# rt1060r2.net
KiCad netlist of a schematic drawn in EAGLE
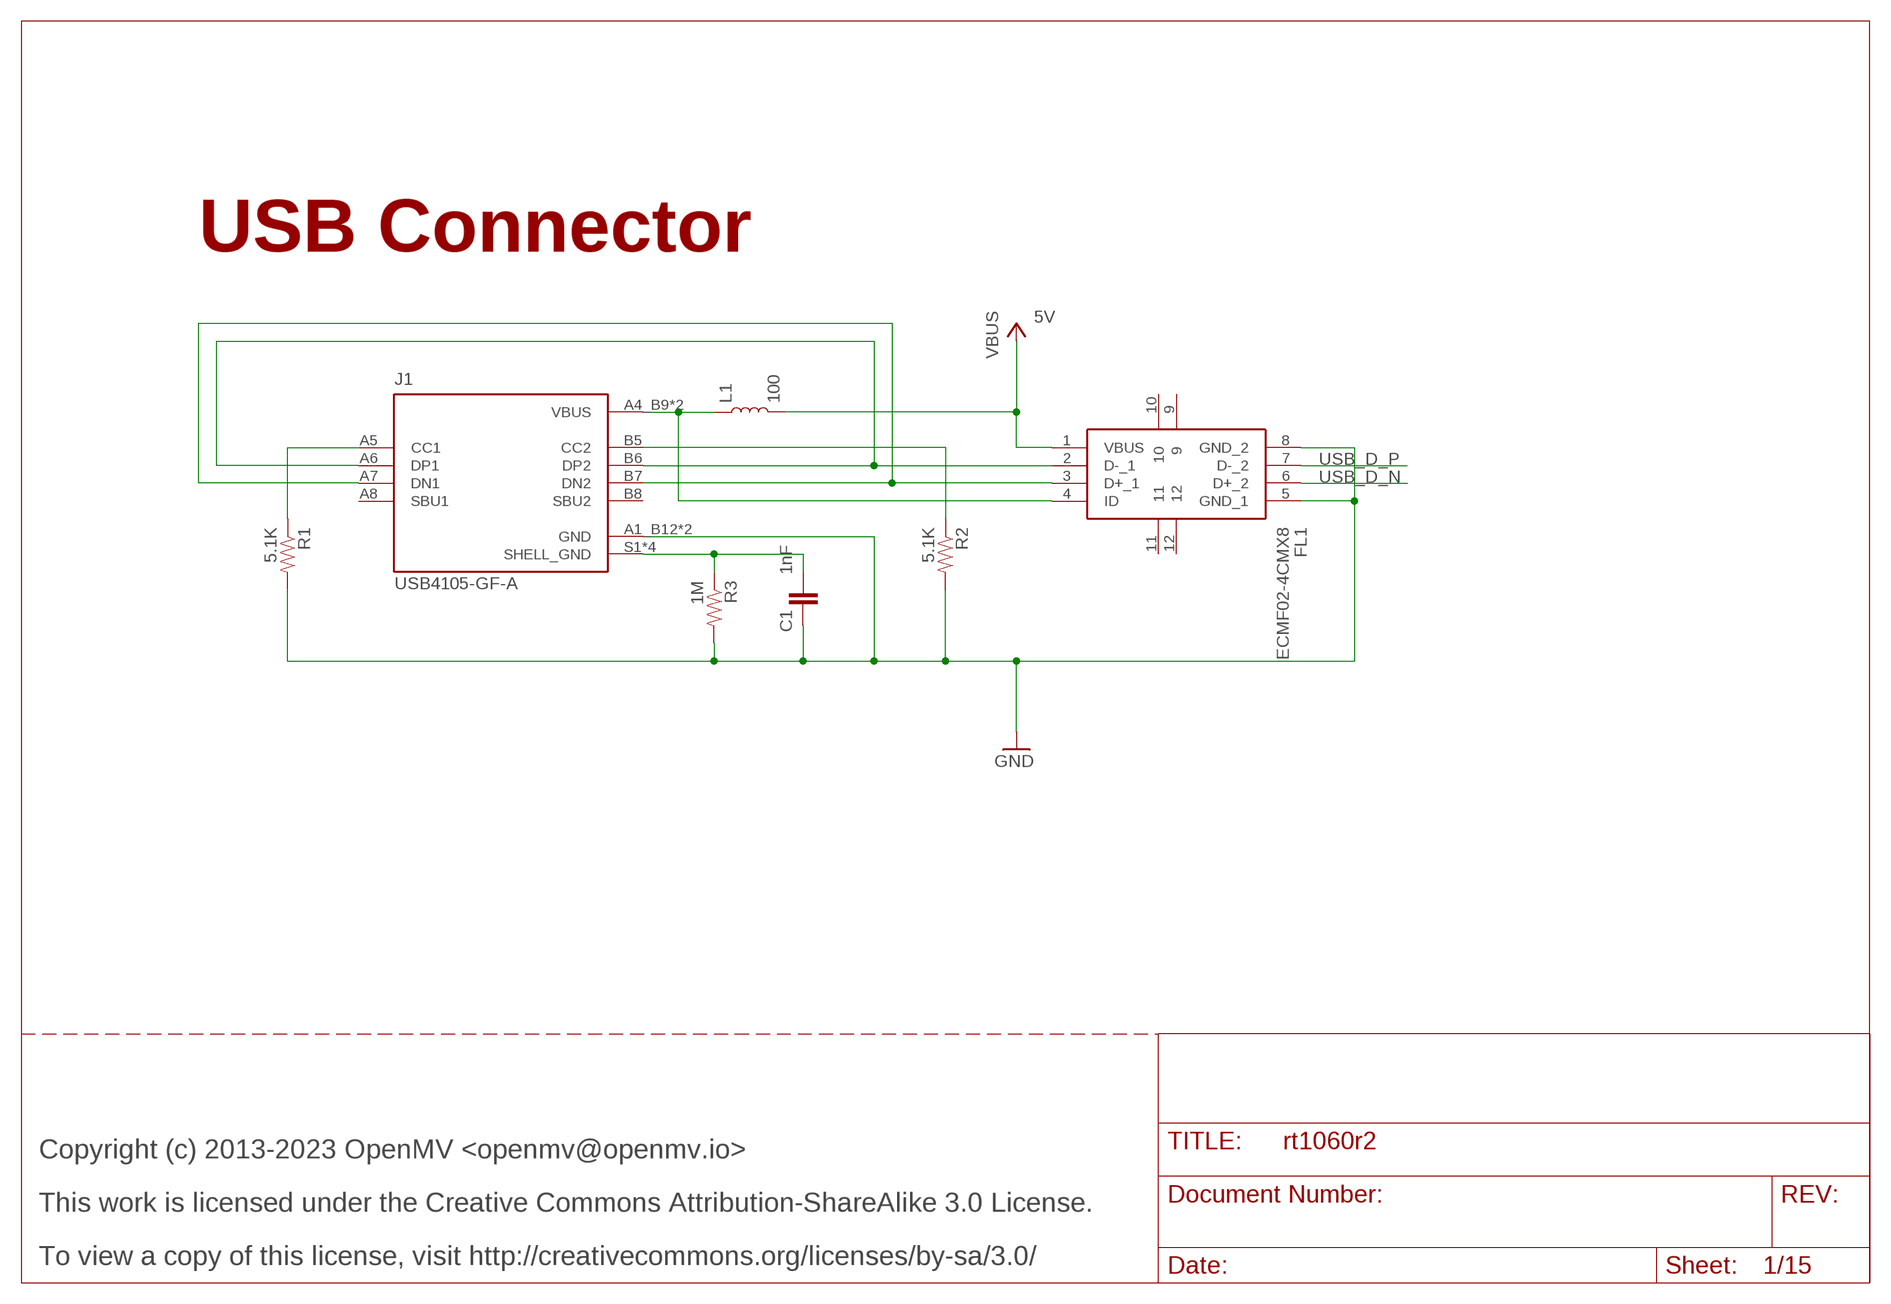
[diagram p0: schematic, sheet 1]
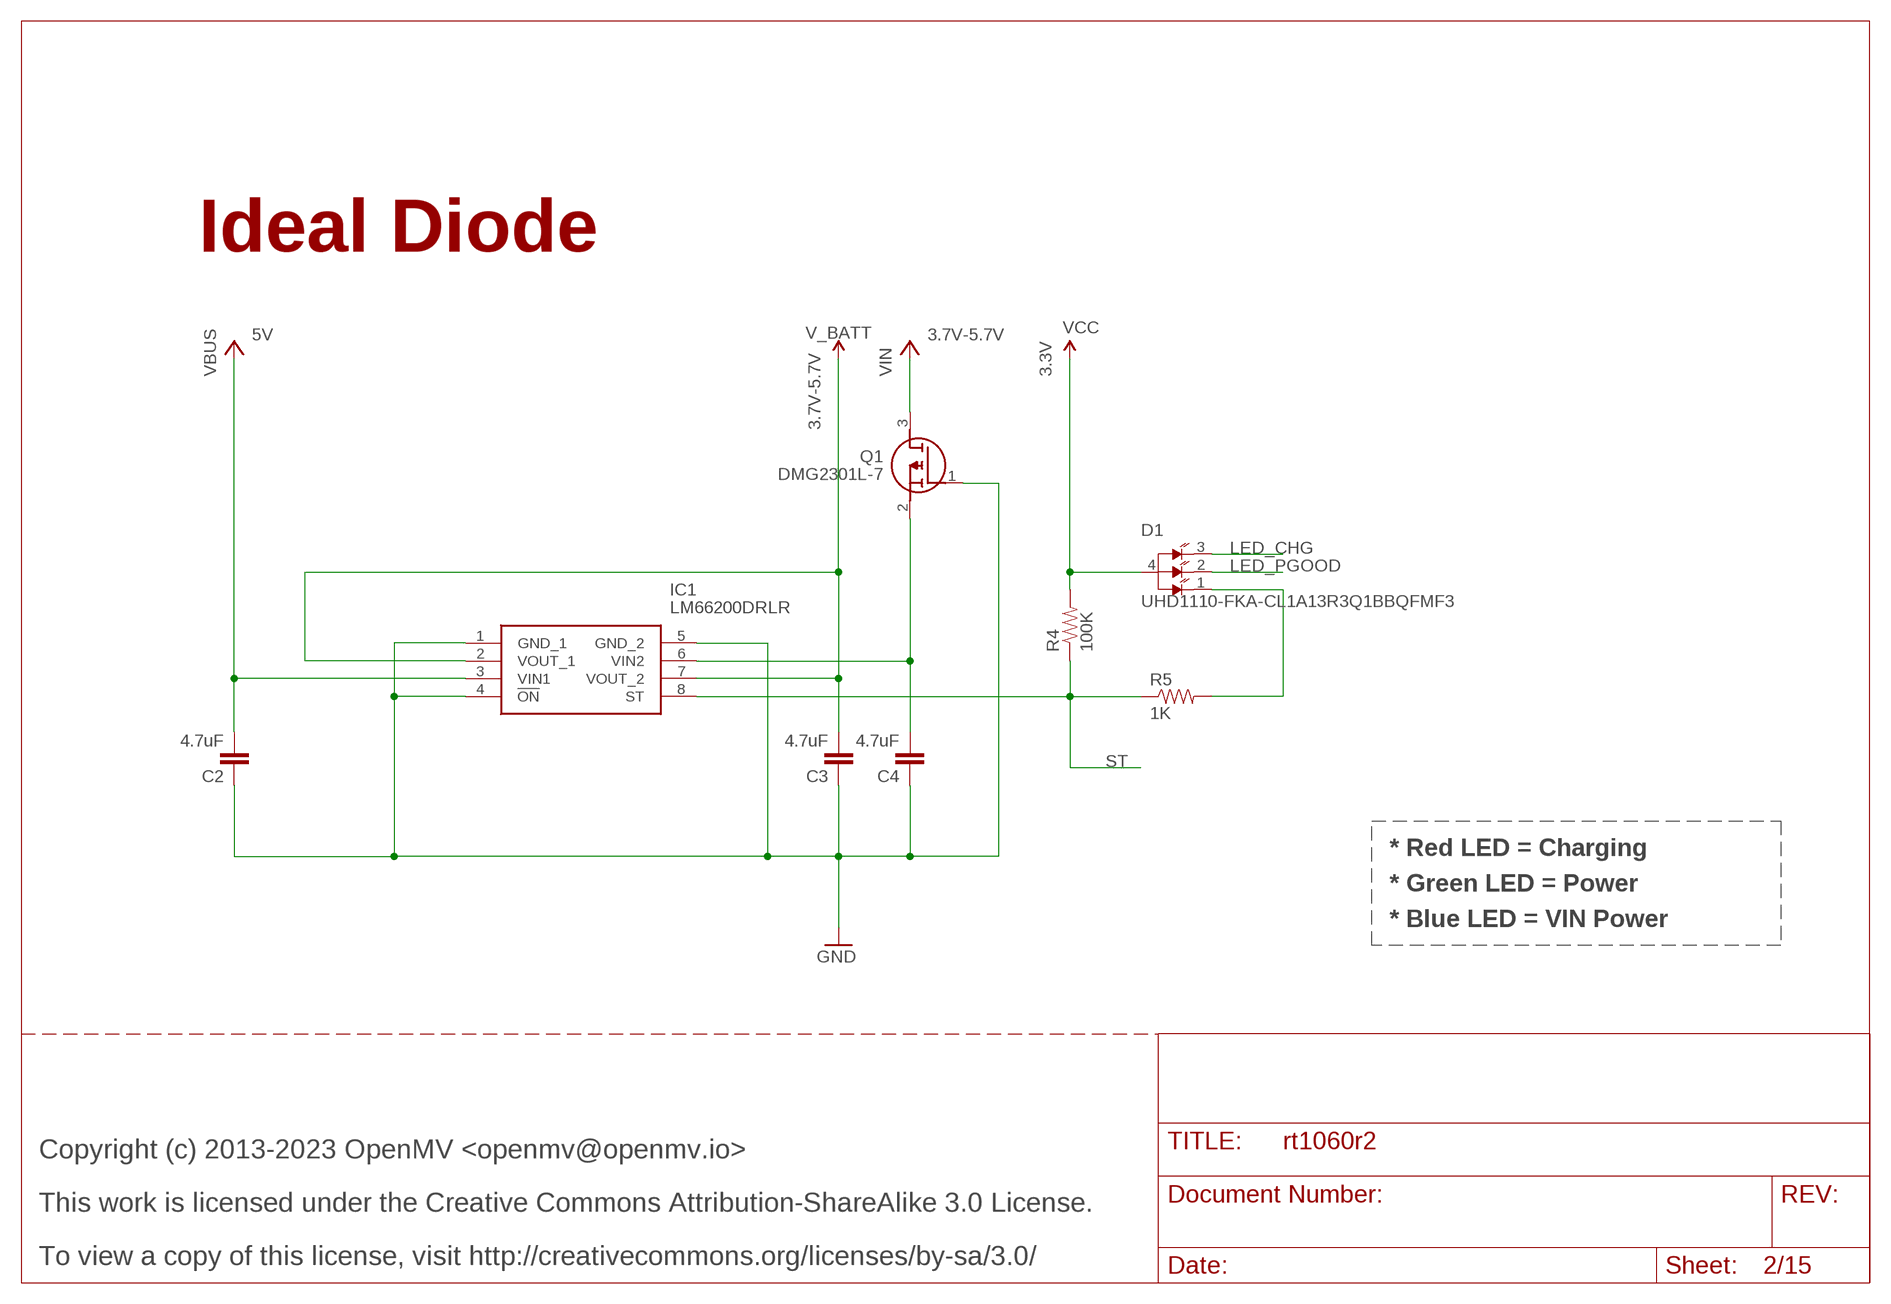
[diagram p1: schematic, sheet 2]
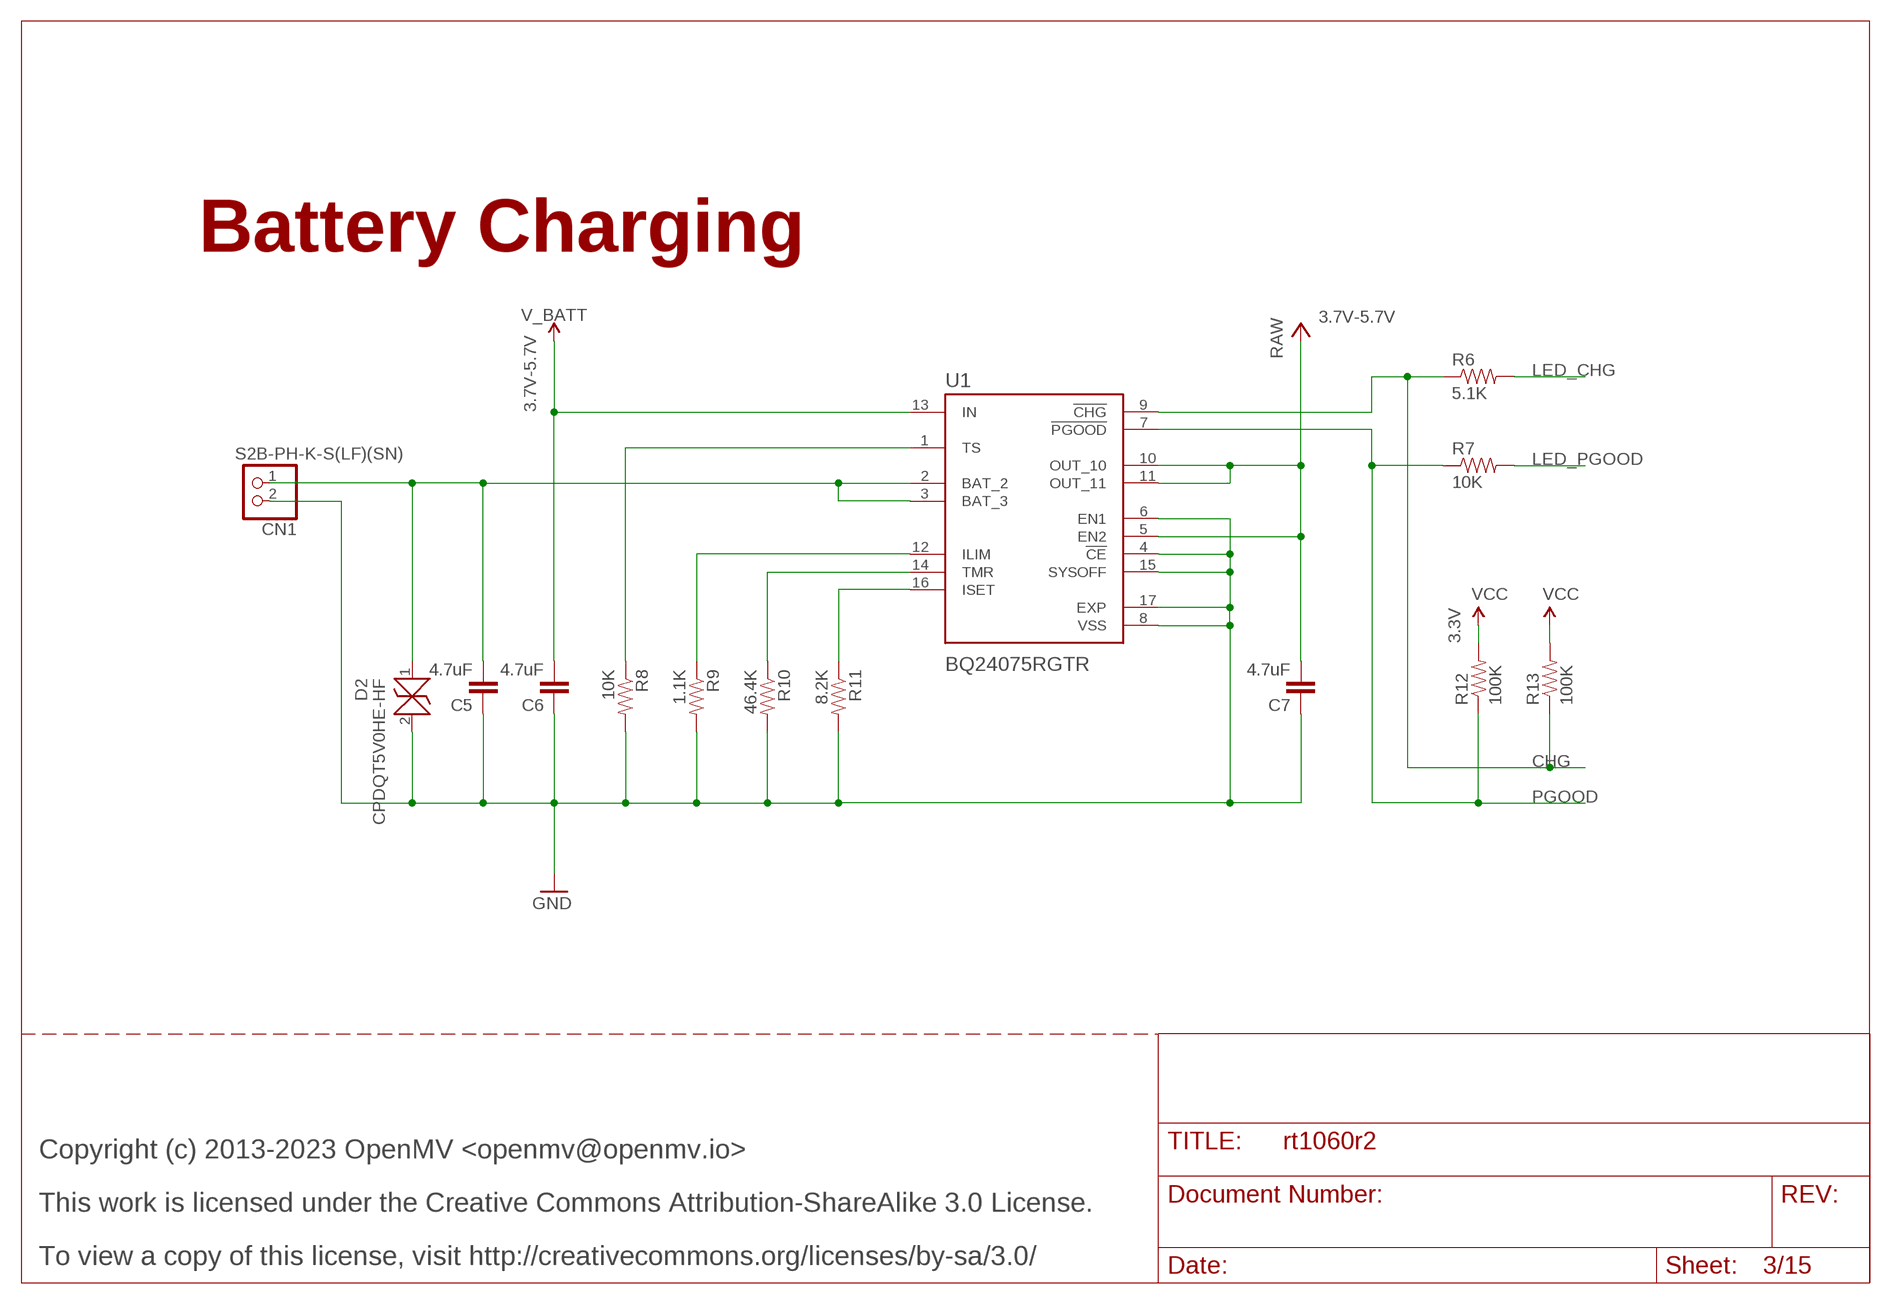
[diagram p2: schematic, sheet 3]
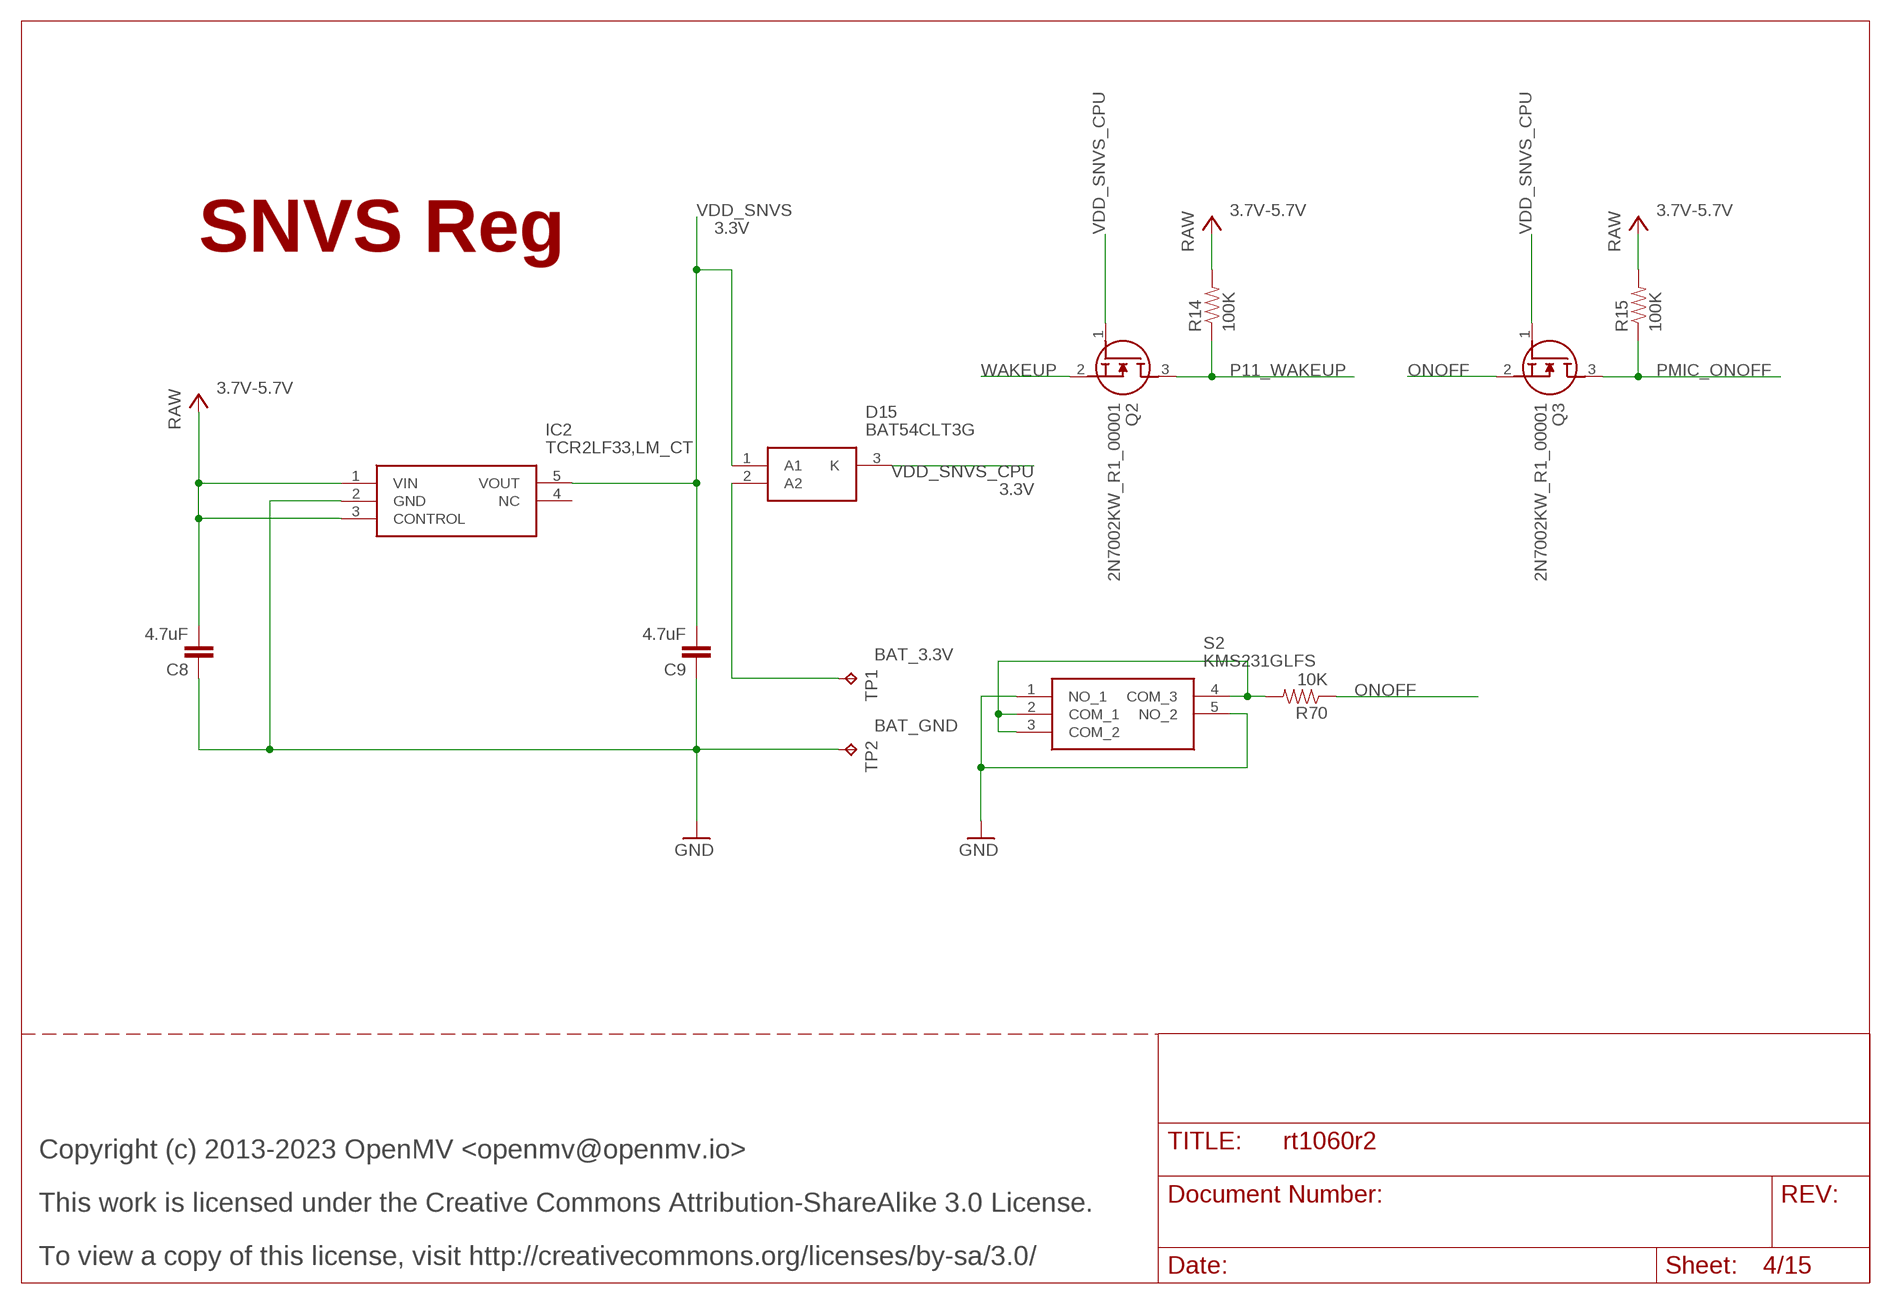
[diagram p3: schematic, sheet 4]
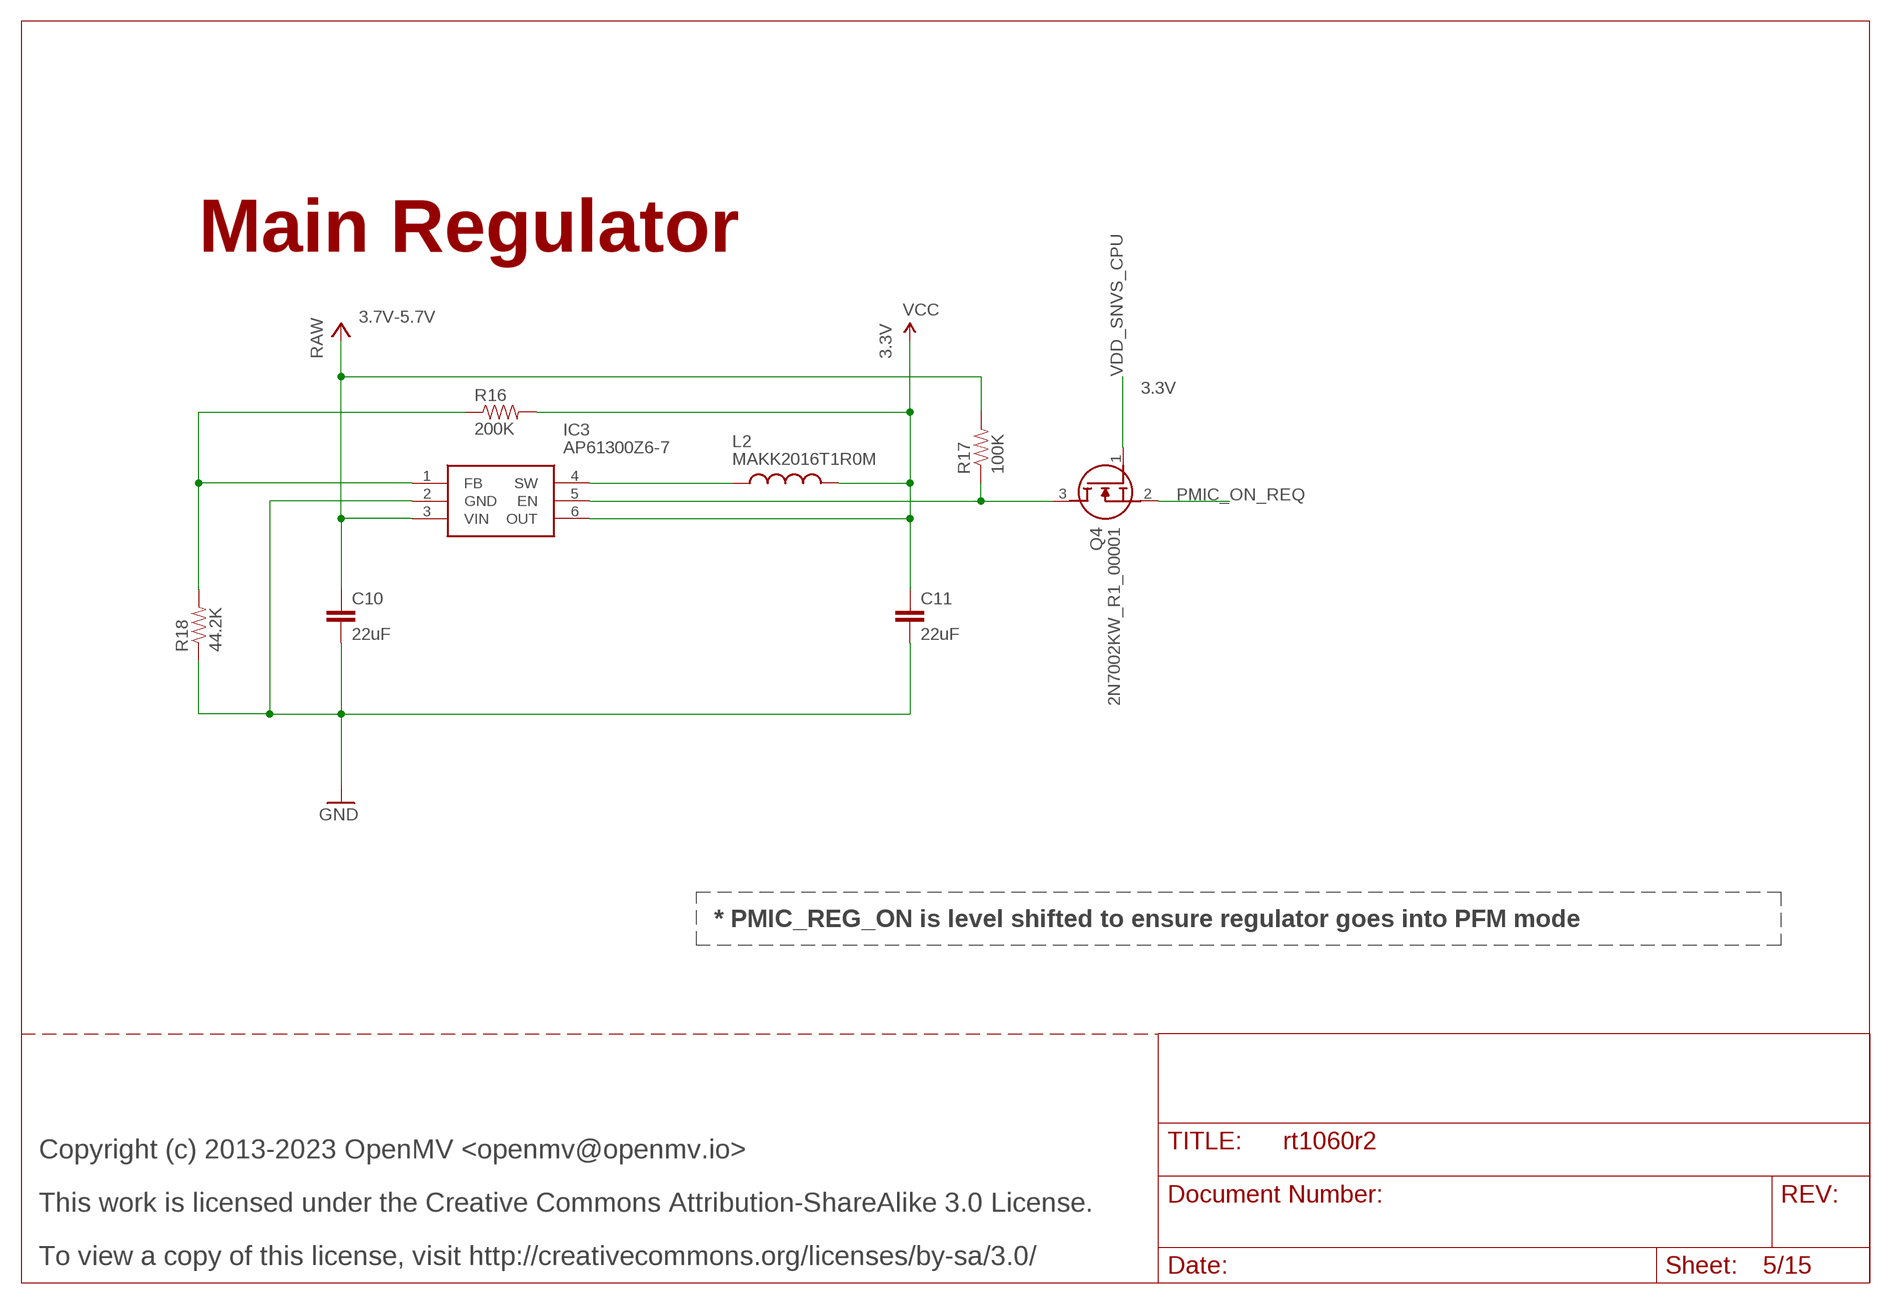
[diagram p4: schematic, sheet 5]
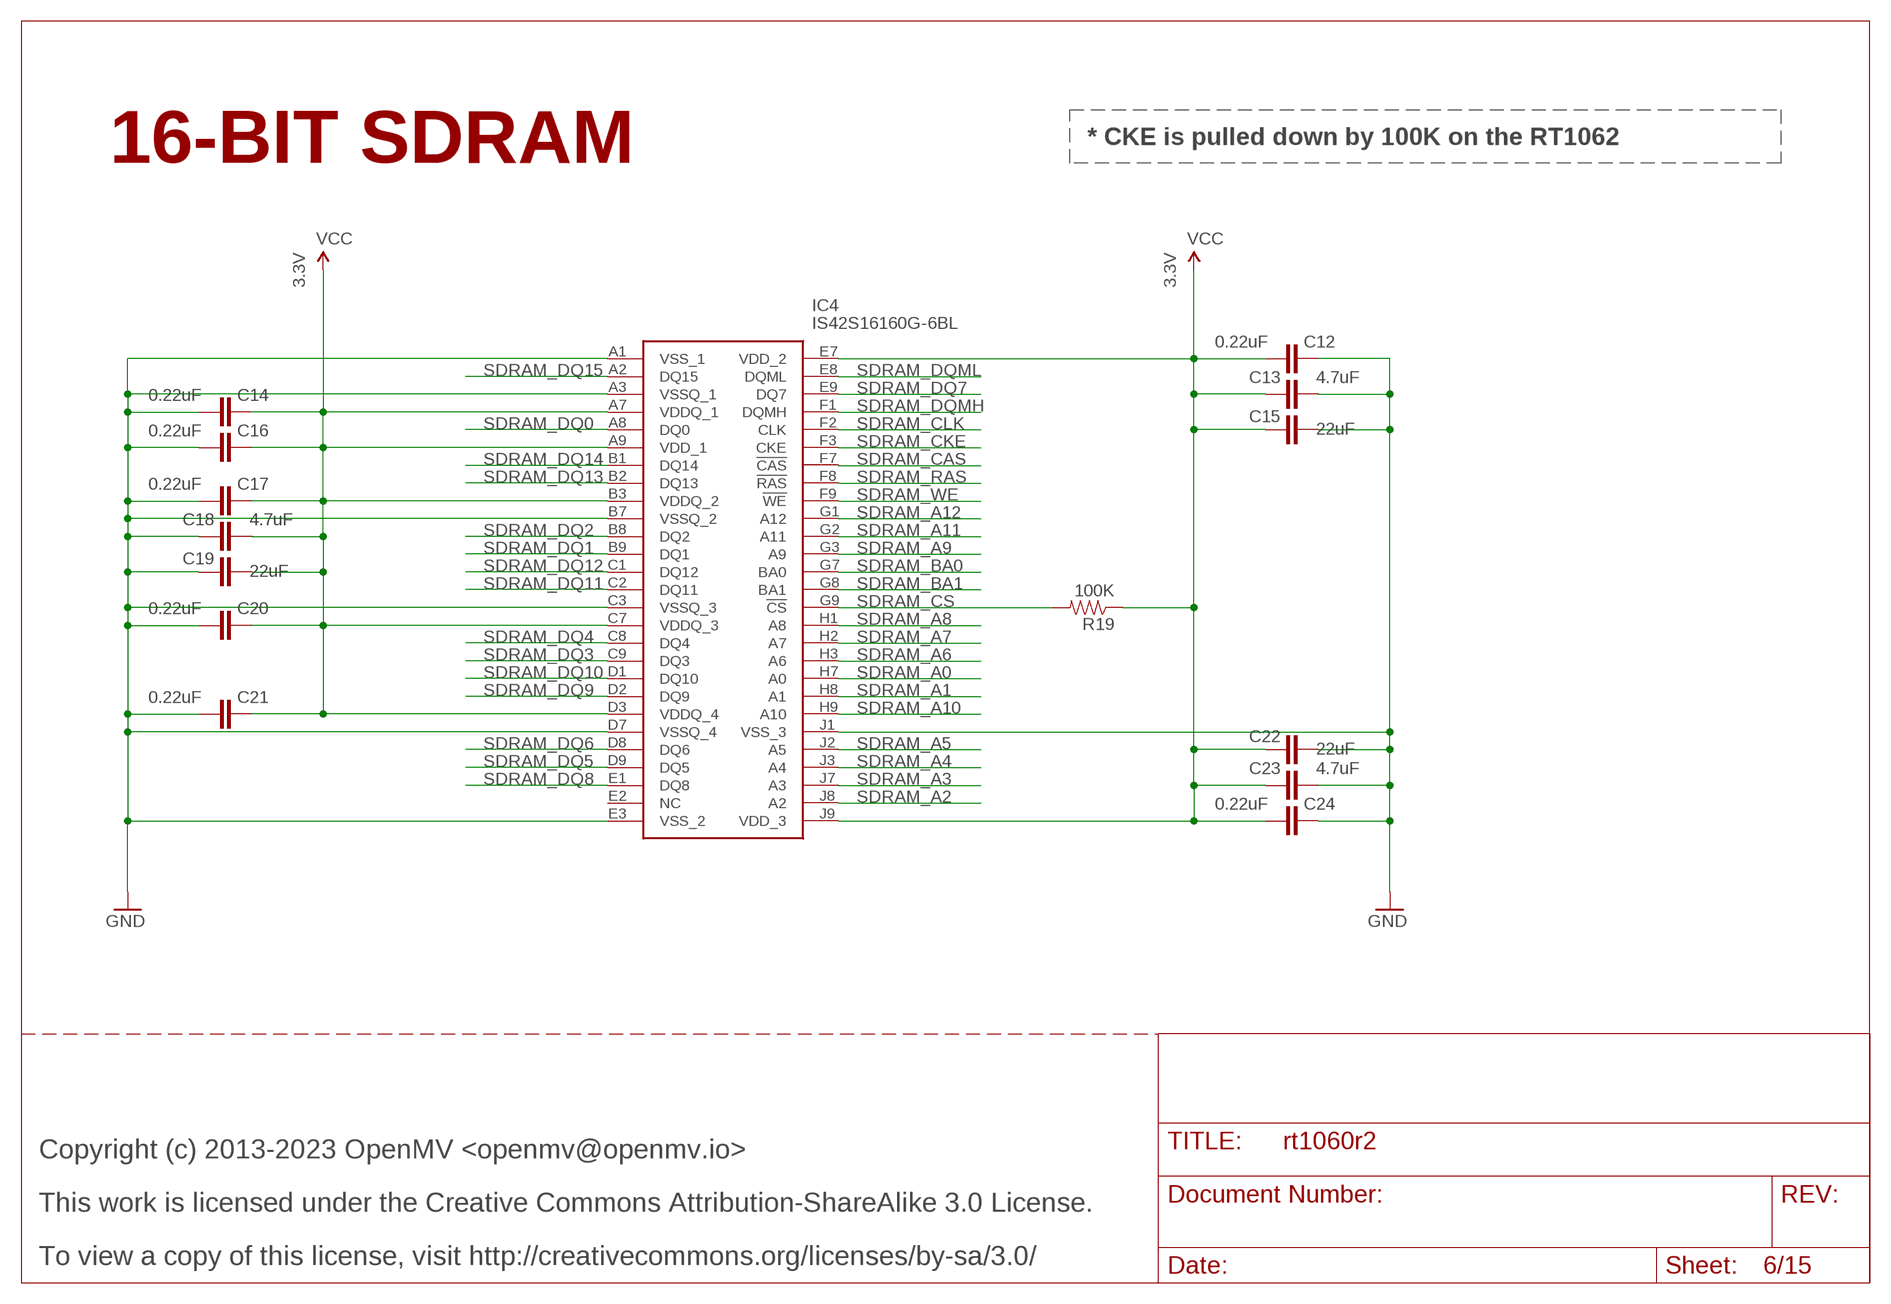
[diagram p5: schematic, sheet 6]
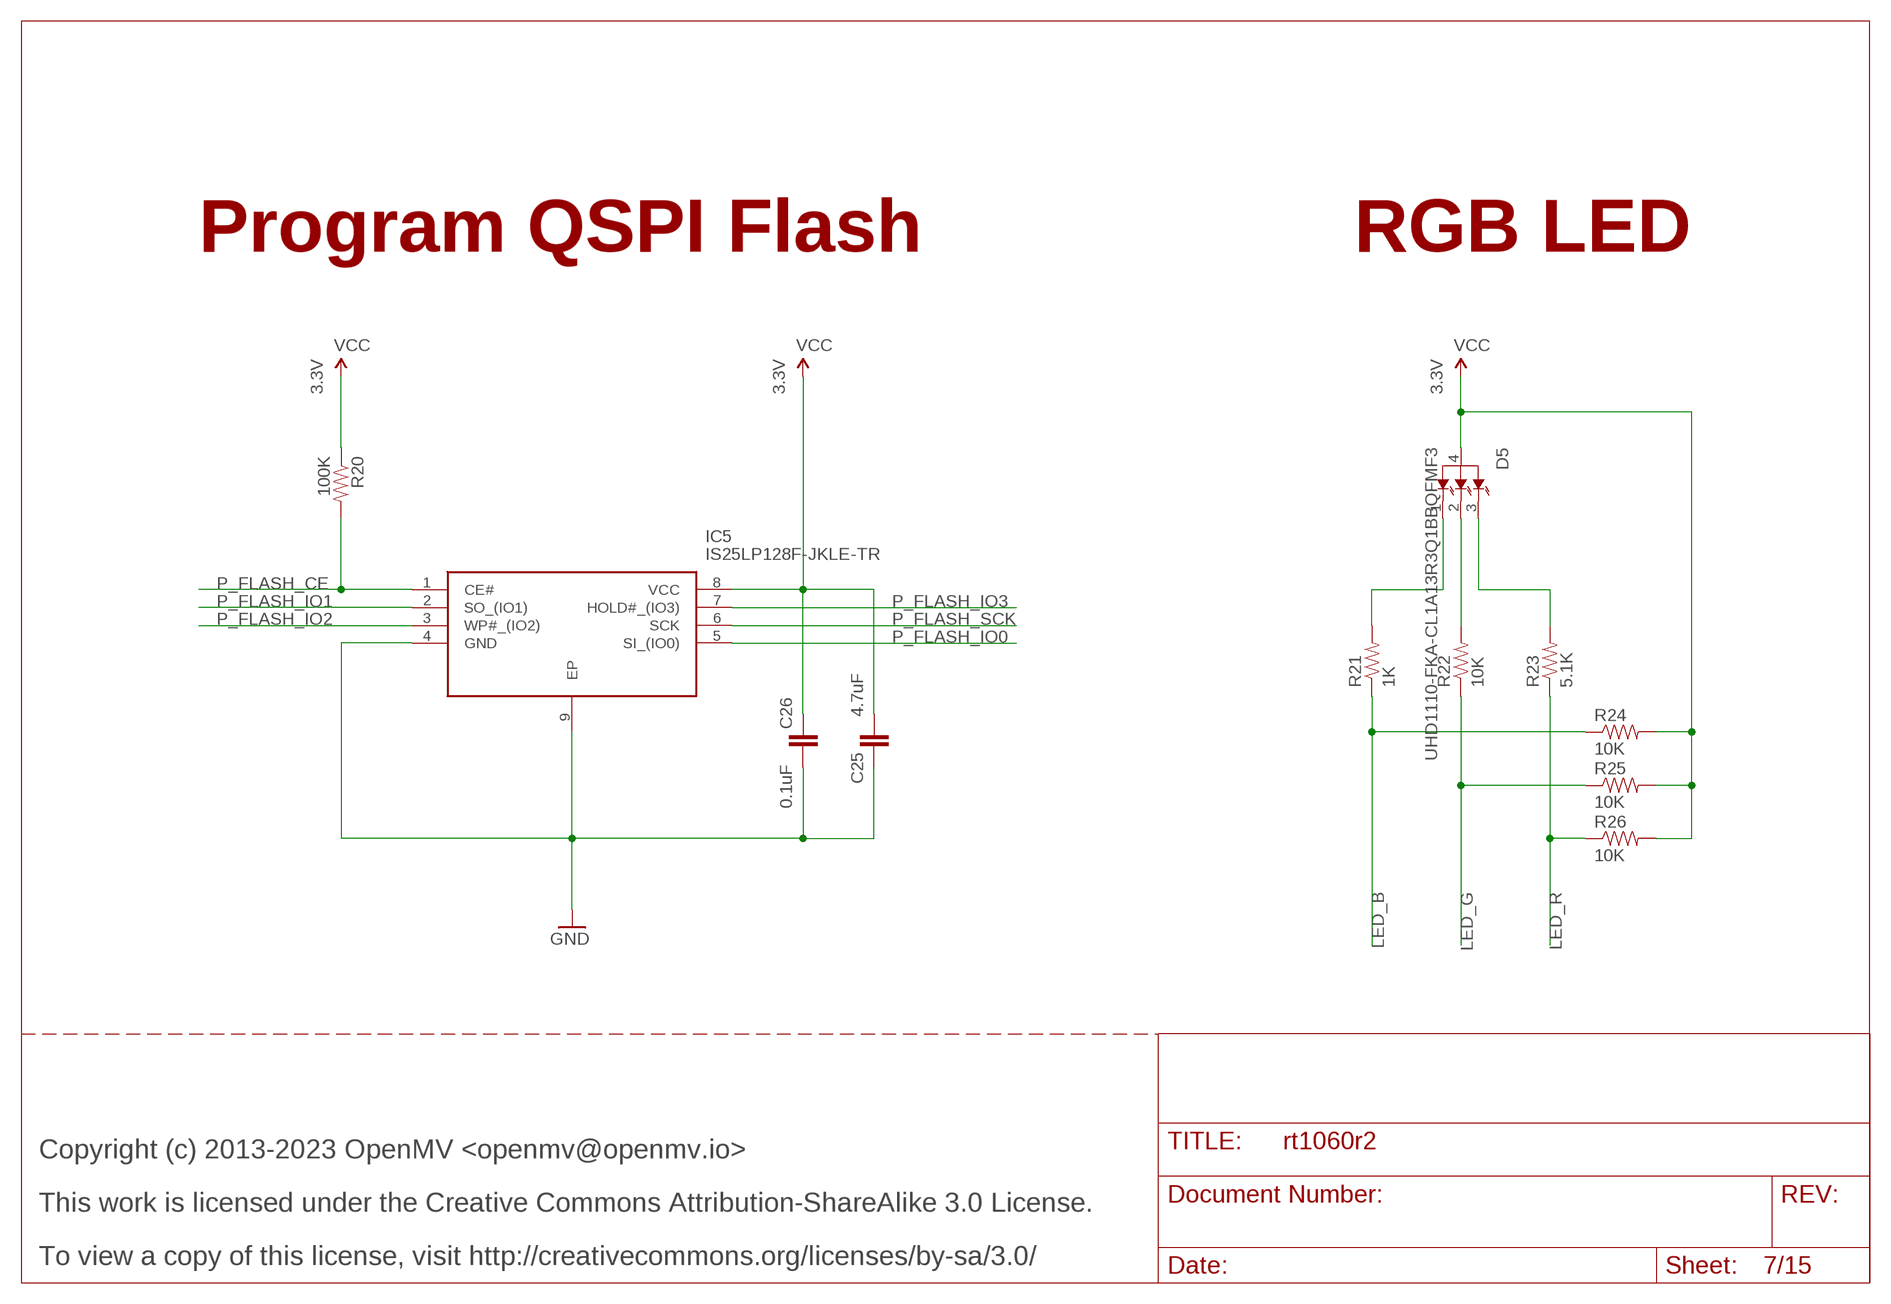
[diagram p6: schematic, sheet 7]
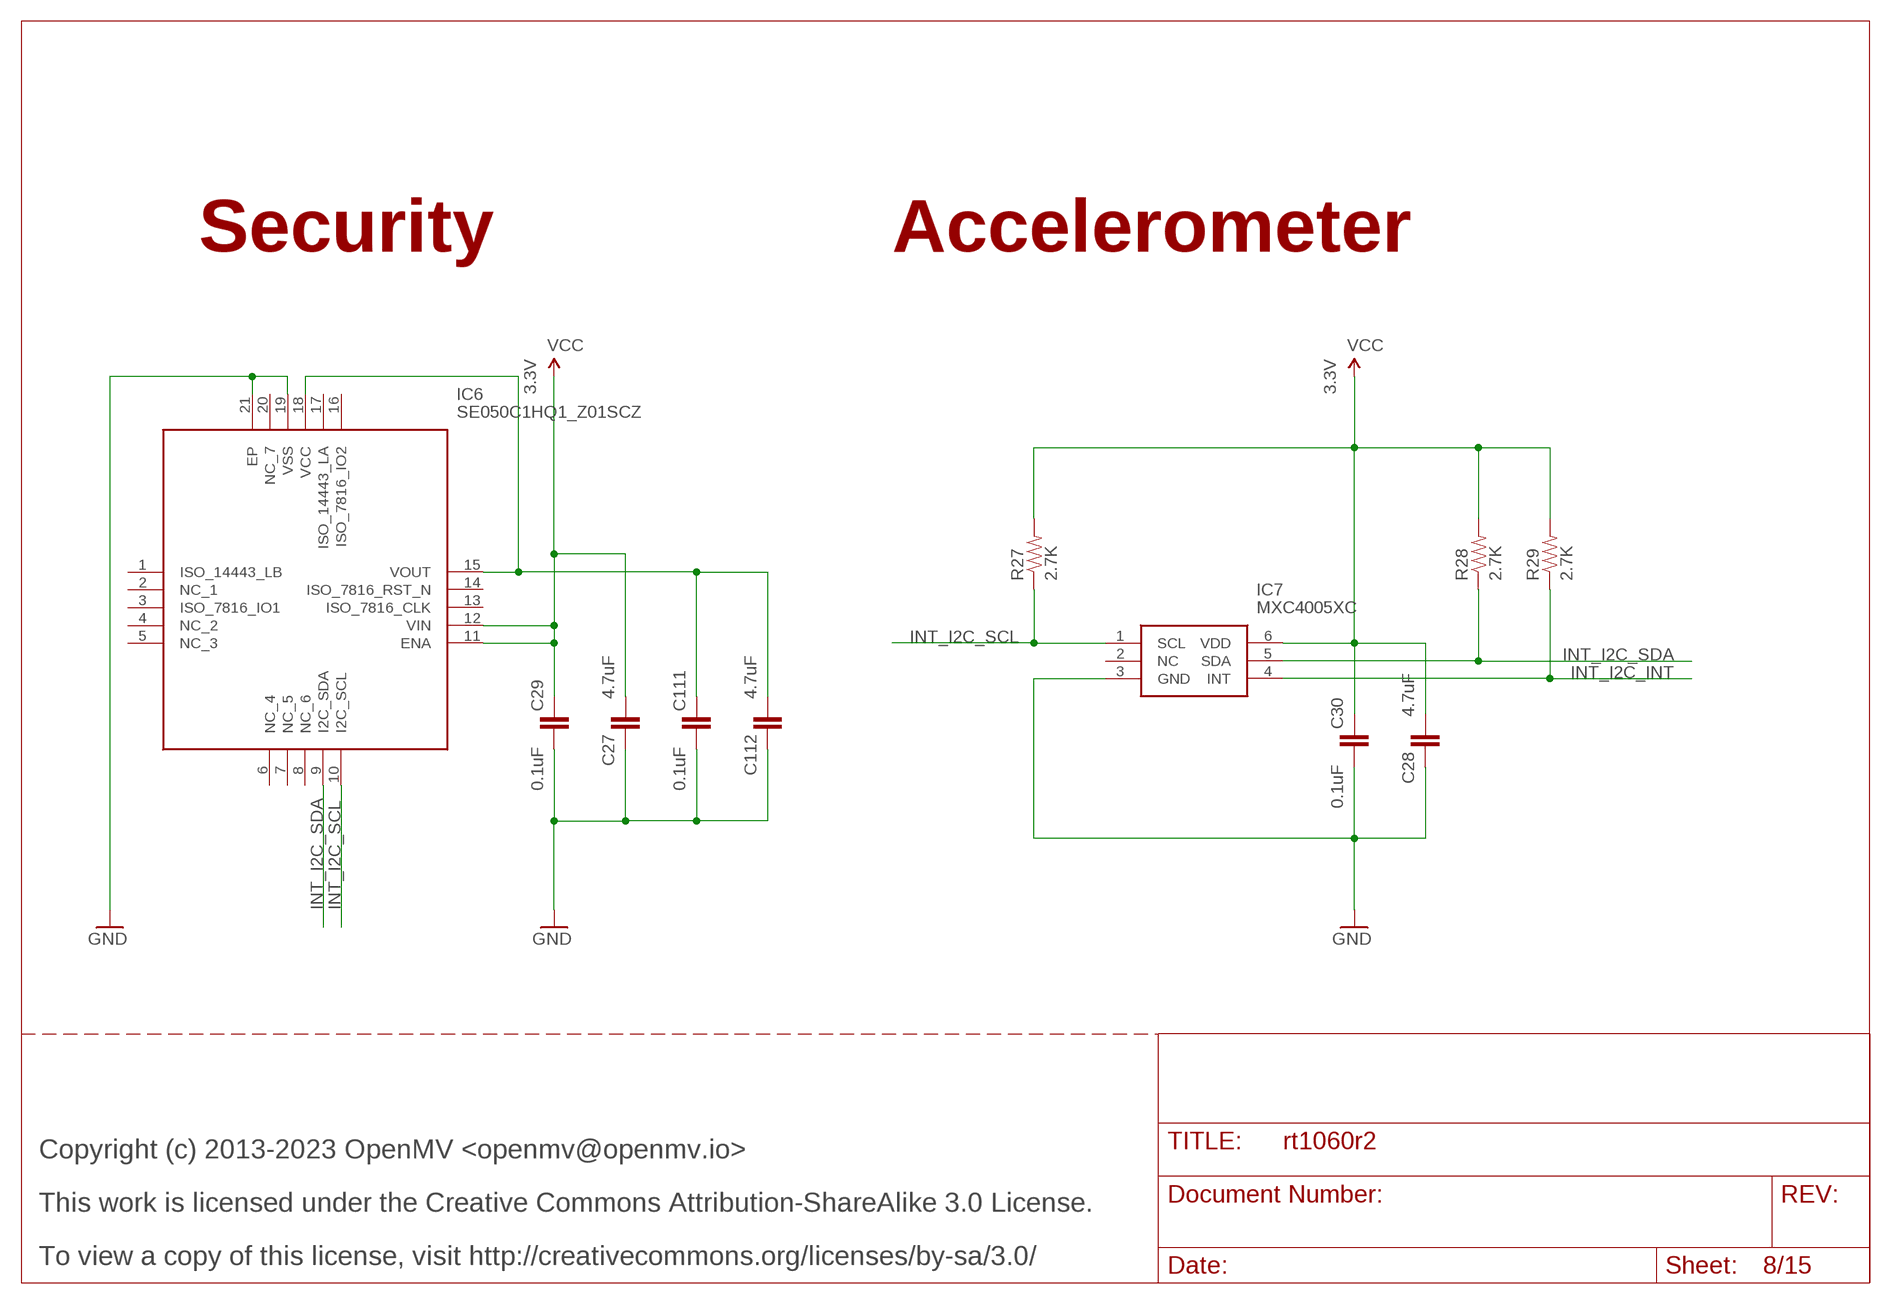
[diagram p7: schematic, sheet 8]
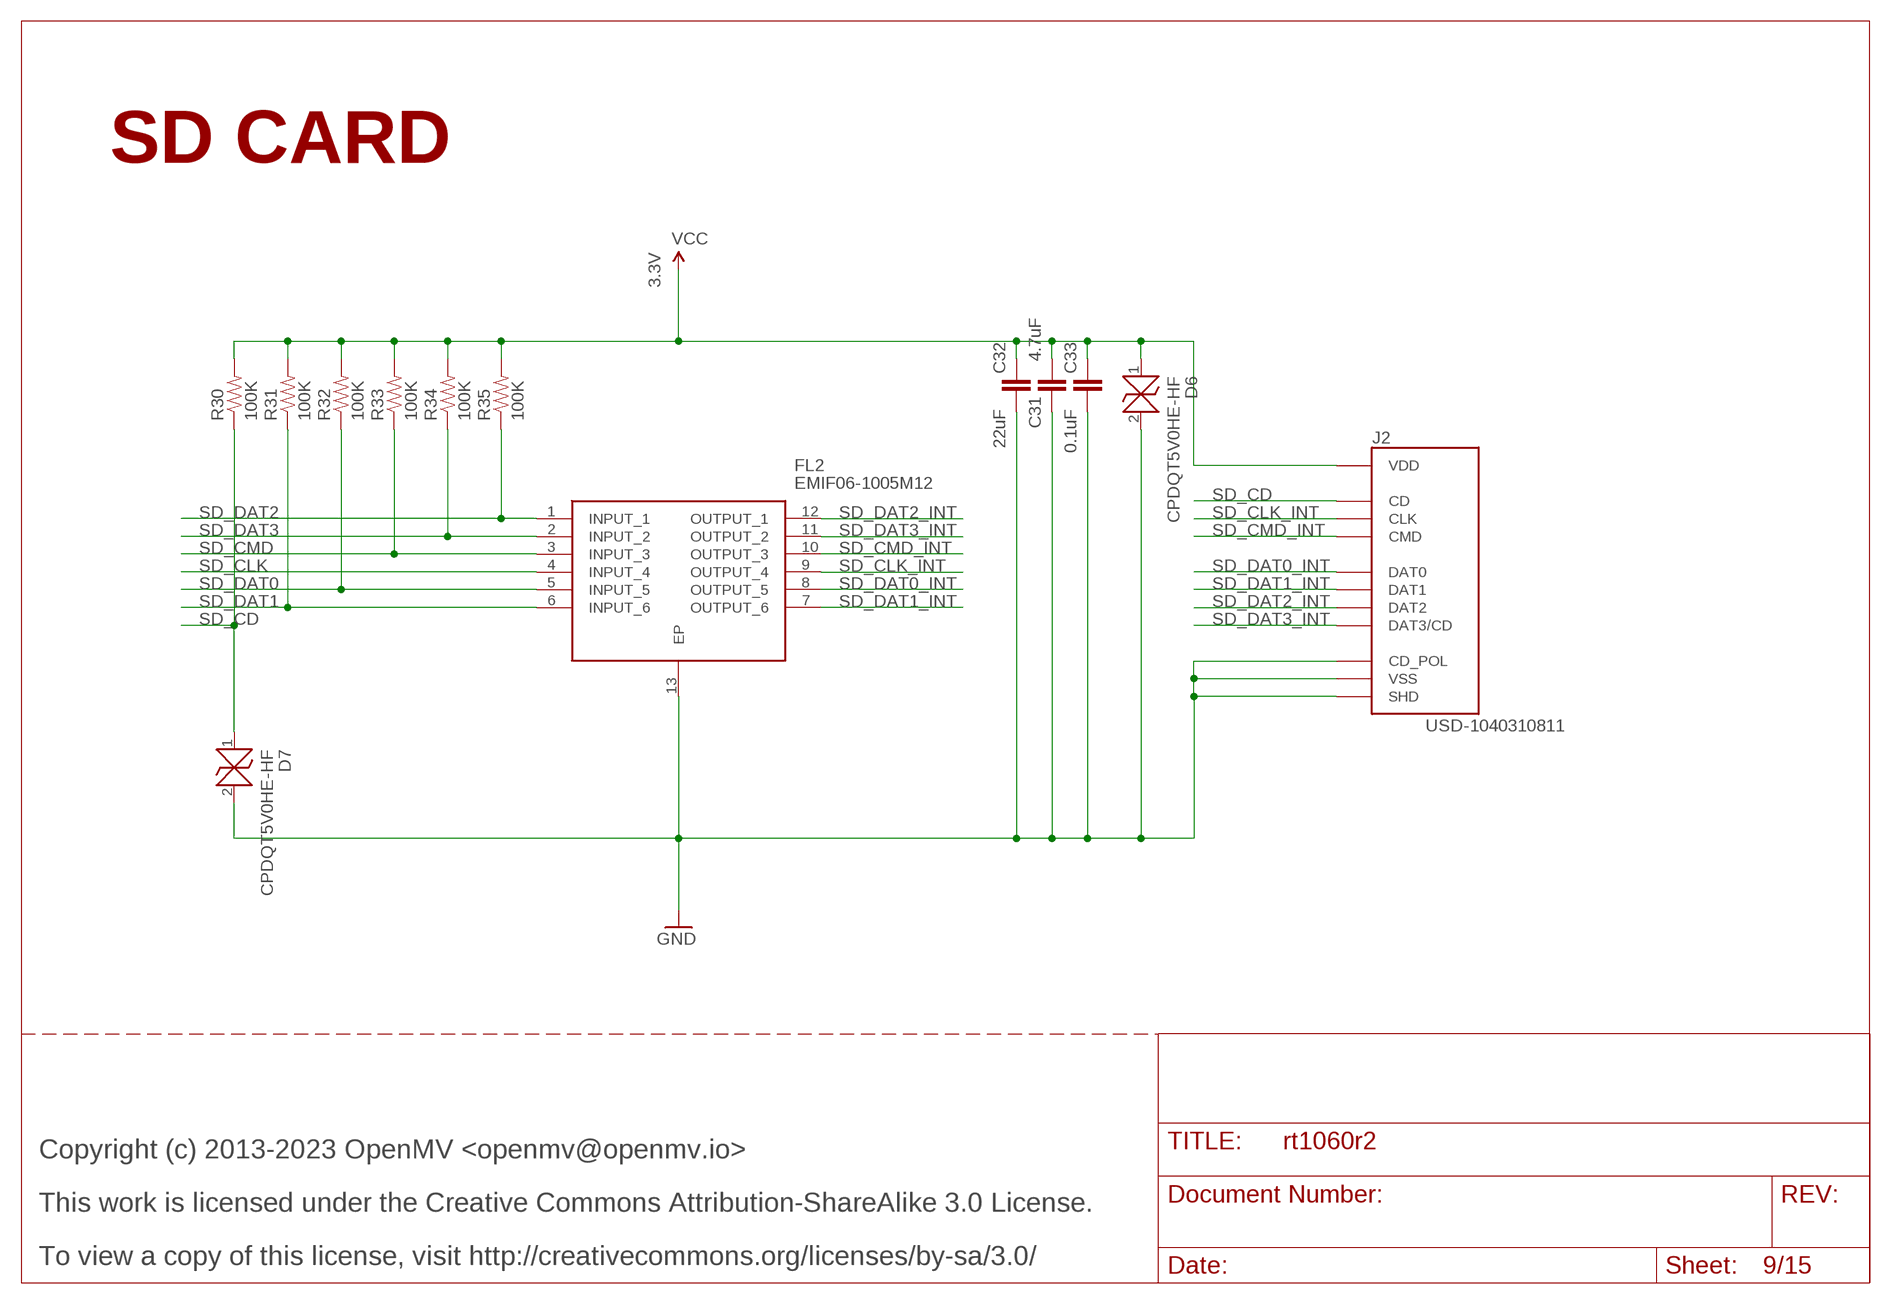
[diagram p8: schematic, sheet 9]
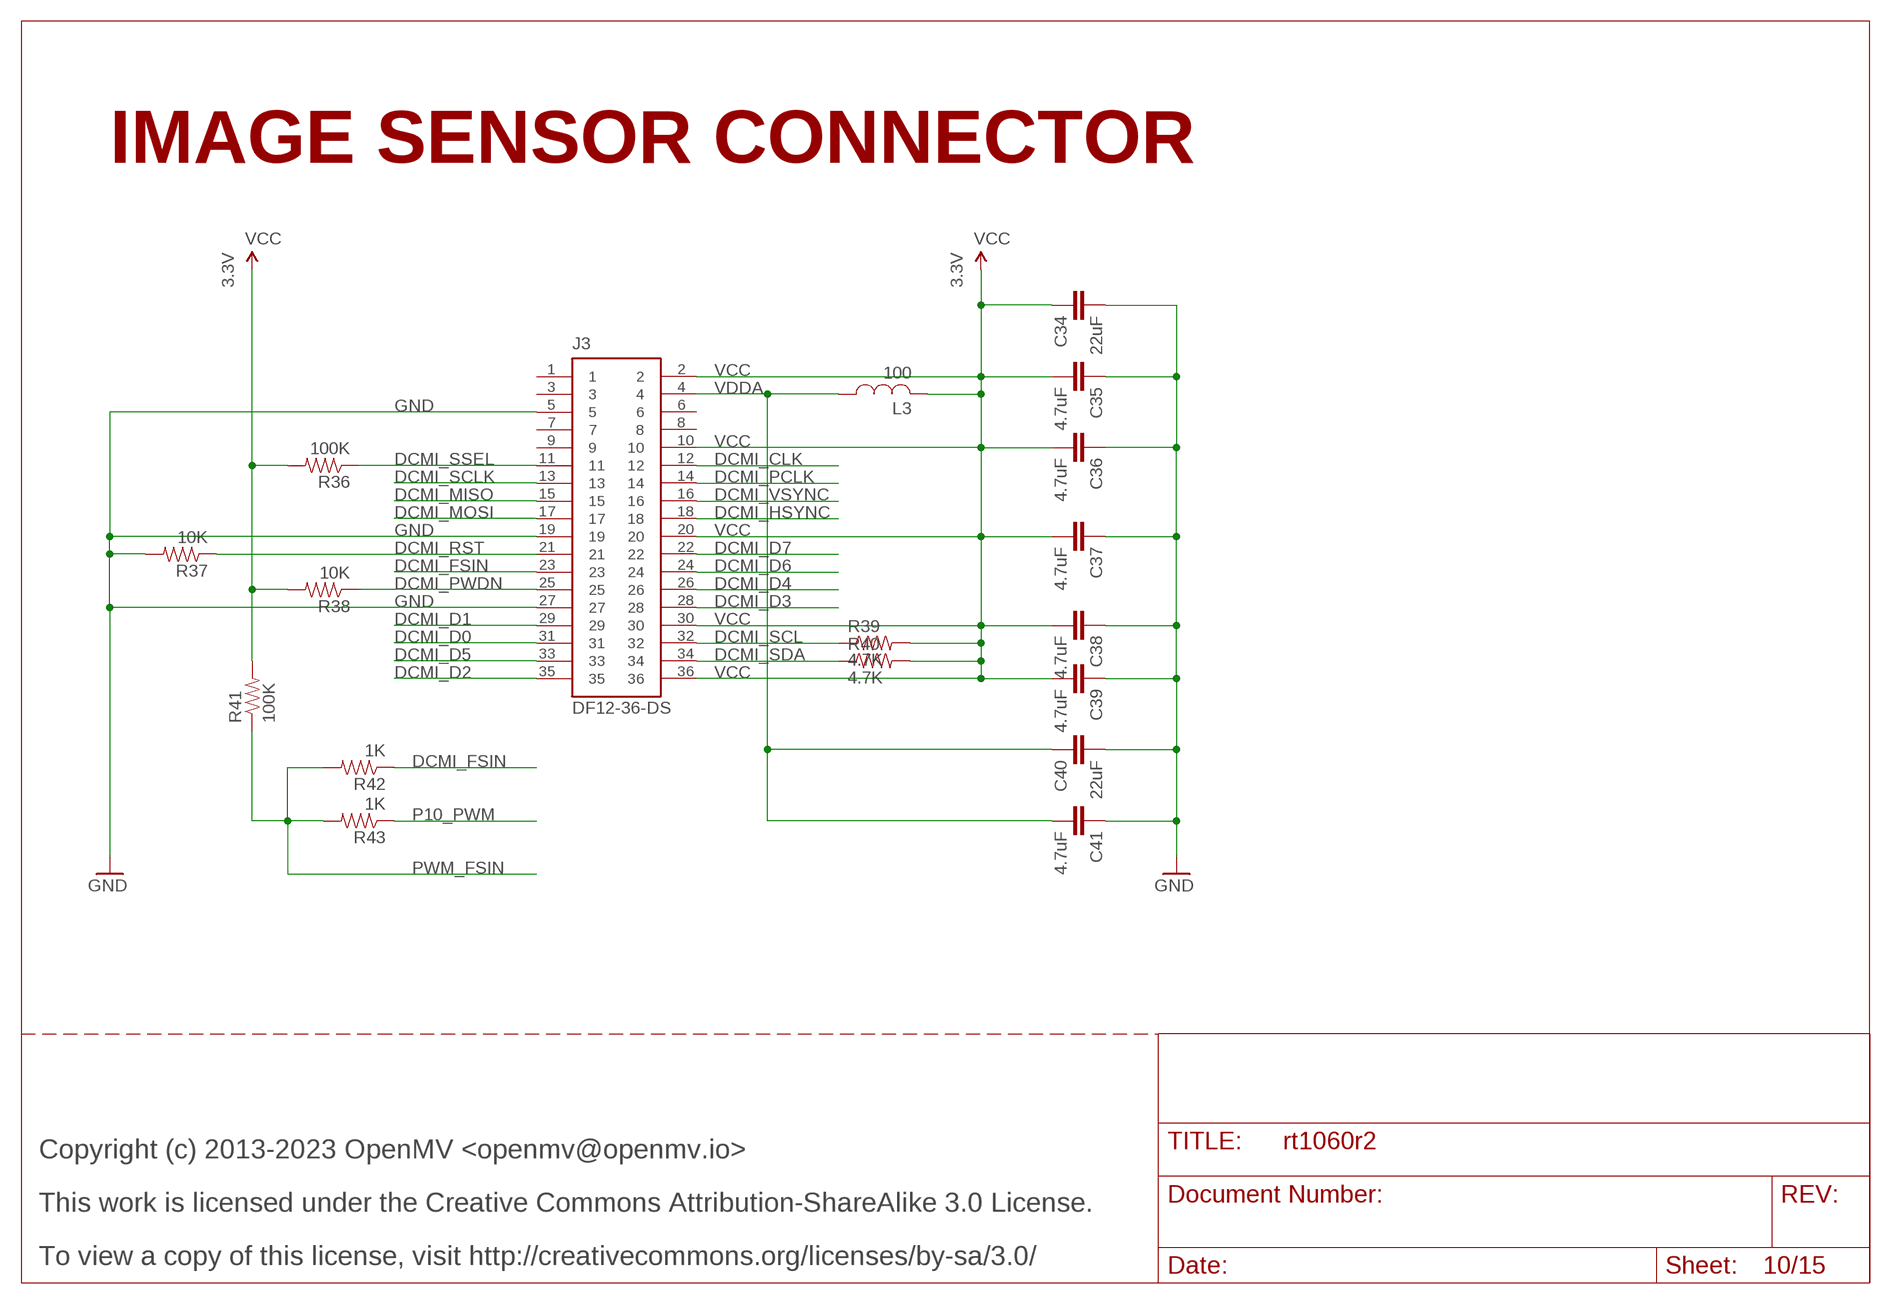
[diagram p9: schematic, sheet 10]
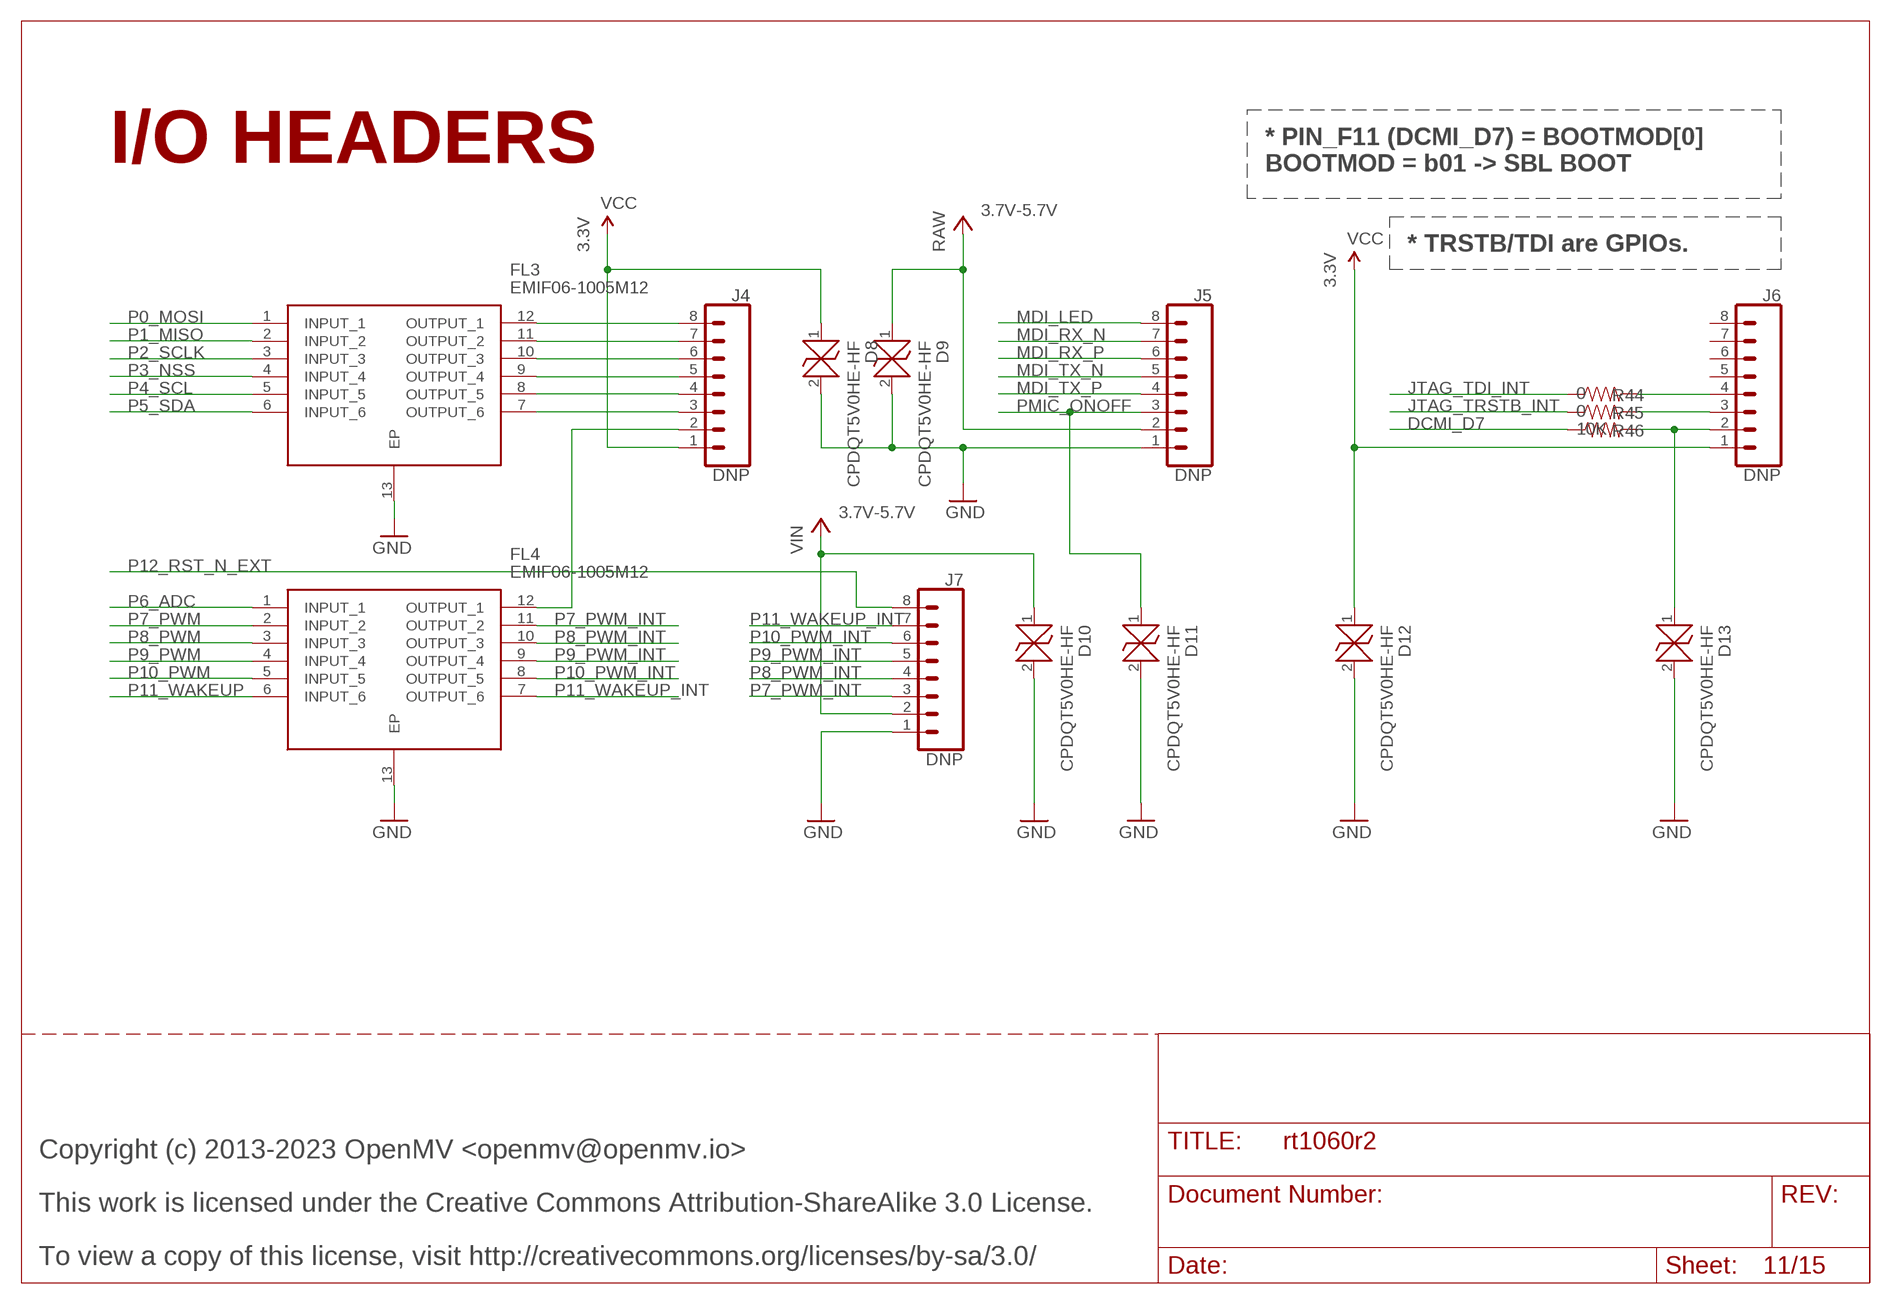
[diagram p10: schematic, sheet 11]
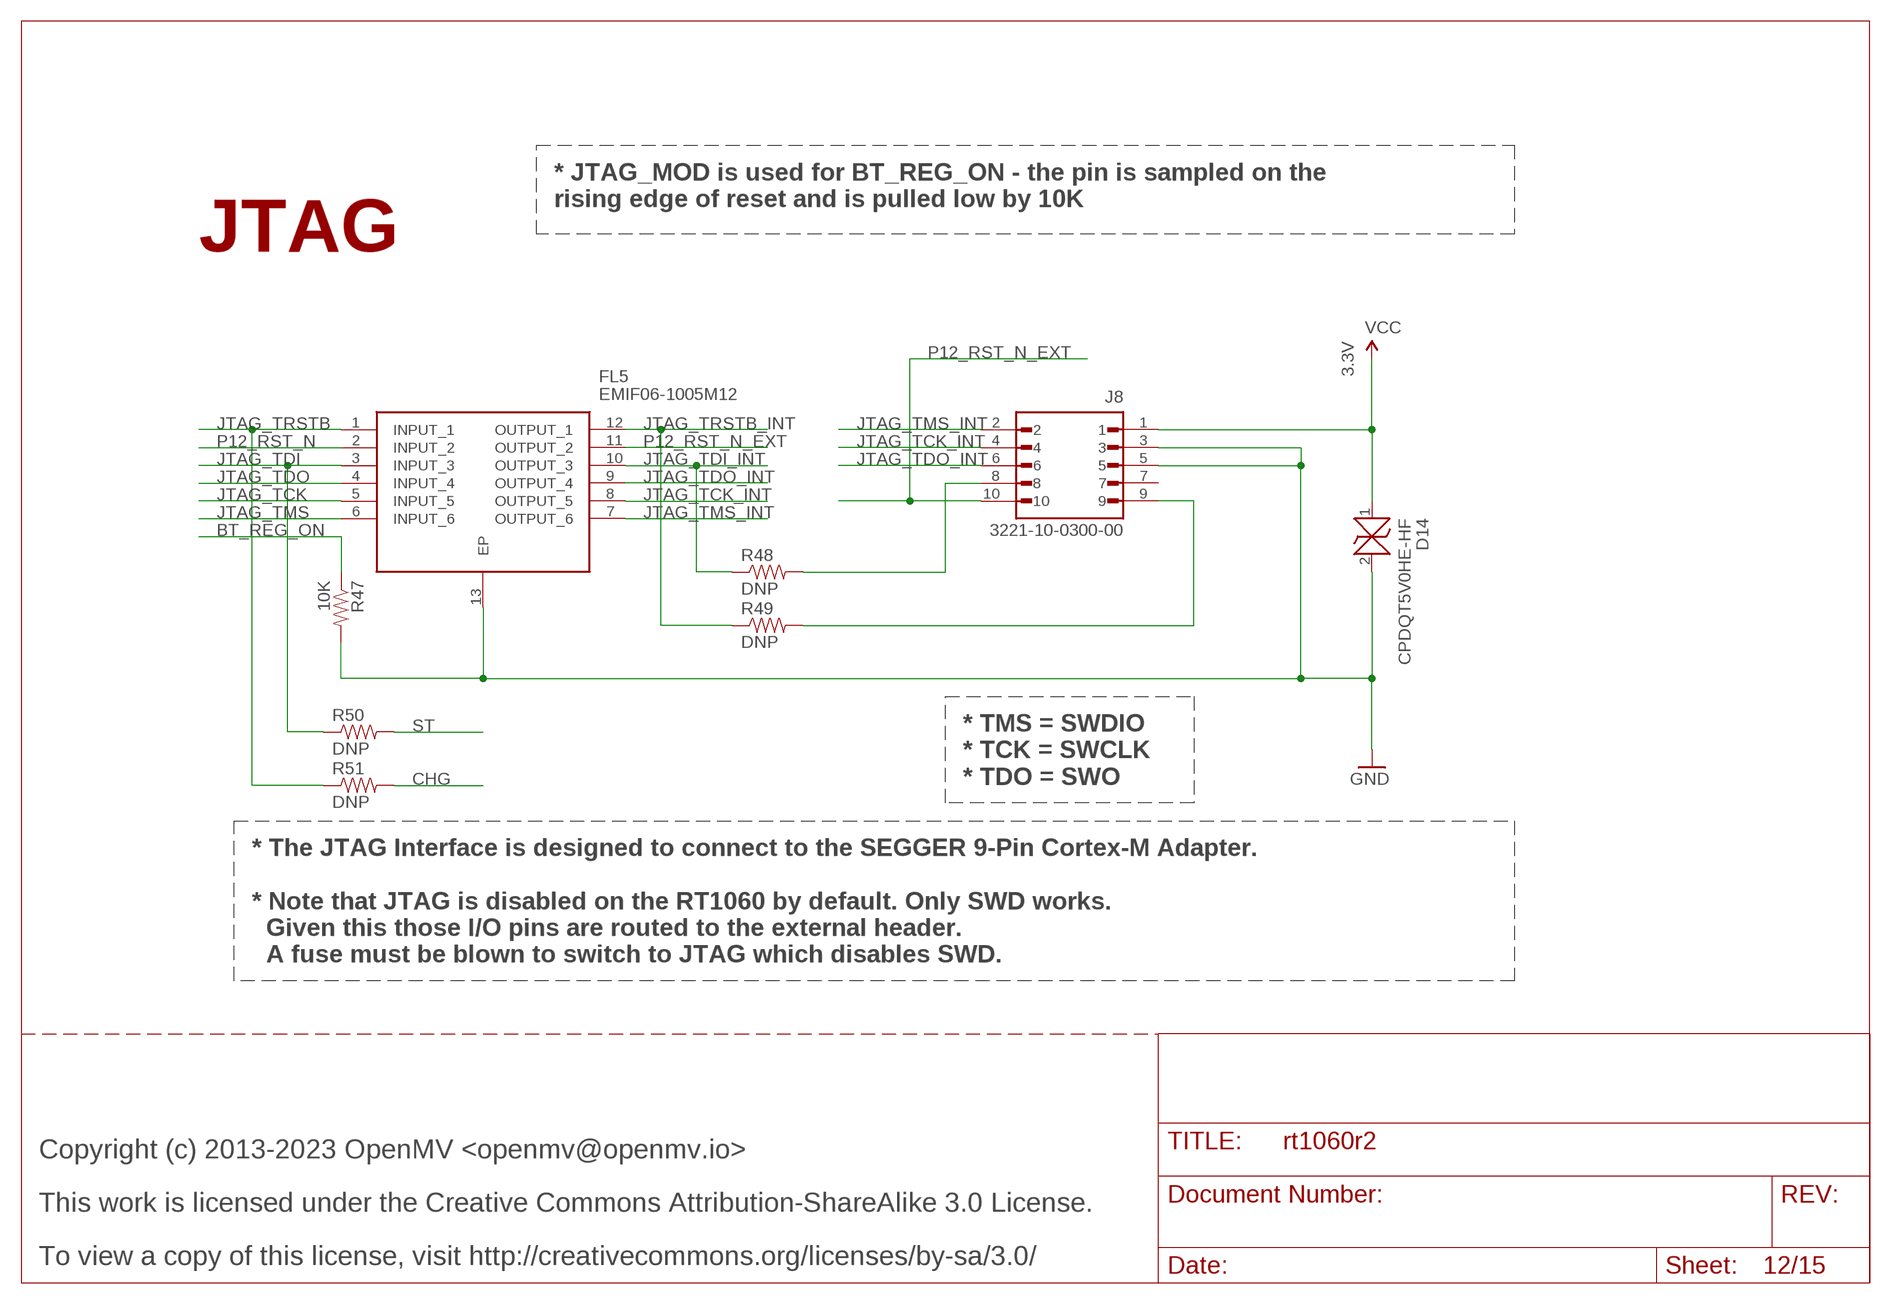
[diagram p11: schematic, sheet 12]
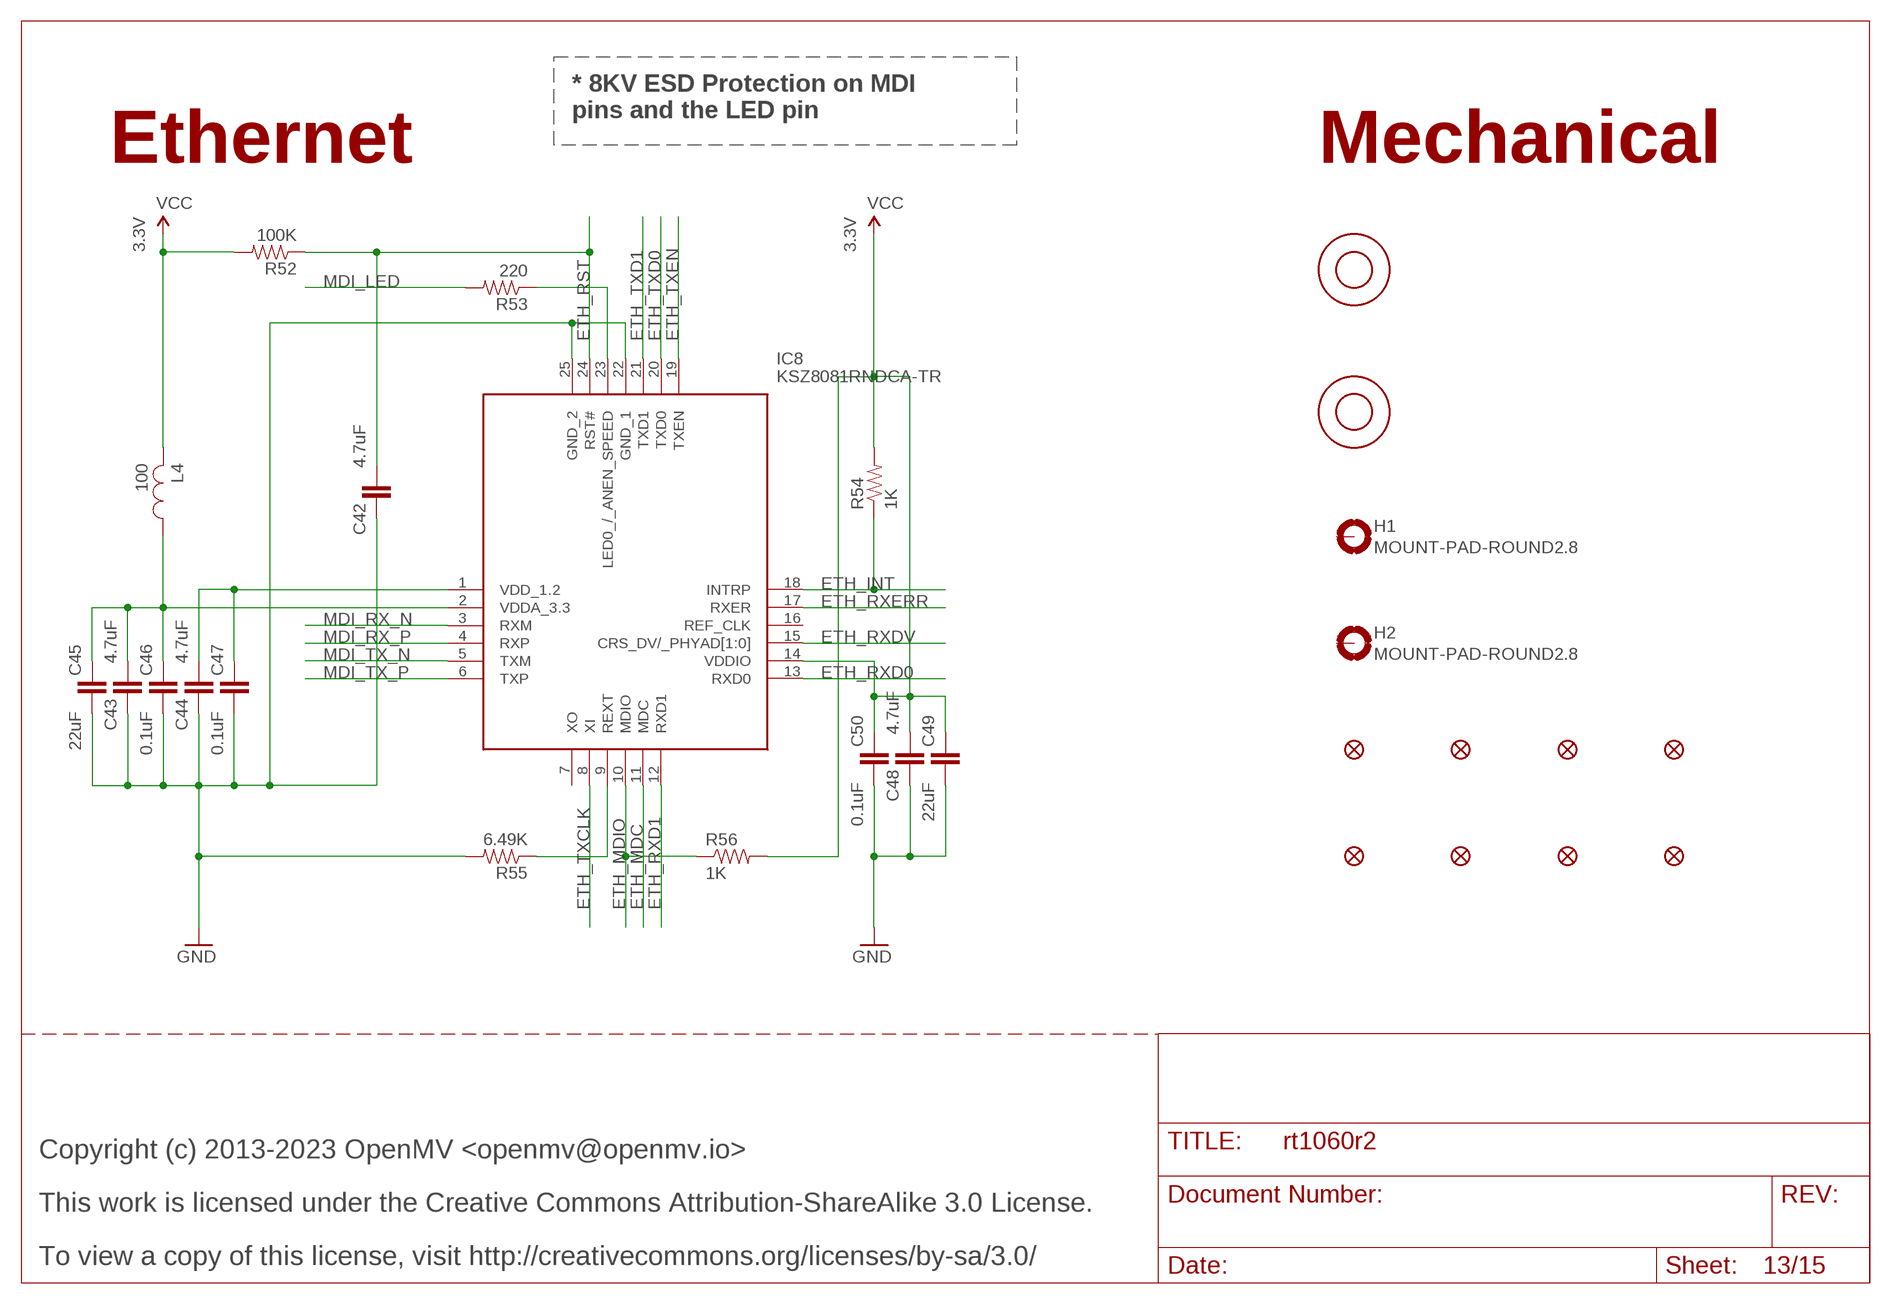
[diagram p12: schematic, sheet 13]
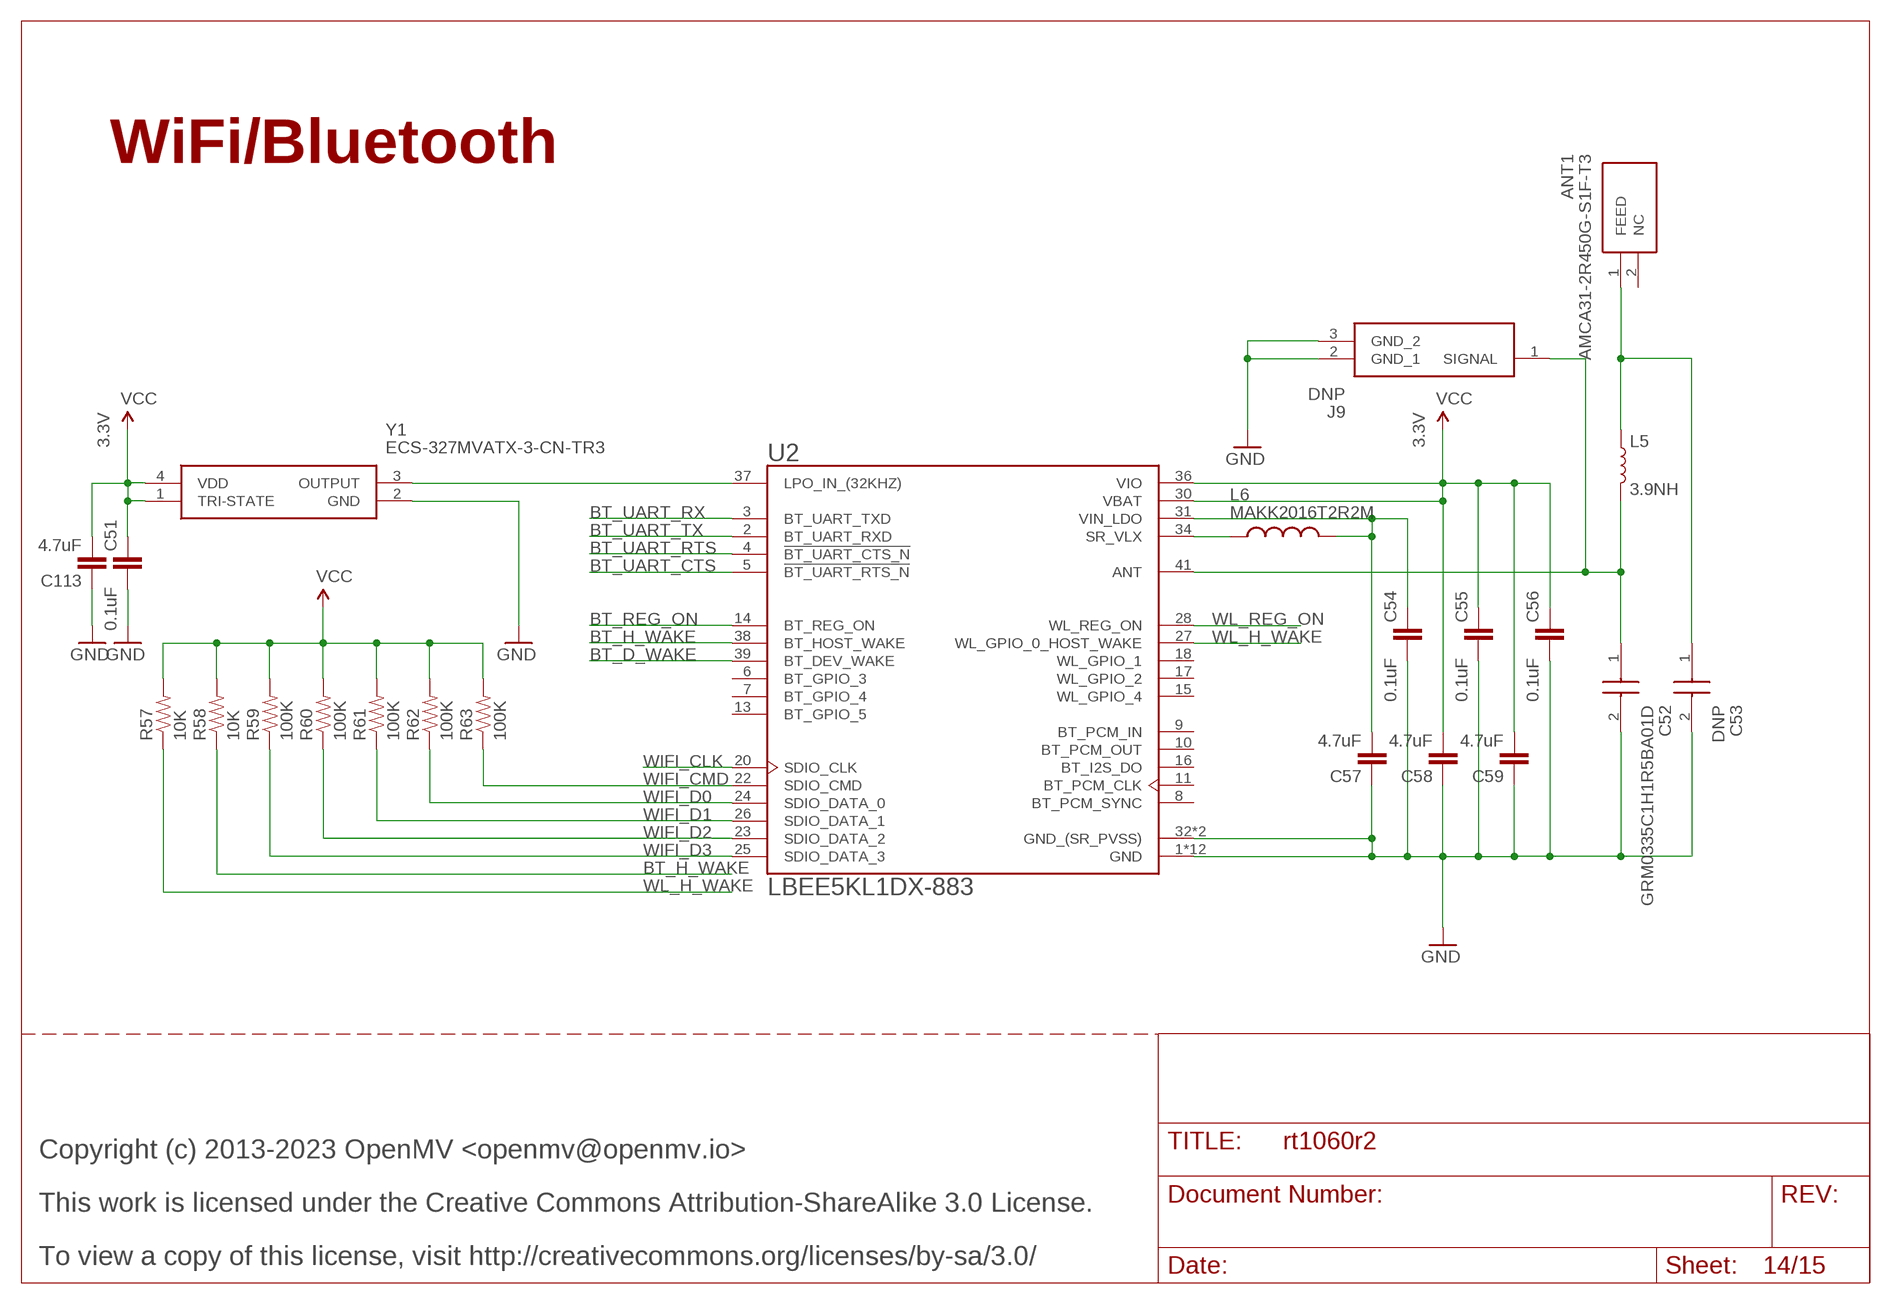
[diagram p13: schematic, sheet 14]
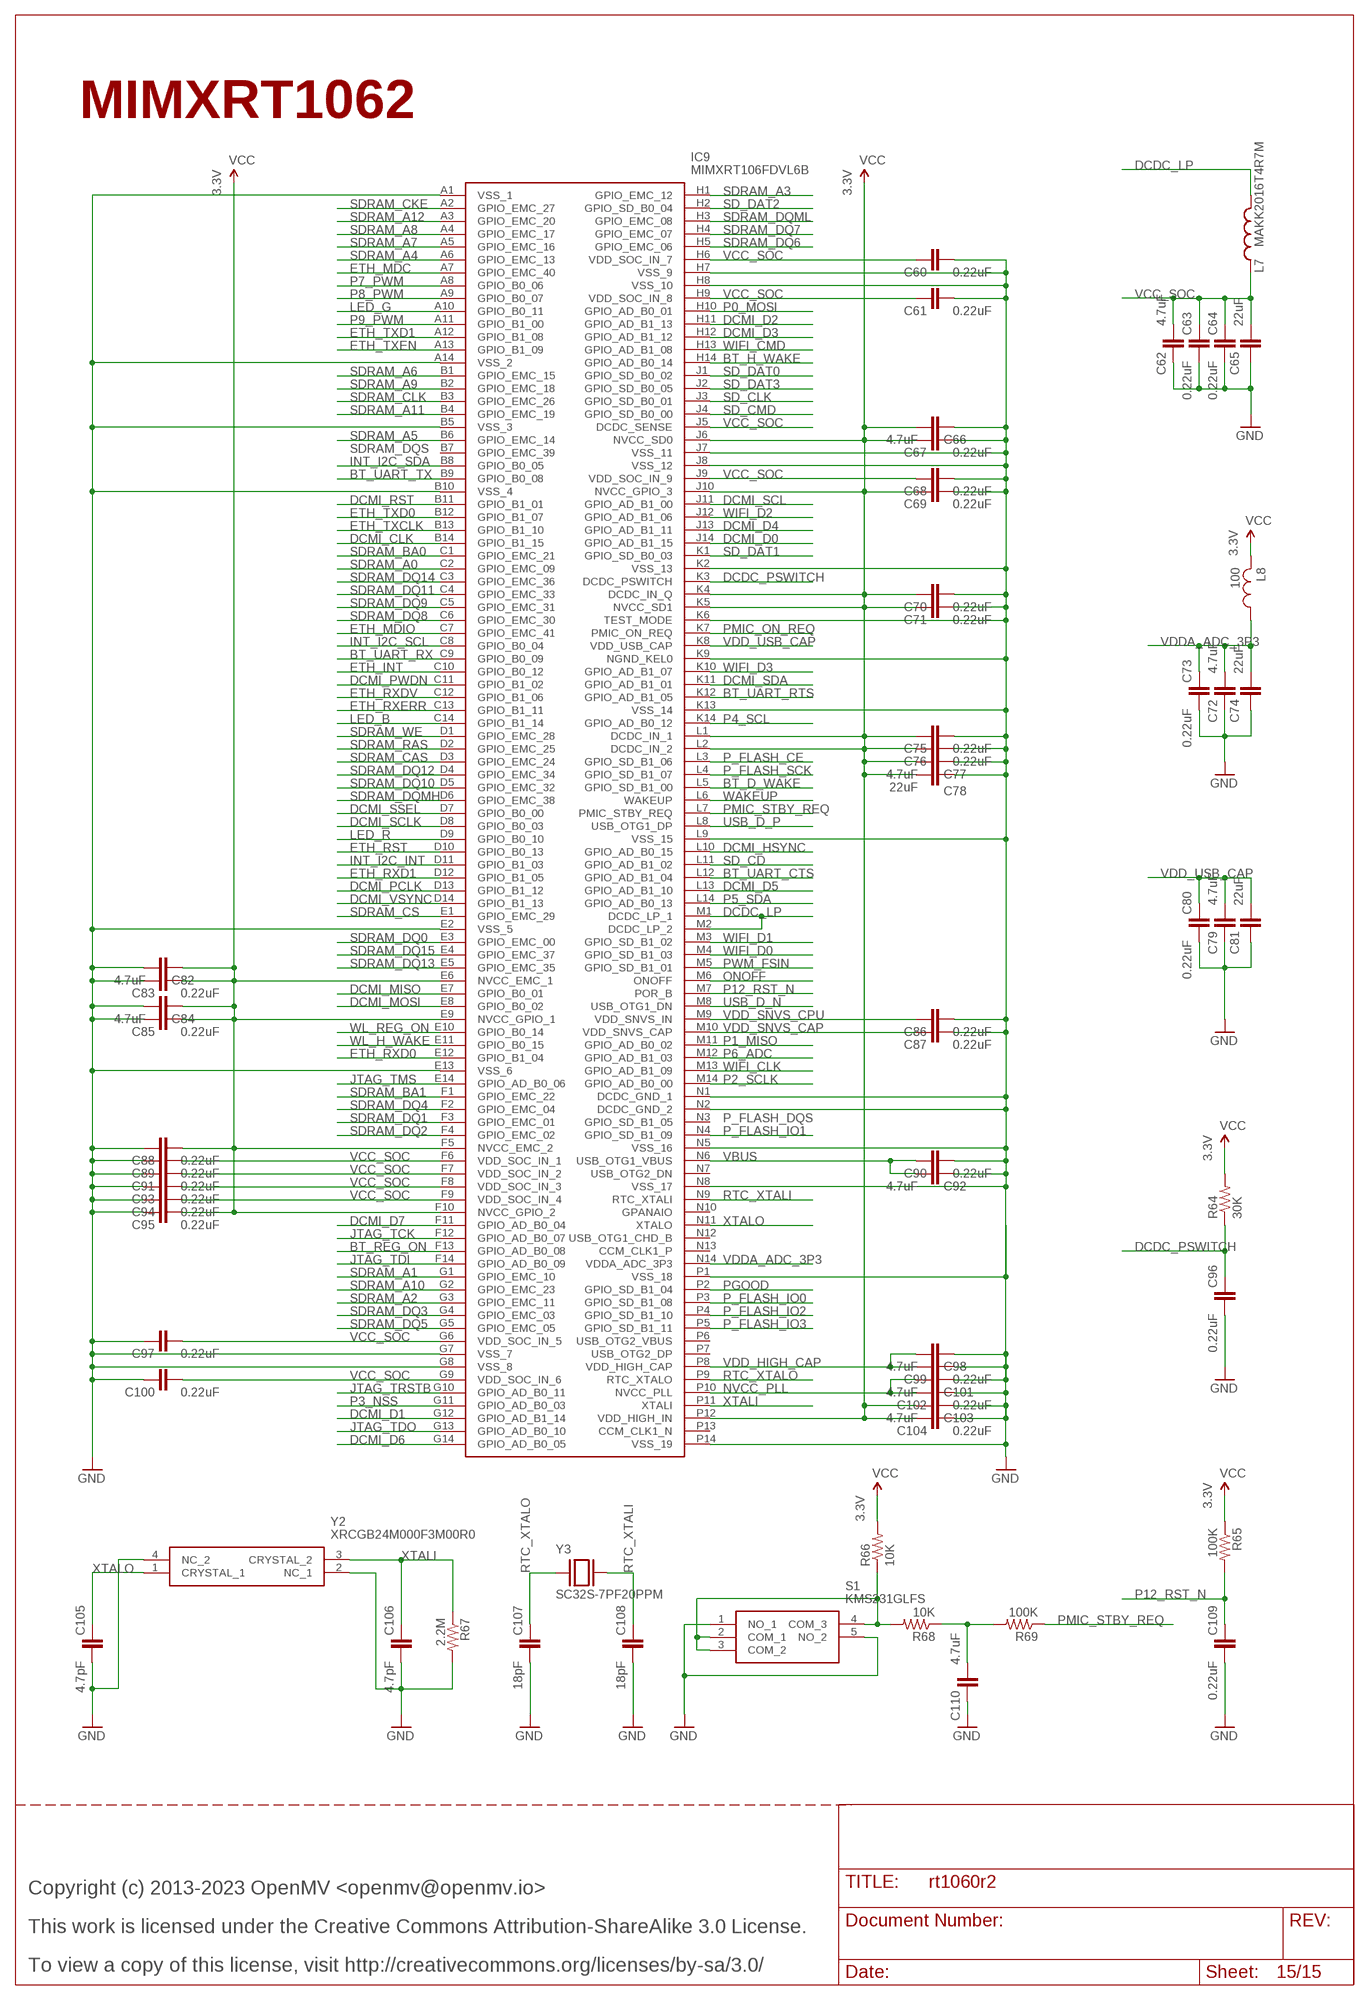
[diagram p14: schematic, sheet 15]

(export (version "E")
  (design (tool "Eeschema 10.0.6"))
  (components
    (comp (ref "C8")
      (value "4.7uF")
      (footprint "eagle-import:0402")
      (fields (field (name "MPN") "JMK105BBJ475MV-F"))
      (libsource (lib "eagle-import") (part "CAP_0402"))
    )
    (comp (ref "C9")
      (value "4.7uF")
      (footprint "eagle-import:0402")
      (fields (field (name "MPN") "JMK105BBJ475MV-F"))
      (libsource (lib "eagle-import") (part "CAP_0402"))
    )
    (comp (ref "D15")
      (value "BAT54CLT3G")
      (footprint "eagle-import:SOT96P237X111-3N")
      (fields (field (name "MOUSER_PART_NUMBER") "863-BAT54CLT3G"))
      (libsource (lib "eagle-import") (part "BAT54CLT3G"))
    )
    (comp (ref "IC2")
      (value "TCR2LF33,LM_CT")
      (footprint "eagle-import:TCR2LF33LMCT")
      (fields
        (field (name "MANUFACTURER_PART_NUMBER") "TCR2LF33,LM(CT")
        (field (name "MOUSER_PART_NUMBER") "757-TCR2LF33LMCT")
      )
      (libsource (lib "eagle-import") (part "TCR2LF33,LM_CT"))
    )
    (comp (ref "Q2")
      (value "2N7002KW_R1_00001")
      (footprint "eagle-import:SOT65P210X110-3N")
      (fields (field (name "MOUSER_PART_NUMBER") "241-2N7002KWR100001"))
      (libsource (lib "eagle-import") (part "2N7002KW_R1_00001"))
    )
    (comp (ref "Q3")
      (value "2N7002KW_R1_00001")
      (footprint "eagle-import:SOT65P210X110-3N")
      (fields (field (name "MOUSER_PART_NUMBER") "241-2N7002KWR100001"))
      (libsource (lib "eagle-import") (part "2N7002KW_R1_00001"))
    )
    (comp (ref "R14")
      (value "100K")
      (footprint "eagle-import:0402")
      (fields (field (name "MPN") "AC0402FR-07100KL"))
      (libsource (lib "eagle-import") (part "RES_0402"))
    )
    (comp (ref "R15")
      (value "100K")
      (footprint "eagle-import:0402")
      (fields (field (name "MPN") "AC0402FR-07100KL"))
      (libsource (lib "eagle-import") (part "RES_0402"))
    )
    (comp (ref "R70")
      (value "10K")
      (footprint "eagle-import:0402")
      (fields (field (name "MPN") "AC0402FR-1310KL"))
      (libsource (lib "eagle-import") (part "RES_0402"))
    )
    (comp (ref "S2")
      (value "KMS231GLFS")
      (footprint "eagle-import:KMS231GLFS")
      (fields (field (name "MOUSER_PART_NUMBER") "611-KMS231GLFS"))
      (libsource (lib "eagle-import") (part "KMS231GLFS"))
    )
    (comp (ref "TP1")
      (value "TPTP10R")
      (footprint "eagle-import:TP10R")
      (libsource (lib "eagle-import") (part "TPTP10R"))
    )
    (comp (ref "TP2")
      (value "TPTP10R")
      (footprint "eagle-import:TP10R")
      (libsource (lib "eagle-import") (part "TPTP10R"))
    )
    (comp (ref "D8")
      (value "CPDQT5V0HE-HF")
      (footprint "eagle-import:CPDQT5V0HEHF")
      (libsource (lib "eagle-import") (part "CPDQT5V0HE-HF"))
    )
    (comp (ref "D9")
      (value "CPDQT5V0HE-HF")
      (footprint "eagle-import:CPDQT5V0HEHF")
      (libsource (lib "eagle-import") (part "CPDQT5V0HE-HF"))
    )
    (comp (ref "D10")
      (value "CPDQT5V0HE-HF")
      (footprint "eagle-import:CPDQT5V0HEHF")
      (libsource (lib "eagle-import") (part "CPDQT5V0HE-HF"))
    )
    (comp (ref "D11")
      (value "CPDQT5V0HE-HF")
      (footprint "eagle-import:CPDQT5V0HEHF")
      (libsource (lib "eagle-import") (part "CPDQT5V0HE-HF"))
    )
    (comp (ref "D12")
      (value "CPDQT5V0HE-HF")
      (footprint "eagle-import:CPDQT5V0HEHF")
      (libsource (lib "eagle-import") (part "CPDQT5V0HE-HF"))
    )
    (comp (ref "D13")
      (value "CPDQT5V0HE-HF")
      (footprint "eagle-import:CPDQT5V0HEHF")
      (libsource (lib "eagle-import") (part "CPDQT5V0HE-HF"))
    )
    (comp (ref "FL3")
      (value "EMIF06-1005M12")
      (footprint "eagle-import:SON40P150X250X65-13N")
      (fields (field (name "MOUSER_PART_NUMBER") "511-EMIF06-1005M12"))
      (libsource (lib "eagle-import") (part "EMIF06-1005M12"))
    )
    (comp (ref "FL4")
      (value "EMIF06-1005M12")
      (footprint "eagle-import:SON40P150X250X65-13N")
      (fields (field (name "MOUSER_PART_NUMBER") "511-EMIF06-1005M12"))
      (libsource (lib "eagle-import") (part "EMIF06-1005M12"))
    )
    (comp (ref "J4")
      (value "DNP")
      (footprint "eagle-import:1X08")
      (libsource (lib "eagle-import") (part "CONN_08{dblquote}"))
    )
    (comp (ref "J5")
      (value "DNP")
      (footprint "eagle-import:1X08")
      (libsource (lib "eagle-import") (part "CONN_08{dblquote}"))
    )
    (comp (ref "J6")
      (value "DNP")
      (footprint "eagle-import:1X08")
      (libsource (lib "eagle-import") (part "CONN_08{dblquote}"))
    )
    (comp (ref "J7")
      (value "DNP")
      (footprint "eagle-import:1X08")
      (libsource (lib "eagle-import") (part "CONN_08{dblquote}"))
    )
    (comp (ref "R44")
      (value "0")
      (footprint "eagle-import:0402")
      (fields (field (name "MPN") "RC0402JR-070RL"))
      (libsource (lib "eagle-import") (part "RES_0402"))
    )
    (comp (ref "R45")
      (value "0")
      (footprint "eagle-import:0402")
      (fields (field (name "MPN") "RC0402JR-070RL"))
      (libsource (lib "eagle-import") (part "RES_0402"))
    )
    (comp (ref "R46")
      (value "10K")
      (footprint "eagle-import:0402")
      (fields (field (name "MPN") "AC0402FR-1310KL"))
      (libsource (lib "eagle-import") (part "RES_0402"))
    )
    (comp (ref "C42")
      (value "4.7uF")
      (footprint "eagle-import:0402")
      (fields (field (name "MPN") "JMK105BBJ475MV-F"))
      (libsource (lib "eagle-import") (part "CAP_0402"))
    )
    (comp (ref "C43")
      (value "4.7uF")
      (footprint "eagle-import:0402")
      (fields (field (name "MPN") "JMK105BBJ475MV-F"))
      (libsource (lib "eagle-import") (part "CAP_0402"))
    )
    (comp (ref "C44")
      (value "4.7uF")
      (footprint "eagle-import:0402")
      (fields (field (name "MPN") "JMK105BBJ475MV-F"))
      (libsource (lib "eagle-import") (part "CAP_0402"))
    )
    (comp (ref "C45")
      (value "22uF")
      (footprint "eagle-import:0805")
      (fields (field (name "MPN") "CL21A226MQQNNNE"))
      (libsource (lib "eagle-import") (part "22UF-0805-6.3V-20%"))
    )
    (comp (ref "C46")
      (value "0.1uF")
      (footprint "eagle-import:0402")
      (fields (field (name "MPN") "C0402C104Z4VAC"))
      (libsource (lib "eagle-import") (part "CAP_0402"))
    )
    (comp (ref "C47")
      (value "0.1uF")
      (footprint "eagle-import:0402")
      (fields (field (name "MPN") "C0402C104Z4VAC"))
      (libsource (lib "eagle-import") (part "CAP_0402"))
    )
    (comp (ref "C48")
      (value "4.7uF")
      (footprint "eagle-import:0402")
      (fields (field (name "MPN") "JMK105BBJ475MV-F"))
      (libsource (lib "eagle-import") (part "CAP_0402"))
    )
    (comp (ref "C49")
      (value "22uF")
      (footprint "eagle-import:0805")
      (fields (field (name "MPN") "CL21A226MQQNNNE"))
      (libsource (lib "eagle-import") (part "22UF-0805-6.3V-20%"))
    )
    (comp (ref "C50")
      (value "0.1uF")
      (footprint "eagle-import:0402")
      (fields (field (name "MPN") "C0402C104Z4VAC"))
      (libsource (lib "eagle-import") (part "CAP_0402"))
    )
    (comp (ref "FD1")
      (value "FIDUCIAL1X2")
      (footprint "eagle-import:FIDUCIAL-1X2")
      (libsource (lib "eagle-import") (part "FIDUCIAL1X2"))
    )
    (comp (ref "FD2")
      (value "FIDUCIAL1X2")
      (footprint "eagle-import:FIDUCIAL-1X2")
      (libsource (lib "eagle-import") (part "FIDUCIAL1X2"))
    )
    (comp (ref "FD3")
      (value "FIDUCIAL1X2")
      (footprint "eagle-import:FIDUCIAL-1X2")
      (libsource (lib "eagle-import") (part "FIDUCIAL1X2"))
    )
    (comp (ref "FD4")
      (value "FIDUCIAL1X2")
      (footprint "eagle-import:FIDUCIAL-1X2")
      (libsource (lib "eagle-import") (part "FIDUCIAL1X2"))
    )
    (comp (ref "FD5")
      (value "FIDUCIAL1X2")
      (footprint "eagle-import:FIDUCIAL-1X2")
      (libsource (lib "eagle-import") (part "FIDUCIAL1X2"))
    )
    (comp (ref "FD6")
      (value "FIDUCIAL1X2")
      (footprint "eagle-import:FIDUCIAL-1X2")
      (libsource (lib "eagle-import") (part "FIDUCIAL1X2"))
    )
    (comp (ref "FD7")
      (value "FIDUCIAL1X2")
      (footprint "eagle-import:FIDUCIAL-1X2")
      (libsource (lib "eagle-import") (part "FIDUCIAL1X2"))
    )
    (comp (ref "FD8")
      (value "FIDUCIAL1X2")
      (footprint "eagle-import:FIDUCIAL-1X2")
      (libsource (lib "eagle-import") (part "FIDUCIAL1X2"))
    )
    (comp (ref "H1")
      (value "MOUNT-PAD-ROUND2.8")
      (footprint "eagle-import:2,8-PAD")
      (libsource (lib "eagle-import") (part "MOUNT-PAD-ROUND2.8"))
    )
    (comp (ref "H2")
      (value "MOUNT-PAD-ROUND2.8")
      (footprint "eagle-import:2,8-PAD")
      (libsource (lib "eagle-import") (part "MOUNT-PAD-ROUND2.8"))
    )
    (comp (ref "IC8")
      (value "KSZ8081RNDCA-TR")
      (footprint "eagle-import:QFN50P400X400X90-25N")
      (fields (field (name "MOUSER_PART_NUMBER") "998-KSZ8081RNDCATR"))
      (libsource (lib "eagle-import") (part "KSZ8081RNDCA-TR"))
    )
    (comp (ref "L4")
      (value "100")
      (footprint "eagle-import:0402")
      (fields (field (name "MPN") "MFBM1V1005-101-R"))
      (libsource (lib "eagle-import") (part "INDUCTOR_0402"))
    )
    (comp (ref "M1")
      (value "9774030151R")
      (footprint "eagle-import:9774030151R")
      (libsource (lib "eagle-import") (part "9774030151R"))
    )
    (comp (ref "M2")
      (value "9774030151R")
      (footprint "eagle-import:9774030151R")
      (libsource (lib "eagle-import") (part "9774030151R"))
    )
    (comp (ref "R52")
      (value "100K")
      (footprint "eagle-import:0402")
      (fields (field (name "MPN") "AC0402FR-07100KL"))
      (libsource (lib "eagle-import") (part "RES_0402"))
    )
    (comp (ref "R53")
      (value "220")
      (footprint "eagle-import:0402")
      (fields (field (name "MPN") "CRGCQ0402F220R"))
      (libsource (lib "eagle-import") (part "RES_0402"))
    )
    (comp (ref "R54")
      (value "1K")
      (footprint "eagle-import:0402")
      (fields (field (name "MPN") "CRCW04021K00FKEDC"))
      (libsource (lib "eagle-import") (part "RES_0402"))
    )
    (comp (ref "R55")
      (value "6.49K")
      (footprint "eagle-import:0402")
      (fields (field (name "MPN") "CR0402-FX-6491GLF"))
      (libsource (lib "eagle-import") (part "RES_0402"))
    )
    (comp (ref "R56")
      (value "1K")
      (footprint "eagle-import:0402")
      (fields (field (name "MPN") "CRCW04021K00FKEDC"))
      (libsource (lib "eagle-import") (part "RES_0402"))
    )
    (comp (ref "C27")
      (value "4.7uF")
      (footprint "eagle-import:0402")
      (fields (field (name "MPN") "JMK105BBJ475MV-F"))
      (libsource (lib "eagle-import") (part "CAP_0402"))
    )
    (comp (ref "C28")
      (value "4.7uF")
      (footprint "eagle-import:0402")
      (fields (field (name "MPN") "JMK105BBJ475MV-F"))
      (libsource (lib "eagle-import") (part "CAP_0402"))
    )
    (comp (ref "C29")
      (value "0.1uF")
      (footprint "eagle-import:0402")
      (fields (field (name "MPN") "C0402C104Z4VAC"))
      (libsource (lib "eagle-import") (part "CAP_0402"))
    )
    (comp (ref "C30")
      (value "0.1uF")
      (footprint "eagle-import:0402")
      (fields (field (name "MPN") "C0402C104Z4VAC"))
      (libsource (lib "eagle-import") (part "CAP_0402"))
    )
    (comp (ref "C111")
      (value "0.1uF")
      (footprint "eagle-import:0402")
      (fields (field (name "MPN") "C0402C104Z4VAC"))
      (libsource (lib "eagle-import") (part "CAP_0402"))
    )
    (comp (ref "C112")
      (value "4.7uF")
      (footprint "eagle-import:0402")
      (fields (field (name "MPN") "JMK105BBJ475MV-F"))
      (libsource (lib "eagle-import") (part "CAP_0402"))
    )
    (comp (ref "IC6")
      (value "SE050C1HQ1_Z01SCZ")
      (footprint "eagle-import:QFN40P300X300X33-21N")
      (fields
        (field (name "MANUFACTURER_PART_NUMBER") "SE050C1HQ1/Z01SCZ")
        (field (name "MOUSER_PART_NUMBER") "771-SE050C1HQ1Z01SCZ")
      )
      (libsource (lib "eagle-import") (part "SE050C1HQ1_Z01SCZ"))
    )
    (comp (ref "IC7")
      (value "MXC4005XC")
      (footprint "eagle-import:MXC4005XC")
      (fields (field (name "MOUSER_PART_NUMBER") "438-MXC4005XC"))
      (libsource (lib "eagle-import") (part "MXC4005XC"))
    )
    (comp (ref "R27")
      (value "2.7K")
      (footprint "eagle-import:0402")
      (fields (field (name "MPN") "AC0402JR-072K7L"))
      (libsource (lib "eagle-import") (part "RES_0402"))
    )
    (comp (ref "R28")
      (value "2.7K")
      (footprint "eagle-import:0402")
      (fields (field (name "MPN") "AC0402JR-072K7L"))
      (libsource (lib "eagle-import") (part "RES_0402"))
    )
    (comp (ref "R29")
      (value "2.7K")
      (footprint "eagle-import:0402")
      (fields (field (name "MPN") "AC0402JR-072K7L"))
      (libsource (lib "eagle-import") (part "RES_0402"))
    )
    (comp (ref "C31")
      (value "4.7uF")
      (footprint "eagle-import:0402")
      (fields (field (name "MPN") "JMK105BBJ475MV-F"))
      (libsource (lib "eagle-import") (part "CAP_0402"))
    )
    (comp (ref "C32")
      (value "22uF")
      (footprint "eagle-import:0805")
      (fields (field (name "MPN") "CL21A226MQQNNNE"))
      (libsource (lib "eagle-import") (part "22UF-0805-6.3V-20%"))
    )
    (comp (ref "C33")
      (value "0.1uF")
      (footprint "eagle-import:0402")
      (fields (field (name "MPN") "C0402C104Z4VAC"))
      (libsource (lib "eagle-import") (part "CAP_0402"))
    )
    (comp (ref "D6")
      (value "CPDQT5V0HE-HF")
      (footprint "eagle-import:CPDQT5V0HEHF")
      (libsource (lib "eagle-import") (part "CPDQT5V0HE-HF"))
    )
    (comp (ref "D7")
      (value "CPDQT5V0HE-HF")
      (footprint "eagle-import:CPDQT5V0HEHF")
      (libsource (lib "eagle-import") (part "CPDQT5V0HE-HF"))
    )
    (comp (ref "FL2")
      (value "EMIF06-1005M12")
      (footprint "eagle-import:SON40P150X250X65-13N")
      (fields (field (name "MOUSER_PART_NUMBER") "511-EMIF06-1005M12"))
      (libsource (lib "eagle-import") (part "EMIF06-1005M12"))
    )
    (comp (ref "J2")
      (value "USD-1040310811")
      (footprint "eagle-import:1040310811")
      (fields (field (name "MPN") "104031-0811"))
      (libsource (lib "eagle-import") (part "USD-1040310811"))
    )
    (comp (ref "R30")
      (value "100K")
      (footprint "eagle-import:0402")
      (fields (field (name "MPN") "AC0402FR-07100KL"))
      (libsource (lib "eagle-import") (part "RES_0402"))
    )
    (comp (ref "R31")
      (value "100K")
      (footprint "eagle-import:0402")
      (fields (field (name "MPN") "AC0402FR-07100KL"))
      (libsource (lib "eagle-import") (part "RES_0402"))
    )
    (comp (ref "R32")
      (value "100K")
      (footprint "eagle-import:0402")
      (fields (field (name "MPN") "AC0402FR-07100KL"))
      (libsource (lib "eagle-import") (part "RES_0402"))
    )
    (comp (ref "R33")
      (value "100K")
      (footprint "eagle-import:0402")
      (fields (field (name "MPN") "AC0402FR-07100KL"))
      (libsource (lib "eagle-import") (part "RES_0402"))
    )
    (comp (ref "R34")
      (value "100K")
      (footprint "eagle-import:0402")
      (fields (field (name "MPN") "AC0402FR-07100KL"))
      (libsource (lib "eagle-import") (part "RES_0402"))
    )
    (comp (ref "R35")
      (value "100K")
      (footprint "eagle-import:0402")
      (fields (field (name "MPN") "AC0402FR-07100KL"))
      (libsource (lib "eagle-import") (part "RES_0402"))
    )
    (comp (ref "C25")
      (value "4.7uF")
      (footprint "eagle-import:0402")
      (fields (field (name "MPN") "JMK105BBJ475MV-F"))
      (libsource (lib "eagle-import") (part "CAP_0402"))
    )
    (comp (ref "C26")
      (value "0.1uF")
      (footprint "eagle-import:0402")
      (fields (field (name "MPN") "C0402C104Z4VAC"))
      (libsource (lib "eagle-import") (part "CAP_0402"))
    )
    (comp (ref "D5")
      (value "UHD1110-FKA-CL1A13R3Q1BBQFMF3")
      (footprint "eagle-import:LED_UHD1110-FKA-CL1A13R3Q1BBQFMF3")
      (fields (field (name "MF") "Cree Inc.") (field (name "MPN") "UHD1110-FKA-CL1A13r3q1BBQFMF3"))
      (libsource (lib "eagle-import") (part "UHD1110-FKA-CL1A13R3Q1BBQFMF3"))
    )
    (comp (ref "IC5")
      (value "IS25LP128F-JKLE-TR")
      (footprint "eagle-import:SON127P500X595X80-9N")
      (description "NOR Flash 128M 2.3-3.6V 166Mhz Serial NOR Flash")
      (fields
        (field (name "MANUFACTURER_PART_NUMBER") "IS25LP064D-JKLE-TR")
        (field (name "MOUSER_PART_NUMBER") "870-5LP064D-JKLE-TR")
        (field (name "MANUFACTURER_PART_NUMBER_1") "IS25LP128F-JKLE-TR")
        (field (name "MOUSER_PART_NUMBER_1") "870-5LP128F-JKLE-TR")
        (field (name "MOUSER_PRICE-STOCK") "https://www.mouser.com/ProductDetail/ISSI/IS25LP128F-JKLE-TR?qs=F5EMLAvA7IC8MN2X519UUw%3D%3D")
      )
      (libsource (lib "eagle-import") (part "IS25LP064D-JKLE-TR"))
    )
    (comp (ref "R20")
      (value "100K")
      (footprint "eagle-import:0402")
      (fields (field (name "MPN") "AC0402FR-07100KL"))
      (libsource (lib "eagle-import") (part "RES_0402"))
    )
    (comp (ref "R21")
      (value "1K")
      (footprint "eagle-import:0402")
      (fields (field (name "MPN") "CRCW04021K00FKEDC"))
      (libsource (lib "eagle-import") (part "RES_0402"))
    )
    (comp (ref "R22")
      (value "10K")
      (footprint "eagle-import:0402")
      (fields (field (name "MPN") "AC0402FR-1310KL"))
      (libsource (lib "eagle-import") (part "RES_0402"))
    )
    (comp (ref "R23")
      (value "5.1K")
      (footprint "eagle-import:0402")
      (fields (field (name "MPN") "RC0402JR-075K1L"))
      (libsource (lib "eagle-import") (part "RES_0402"))
    )
    (comp (ref "R24")
      (value "10K")
      (footprint "eagle-import:0402")
      (fields (field (name "MPN") "AC0402FR-1310KL"))
      (libsource (lib "eagle-import") (part "RES_0402"))
    )
    (comp (ref "R25")
      (value "10K")
      (footprint "eagle-import:0402")
      (fields (field (name "MPN") "AC0402FR-1310KL"))
      (libsource (lib "eagle-import") (part "RES_0402"))
    )
    (comp (ref "R26")
      (value "10K")
      (footprint "eagle-import:0402")
      (fields (field (name "MPN") "AC0402FR-1310KL"))
      (libsource (lib "eagle-import") (part "RES_0402"))
    )
    (comp (ref "ANT1")
      (value "AMCA31-2R450G-S1F-T3")
      (footprint "eagle-import:ANTC3216X140N")
      (fields (field (name "MOUSER_PART_NUMBER") "815-CA312R450GS1FT3"))
      (libsource (lib "eagle-import") (part "AMCA31-2R450G-S1F-T3"))
    )
    (comp (ref "C51")
      (value "0.1uF")
      (footprint "eagle-import:0402")
      (fields (field (name "MPN") "C0402C104Z4VAC"))
      (libsource (lib "eagle-import") (part "CAP_0402"))
    )
    (comp (ref "C52")
      (value "GRM0335C1H1R5BA01D")
      (footprint "eagle-import:CAPC0603X33N")
      (fields (field (name "MOUSER_PART_NUMBER") "81-GRM0335C1H1R5BA1D"))
      (libsource (lib "eagle-import") (part "GRM0335C1H1R5BA01D"))
    )
    (comp (ref "C53")
      (value "DNP")
      (footprint "eagle-import:CAPC0603X33N")
      (fields
        (field (name "MANUFACTURER_PART_NUMBER") "GRM0335C1H1R5BA01D")
        (field (name "MOUSER_PART_NUMBER") "81-GRM0335C1H1R5BA1D")
      )
      (libsource (lib "eagle-import") (part "GRM0335C1H1R5BA01D"))
    )
    (comp (ref "C54")
      (value "0.1uF")
      (footprint "eagle-import:0402")
      (fields (field (name "MPN") "C0402C104Z4VAC"))
      (libsource (lib "eagle-import") (part "CAP_0402"))
    )
    (comp (ref "C55")
      (value "0.1uF")
      (footprint "eagle-import:0402")
      (fields (field (name "MPN") "C0402C104Z4VAC"))
      (libsource (lib "eagle-import") (part "CAP_0402"))
    )
    (comp (ref "C56")
      (value "0.1uF")
      (footprint "eagle-import:0402")
      (fields (field (name "MPN") "C0402C104Z4VAC"))
      (libsource (lib "eagle-import") (part "CAP_0402"))
    )
    (comp (ref "C57")
      (value "4.7uF")
      (footprint "eagle-import:0402")
      (fields (field (name "MPN") "JMK105BBJ475MV-F"))
      (libsource (lib "eagle-import") (part "CAP_0402"))
    )
    (comp (ref "C58")
      (value "4.7uF")
      (footprint "eagle-import:0402")
      (fields (field (name "MPN") "JMK105BBJ475MV-F"))
      (libsource (lib "eagle-import") (part "CAP_0402"))
    )
    (comp (ref "C59")
      (value "4.7uF")
      (footprint "eagle-import:0402")
      (fields (field (name "MPN") "JMK105BBJ475MV-F"))
      (libsource (lib "eagle-import") (part "CAP_0402"))
    )
    (comp (ref "C113")
      (value "4.7uF")
      (footprint "eagle-import:0402")
      (fields (field (name "MPN") "JMK105BBJ475MV-F"))
      (libsource (lib "eagle-import") (part "CAP_0402"))
    )
    (comp (ref "J9")
      (value "DNP")
      (footprint "eagle-import:23370191")
      (fields
        (field (name "MANUFACTURER_PART_NUMBER") "2337019-1")
        (field (name "MOUSER_PART_NUMBER") "571-2337019-1")
      )
      (libsource (lib "eagle-import") (part "2337019-1"))
    )
    (comp (ref "L5")
      (value "3.9NH")
      (footprint "eagle-import:0402")
      (fields (field (name "MPN") "L-07C3N9SV6T"))
      (libsource (lib "eagle-import") (part "INDUCTOR-0402-3.9NH"))
    )
    (comp (ref "L6")
      (value "MAKK2016T2R2M")
      (footprint "eagle-import:INDC2016X100N")
      (fields (field (name "MF") "Taiyo Yuden"))
      (libsource (lib "eagle-import") (part "MAKK2016T2R2M"))
    )
    (comp (ref "R57")
      (value "10K")
      (footprint "eagle-import:0402")
      (fields (field (name "MPN") "AC0402FR-1310KL"))
      (libsource (lib "eagle-import") (part "RES_0402"))
    )
    (comp (ref "R58")
      (value "10K")
      (footprint "eagle-import:0402")
      (fields (field (name "MPN") "AC0402FR-1310KL"))
      (libsource (lib "eagle-import") (part "RES_0402"))
    )
    (comp (ref "R59")
      (value "100K")
      (footprint "eagle-import:0402")
      (fields (field (name "MPN") "AC0402FR-07100KL"))
      (libsource (lib "eagle-import") (part "RES_0402"))
    )
    (comp (ref "R60")
      (value "100K")
      (footprint "eagle-import:0402")
      (fields (field (name "MPN") "AC0402FR-07100KL"))
      (libsource (lib "eagle-import") (part "RES_0402"))
    )
    (comp (ref "R61")
      (value "100K")
      (footprint "eagle-import:0402")
      (fields (field (name "MPN") "AC0402FR-07100KL"))
      (libsource (lib "eagle-import") (part "RES_0402"))
    )
    (comp (ref "R62")
      (value "100K")
      (footprint "eagle-import:0402")
      (fields (field (name "MPN") "AC0402FR-07100KL"))
      (libsource (lib "eagle-import") (part "RES_0402"))
    )
    (comp (ref "R63")
      (value "100K")
      (footprint "eagle-import:0402")
      (fields (field (name "MPN") "AC0402FR-07100KL"))
      (libsource (lib "eagle-import") (part "RES_0402"))
    )
    (comp (ref "U2")
      (value "LBEE5KL1DX-883")
      (footprint "eagle-import:XCVR_LBEE5KL1DX-TEMP")
      (fields (field (name "MF") "Murata Electronics") (field (name "MP") "LBEE5KL1DX-TEMP"))
      (libsource (lib "eagle-import") (part "LBEE5KL1DX-TEMP"))
    )
    (comp (ref "Y1")
      (value "ECS-327MVATX-3-CN-TR3")
      (footprint "eagle-import:ECS327MVATX3CNTR3")
      (fields (field (name "MOUSER_PART_NUMBER") "520-327MVATX-3-CNTR3"))
      (libsource (lib "eagle-import") (part "ECS-327MVATX-3-CN-TR3"))
    )
    (comp (ref "C60")
      (value "0.22uF")
      (footprint "eagle-import:C0201")
      (fields (field (name "MPN") "GRM033R60J224ME15D"))
      (libsource (lib "eagle-import") (part "C-EUC0201"))
    )
    (comp (ref "C61")
      (value "0.22uF")
      (footprint "eagle-import:C0201")
      (fields (field (name "MPN") "GRM033R60J224ME15D"))
      (libsource (lib "eagle-import") (part "C-EUC0201"))
    )
    (comp (ref "C62")
      (value "4.7uF")
      (footprint "eagle-import:0402")
      (fields (field (name "MPN") "JMK105BBJ475MV-F"))
      (libsource (lib "eagle-import") (part "CAP_0402"))
    )
    (comp (ref "C63")
      (value "0.22uF")
      (footprint "eagle-import:C0201")
      (fields (field (name "MPN") "GRM033R60J224ME15D"))
      (libsource (lib "eagle-import") (part "C-EUC0201"))
    )
    (comp (ref "C64")
      (value "0.22uF")
      (footprint "eagle-import:C0201")
      (fields (field (name "MPN") "GRM033R60J224ME15D"))
      (libsource (lib "eagle-import") (part "C-EUC0201"))
    )
    (comp (ref "C65")
      (value "22uF")
      (footprint "eagle-import:0805")
      (fields (field (name "MPN") "CL21A226MQQNNNE"))
      (libsource (lib "eagle-import") (part "22UF-0805-6.3V-20%"))
    )
    (comp (ref "C66")
      (value "4.7uF")
      (footprint "eagle-import:0402")
      (fields (field (name "MPN") "JMK105BBJ475MV-F"))
      (libsource (lib "eagle-import") (part "CAP_0402"))
    )
    (comp (ref "C67")
      (value "0.22uF")
      (footprint "eagle-import:C0201")
      (fields (field (name "MPN") "GRM033R60J224ME15D"))
      (libsource (lib "eagle-import") (part "C-EUC0201"))
    )
    (comp (ref "C68")
      (value "0.22uF")
      (footprint "eagle-import:C0201")
      (fields (field (name "MPN") "GRM033R60J224ME15D"))
      (libsource (lib "eagle-import") (part "C-EUC0201"))
    )
    (comp (ref "C69")
      (value "0.22uF")
      (footprint "eagle-import:C0201")
      (fields (field (name "MPN") "GRM033R60J224ME15D"))
      (libsource (lib "eagle-import") (part "C-EUC0201"))
    )
    (comp (ref "C70")
      (value "0.22uF")
      (footprint "eagle-import:C0201")
      (fields (field (name "MPN") "GRM033R60J224ME15D"))
      (libsource (lib "eagle-import") (part "C-EUC0201"))
    )
    (comp (ref "C71")
      (value "0.22uF")
      (footprint "eagle-import:C0201")
      (fields (field (name "MPN") "GRM033R60J224ME15D"))
      (libsource (lib "eagle-import") (part "C-EUC0201"))
    )
    (comp (ref "C72")
      (value "4.7uF")
      (footprint "eagle-import:0402")
      (fields (field (name "MPN") "JMK105BBJ475MV-F"))
      (libsource (lib "eagle-import") (part "CAP_0402"))
    )
    (comp (ref "C73")
      (value "0.22uF")
      (footprint "eagle-import:C0201")
      (fields (field (name "MPN") "GRM033R60J224ME15D"))
      (libsource (lib "eagle-import") (part "C-EUC0201"))
    )
    (comp (ref "C74")
      (value "22uF")
      (footprint "eagle-import:0805")
      (fields (field (name "MPN") "CL21A226MQQNNNE"))
      (libsource (lib "eagle-import") (part "22UF-0805-6.3V-20%"))
    )
    (comp (ref "C75")
      (value "0.22uF")
      (footprint "eagle-import:C0201")
      (fields (field (name "MPN") "GRM033R60J224ME15D"))
      (libsource (lib "eagle-import") (part "C-EUC0201"))
    )
    (comp (ref "C76")
      (value "0.22uF")
      (footprint "eagle-import:C0201")
      (fields (field (name "MPN") "GRM033R60J224ME15D"))
      (libsource (lib "eagle-import") (part "C-EUC0201"))
    )
    (comp (ref "C77")
      (value "4.7uF")
      (footprint "eagle-import:0402")
      (fields (field (name "MPN") "JMK105BBJ475MV-F"))
      (libsource (lib "eagle-import") (part "CAP_0402"))
    )
    (comp (ref "C78")
      (value "22uF")
      (footprint "eagle-import:0805")
      (fields (field (name "MPN") "CL21A226MQQNNNE"))
      (libsource (lib "eagle-import") (part "22UF-0805-6.3V-20%"))
    )
    (comp (ref "C79")
      (value "4.7uF")
      (footprint "eagle-import:0402")
      (fields (field (name "MPN") "JMK105BBJ475MV-F"))
      (libsource (lib "eagle-import") (part "CAP_0402"))
    )
    (comp (ref "C80")
      (value "0.22uF")
      (footprint "eagle-import:C0201")
      (fields (field (name "MPN") "GRM033R60J224ME15D"))
      (libsource (lib "eagle-import") (part "C-EUC0201"))
    )
    (comp (ref "C81")
      (value "22uF")
      (footprint "eagle-import:0805")
      (fields (field (name "MPN") "CL21A226MQQNNNE"))
      (libsource (lib "eagle-import") (part "22UF-0805-6.3V-20%"))
    )
    (comp (ref "C82")
      (value "4.7uF")
      (footprint "eagle-import:0402")
      (fields (field (name "MPN") "JMK105BBJ475MV-F"))
      (libsource (lib "eagle-import") (part "CAP_0402"))
    )
    (comp (ref "C83")
      (value "0.22uF")
      (footprint "eagle-import:C0201")
      (fields (field (name "MPN") "GRM033R60J224ME15D"))
      (libsource (lib "eagle-import") (part "C-EUC0201"))
    )
    (comp (ref "C84")
      (value "4.7uF")
      (footprint "eagle-import:0402")
      (fields (field (name "MPN") "JMK105BBJ475MV-F"))
      (libsource (lib "eagle-import") (part "CAP_0402"))
    )
    (comp (ref "C85")
      (value "0.22uF")
      (footprint "eagle-import:C0201")
      (fields (field (name "MPN") "GRM033R60J224ME15D"))
      (libsource (lib "eagle-import") (part "C-EUC0201"))
    )
    (comp (ref "C86")
      (value "0.22uF")
      (footprint "eagle-import:C0201")
      (fields (field (name "MPN") "GRM033R60J224ME15D"))
      (libsource (lib "eagle-import") (part "C-EUC0201"))
    )
    (comp (ref "C87")
      (value "0.22uF")
      (footprint "eagle-import:C0201")
      (fields (field (name "MPN") "GRM033R60J224ME15D"))
      (libsource (lib "eagle-import") (part "C-EUC0201"))
    )
    (comp (ref "C88")
      (value "0.22uF")
      (footprint "eagle-import:C0201")
      (fields (field (name "MPN") "GRM033R60J224ME15D"))
      (libsource (lib "eagle-import") (part "C-EUC0201"))
    )
    (comp (ref "C89")
      (value "0.22uF")
      (footprint "eagle-import:C0201")
      (fields (field (name "MPN") "GRM033R60J224ME15D"))
      (libsource (lib "eagle-import") (part "C-EUC0201"))
    )
    (comp (ref "C90")
      (value "0.22uF")
      (footprint "eagle-import:C0201")
      (fields (field (name "MPN") "GRM033R60J224ME15D"))
      (libsource (lib "eagle-import") (part "C-EUC0201"))
    )
    (comp (ref "C91")
      (value "0.22uF")
      (footprint "eagle-import:C0201")
      (fields (field (name "MPN") "GRM033R60J224ME15D"))
      (libsource (lib "eagle-import") (part "C-EUC0201"))
    )
    (comp (ref "C92")
      (value "4.7uF")
      (footprint "eagle-import:0402")
      (fields (field (name "MPN") "JMK105BBJ475MV-F"))
      (libsource (lib "eagle-import") (part "CAP_0402"))
    )
    (comp (ref "C93")
      (value "0.22uF")
      (footprint "eagle-import:C0201")
      (fields (field (name "MPN") "GRM033R60J224ME15D"))
      (libsource (lib "eagle-import") (part "C-EUC0201"))
    )
    (comp (ref "C94")
      (value "0.22uF")
      (footprint "eagle-import:C0201")
      (fields (field (name "MPN") "GRM033R60J224ME15D"))
      (libsource (lib "eagle-import") (part "C-EUC0201"))
    )
    (comp (ref "C95")
      (value "0.22uF")
      (footprint "eagle-import:C0201")
      (fields (field (name "MPN") "GRM033R60J224ME15D"))
      (libsource (lib "eagle-import") (part "C-EUC0201"))
    )
    (comp (ref "C96")
      (value "0.22uF")
      (footprint "eagle-import:C0201")
      (fields (field (name "MPN") "GRM033R60J224ME15D"))
      (libsource (lib "eagle-import") (part "C-EUC0201"))
    )
    (comp (ref "C97")
      (value "0.22uF")
      (footprint "eagle-import:C0201")
      (fields (field (name "MPN") "GRM033R60J224ME15D"))
      (libsource (lib "eagle-import") (part "C-EUC0201"))
    )
    (comp (ref "C98")
      (value "4.7uF")
      (footprint "eagle-import:0402")
      (fields (field (name "MPN") "JMK105BBJ475MV-F"))
      (libsource (lib "eagle-import") (part "CAP_0402"))
    )
    (comp (ref "C99")
      (value "0.22uF")
      (footprint "eagle-import:C0201")
      (fields (field (name "MPN") "GRM033R60J224ME15D"))
      (libsource (lib "eagle-import") (part "C-EUC0201"))
    )
    (comp (ref "C100")
      (value "0.22uF")
      (footprint "eagle-import:C0201")
      (fields (field (name "MPN") "GRM033R60J224ME15D"))
      (libsource (lib "eagle-import") (part "C-EUC0201"))
    )
    (comp (ref "C101")
      (value "4.7uF")
      (footprint "eagle-import:0402")
      (fields (field (name "MPN") "JMK105BBJ475MV-F"))
      (libsource (lib "eagle-import") (part "CAP_0402"))
    )
    (comp (ref "C102")
      (value "0.22uF")
      (footprint "eagle-import:C0201")
      (fields (field (name "MPN") "GRM033R60J224ME15D"))
      (libsource (lib "eagle-import") (part "C-EUC0201"))
    )
    (comp (ref "C103")
      (value "4.7uF")
      (footprint "eagle-import:0402")
      (fields (field (name "MPN") "JMK105BBJ475MV-F"))
      (libsource (lib "eagle-import") (part "CAP_0402"))
    )
    (comp (ref "C104")
      (value "0.22uF")
      (footprint "eagle-import:C0201")
      (fields (field (name "MPN") "GRM033R60J224ME15D"))
      (libsource (lib "eagle-import") (part "C-EUC0201"))
    )
    (comp (ref "C105")
      (value "4.7pF")
      (footprint "eagle-import:C0201")
      (fields (field (name "MPN") "GRM0335C1E4R7CA01D"))
      (libsource (lib "eagle-import") (part "C-EUC0201"))
    )
    (comp (ref "C106")
      (value "4.7pF")
      (footprint "eagle-import:C0201")
      (fields (field (name "MPN") "GRM0335C1E4R7CA01D"))
      (libsource (lib "eagle-import") (part "C-EUC0201"))
    )
    (comp (ref "C107")
      (value "18pF")
      (footprint "eagle-import:C0201")
      (fields (field (name "MPN") "GRM0335C1E180JA01D"))
      (libsource (lib "eagle-import") (part "C-EUC0201"))
    )
    (comp (ref "C108")
      (value "18pF")
      (footprint "eagle-import:C0201")
      (fields (field (name "MPN") "GRM0335C1E180JA01D"))
      (libsource (lib "eagle-import") (part "C-EUC0201"))
    )
    (comp (ref "C109")
      (value "0.22uF")
      (footprint "eagle-import:C0201")
      (fields (field (name "MPN") "GRM033R60J224ME15D"))
      (libsource (lib "eagle-import") (part "C-EUC0201"))
    )
    (comp (ref "C110")
      (value "4.7uF")
      (footprint "eagle-import:0402")
      (fields (field (name "MPN") "JMK105BBJ475MV-F"))
      (libsource (lib "eagle-import") (part "CAP_0402"))
    )
    (comp (ref "IC9")
      (value "MIMXRT106FDVL6B")
      (footprint "eagle-import:BGA196C65P14X14_1000X1000X143")
      (description "Processors - Application Specialized MIMXRT106FDVL6B/LFBGA196///STANDARD MARKING * TRAY")
      (fields
        (field (name "MANUFACTURER_PART_NUMBER") "MIMXRT1052DVL6B")
        (field (name "MOUSER_PART_NUMBER") "771-MIMXRT1052DVL6B")
        (field (name "MANUFACTURER_PART_NUMBER_1") "MIMXRT106FDVL6B")
        (field (name "MOUSER_PART_NUMBER_1") "771-MIMXRT106FDVL6B")
        (field (name "MOUSER_PRICE-STOCK") "https://www.mouser.co.uk/ProductDetail/NXP-Semiconductors/MIMXRT106FDVL6B")
      )
      (libsource (lib "eagle-import") (part "MIMXRT1052DVL6B"))
    )
    (comp (ref "L7")
      (value "MAKK2016T4R7M")
      (footprint "eagle-import:INDC2016X100N")
      (fields (field (name "MF") "Taiyo Yuden"))
      (libsource (lib "eagle-import") (part "MAKK2016T4R7M"))
    )
    (comp (ref "L8")
      (value "100")
      (footprint "eagle-import:0402")
      (fields (field (name "MPN") "MFBM1V1005-101-R"))
      (libsource (lib "eagle-import") (part "INDUCTOR_0402"))
    )
    (comp (ref "R64")
      (value "30K")
      (footprint "eagle-import:0402")
      (fields (field (name "MPN") "0402WGF3002TCE"))
      (libsource (lib "eagle-import") (part "RES_0402"))
    )
    (comp (ref "R65")
      (value "100K")
      (footprint "eagle-import:0402")
      (fields (field (name "MPN") "AC0402FR-07100KL"))
      (libsource (lib "eagle-import") (part "RES_0402"))
    )
    (comp (ref "R66")
      (value "10K")
      (footprint "eagle-import:0402")
      (fields (field (name "MPN") "AC0402FR-1310KL"))
      (libsource (lib "eagle-import") (part "RES_0402"))
    )
    (comp (ref "R67")
      (value "2.2M")
      (footprint "eagle-import:0402")
      (fields (field (name "MPN") "RC0402FR-072M2L"))
      (libsource (lib "eagle-import") (part "RES_0402"))
    )
    (comp (ref "R68")
      (value "10K")
      (footprint "eagle-import:0402")
      (fields (field (name "MPN") "AC0402FR-1310KL"))
      (libsource (lib "eagle-import") (part "RES_0402"))
    )
    (comp (ref "R69")
      (value "100K")
      (footprint "eagle-import:0402")
      (fields (field (name "MPN") "AC0402FR-07100KL"))
      (libsource (lib "eagle-import") (part "RES_0402"))
    )
    (comp (ref "S1")
      (value "KMS231GLFS")
      (footprint "eagle-import:KMS231GLFS")
      (fields (field (name "MOUSER_PART_NUMBER") "611-KMS231GLFS"))
      (libsource (lib "eagle-import") (part "KMS231GLFS"))
    )
    (comp (ref "Y2")
      (value "XRCGB24M000F3M00R0")
      (footprint "eagle-import:XRCGB24M000F3M00R0")
      (fields (field (name "MOUSER_PART_NUMBER") "81-XRCGB24M000F3M0R0"))
      (libsource (lib "eagle-import") (part "XRCGB24M000F3M00R0"))
    )
    (comp (ref "Y3")
      (value "SC32S-7PF20PPM")
      (footprint "eagle-import:XTAL_ABS07-32.768KHZ-7-T")
      (fields (field (name "MF") "Abracon") (field (name "MP") "ABS07-32.768KHZ-7-T"))
      (libsource (lib "eagle-import") (part "ABS07-32.768KHZ-7-T"))
    )
    (comp (ref "C12")
      (value "0.22uF")
      (footprint "eagle-import:C0201")
      (fields (field (name "MPN") "GRM033R60J224ME15D"))
      (libsource (lib "eagle-import") (part "C-EUC0201"))
    )
    (comp (ref "C13")
      (value "4.7uF")
      (footprint "eagle-import:0402")
      (fields (field (name "MPN") "JMK105BBJ475MV-F"))
      (libsource (lib "eagle-import") (part "CAP_0402"))
    )
    (comp (ref "C14")
      (value "0.22uF")
      (footprint "eagle-import:C0201")
      (fields (field (name "MPN") "GRM033R60J224ME15D"))
      (libsource (lib "eagle-import") (part "C-EUC0201"))
    )
    (comp (ref "C15")
      (value "22uF")
      (footprint "eagle-import:0805")
      (fields (field (name "MPN") "CL21A226MQQNNNE"))
      (libsource (lib "eagle-import") (part "22UF-0805-6.3V-20%"))
    )
    (comp (ref "C16")
      (value "0.22uF")
      (footprint "eagle-import:C0201")
      (fields (field (name "MPN") "GRM033R60J224ME15D"))
      (libsource (lib "eagle-import") (part "C-EUC0201"))
    )
    (comp (ref "C17")
      (value "0.22uF")
      (footprint "eagle-import:C0201")
      (fields (field (name "MPN") "GRM033R60J224ME15D"))
      (libsource (lib "eagle-import") (part "C-EUC0201"))
    )
    (comp (ref "C18")
      (value "4.7uF")
      (footprint "eagle-import:0402")
      (fields (field (name "MPN") "JMK105BBJ475MV-F"))
      (libsource (lib "eagle-import") (part "CAP_0402"))
    )
    (comp (ref "C19")
      (value "22uF")
      (footprint "eagle-import:0805")
      (fields (field (name "MPN") "CL21A226MQQNNNE"))
      (libsource (lib "eagle-import") (part "22UF-0805-6.3V-20%"))
    )
    (comp (ref "C20")
      (value "0.22uF")
      (footprint "eagle-import:C0201")
      (fields (field (name "MPN") "GRM033R60J224ME15D"))
      (libsource (lib "eagle-import") (part "C-EUC0201"))
    )
    (comp (ref "C21")
      (value "0.22uF")
      (footprint "eagle-import:C0201")
      (fields (field (name "MPN") "GRM033R60J224ME15D"))
      (libsource (lib "eagle-import") (part "C-EUC0201"))
    )
    (comp (ref "C22")
      (value "22uF")
      (footprint "eagle-import:0805")
      (fields (field (name "MPN") "CL21A226MQQNNNE"))
      (libsource (lib "eagle-import") (part "22UF-0805-6.3V-20%"))
    )
    (comp (ref "C23")
      (value "4.7uF")
      (footprint "eagle-import:0402")
      (fields (field (name "MPN") "JMK105BBJ475MV-F"))
      (libsource (lib "eagle-import") (part "CAP_0402"))
    )
    (comp (ref "C24")
      (value "0.22uF")
      (footprint "eagle-import:C0201")
      (fields (field (name "MPN") "GRM033R60J224ME15D"))
      (libsource (lib "eagle-import") (part "C-EUC0201"))
    )
    (comp (ref "IC4")
      (value "IS42S16160G-6BL")
      (footprint "eagle-import:BGA54C80P9X9_800X800X120")
      (fields (field (name "MOUSER_PART_NUMBER") "870-IS42S16160G-6BL"))
      (libsource (lib "eagle-import") (part "IS42S16160G-6BL"))
    )
    (comp (ref "R19")
      (value "100K")
      (footprint "eagle-import:0402")
      (fields (field (name "MPN") "AC0402FR-07100KL"))
      (libsource (lib "eagle-import") (part "RES_0402"))
    )
    (comp (ref "C1")
      (value "1nF")
      (footprint "eagle-import:0402")
      (fields (field (name "MPN") "VJ0402Y102JXACW1BC"))
      (libsource (lib "eagle-import") (part "CAP_0402"))
    )
    (comp (ref "FL1")
      (value "ECMF02-4CMX8")
      (footprint "eagle-import:ECMF024CMX8")
      (fields (field (name "MOUSER_PART_NUMBER") "511-ECMF02-4CMX8"))
      (libsource (lib "eagle-import") (part "ECMF02-4CMX8"))
    )
    (comp (ref "J1")
      (value "USB4105-GF-A")
      (footprint "eagle-import:GCT_USB4105-GF-A")
      (fields (field (name "MF") "GCT"))
      (libsource (lib "eagle-import") (part "USB4105-GF-A"))
    )
    (comp (ref "L1")
      (value "100")
      (footprint "eagle-import:0603")
      (fields (field (name "MPN") "MFBM1V1608-101-R"))
      (libsource (lib "eagle-import") (part "INDUCTOR-0603-33NH"))
    )
    (comp (ref "R1")
      (value "5.1K")
      (footprint "eagle-import:0402")
      (fields (field (name "MPN") "RC0402JR-075K1L"))
      (libsource (lib "eagle-import") (part "RES_0402"))
    )
    (comp (ref "R2")
      (value "5.1K")
      (footprint "eagle-import:0402")
      (fields (field (name "MPN") "RC0402JR-075K1L"))
      (libsource (lib "eagle-import") (part "RES_0402"))
    )
    (comp (ref "R3")
      (value "1M")
      (footprint "eagle-import:0402")
      (fields (field (name "MPN") "CRCW04021M00FKEDC"))
      (libsource (lib "eagle-import") (part "RES_0402"))
    )
    (comp (ref "C2")
      (value "4.7uF")
      (footprint "eagle-import:0402")
      (fields (field (name "MPN") "JMK105BBJ475MV-F"))
      (libsource (lib "eagle-import") (part "CAP_0402"))
    )
    (comp (ref "C3")
      (value "4.7uF")
      (footprint "eagle-import:0402")
      (fields (field (name "MPN") "JMK105BBJ475MV-F"))
      (libsource (lib "eagle-import") (part "CAP_0402"))
    )
    (comp (ref "C4")
      (value "4.7uF")
      (footprint "eagle-import:0402")
      (fields (field (name "MPN") "JMK105BBJ475MV-F"))
      (libsource (lib "eagle-import") (part "CAP_0402"))
    )
    (comp (ref "D1")
      (value "UHD1110-FKA-CL1A13R3Q1BBQFMF3")
      (footprint "eagle-import:LED_UHD1110-FKA-CL1A13R3Q1BBQFMF3")
      (fields (field (name "MF") "Cree Inc.") (field (name "MPN") "UHD1110-FKA-CL1A13r3q1BBQFMF3"))
      (libsource (lib "eagle-import") (part "UHD1110-FKA-CL1A13R3Q1BBQFMF3"))
    )
    (comp (ref "IC1")
      (value "LM66200DRLR")
      (footprint "eagle-import:SOTFL50P160X60-8N")
      (fields (field (name "MOUSER_PART_NUMBER") "595-LM66200DRLR"))
      (libsource (lib "eagle-import") (part "LM66200DRLR"))
    )
    (comp (ref "Q1")
      (value "DMG2301L-7")
      (footprint "eagle-import:SOT96P240X110-3N")
      (fields (field (name "MOUSER_PART_NUMBER") "621-DMG2301L-7"))
      (libsource (lib "eagle-import") (part "DMG2301L-7"))
    )
    (comp (ref "R4")
      (value "100K")
      (footprint "eagle-import:0402")
      (fields (field (name "MPN") "AC0402FR-07100KL"))
      (libsource (lib "eagle-import") (part "RES_0402"))
    )
    (comp (ref "R5")
      (value "1K")
      (footprint "eagle-import:0402")
      (fields (field (name "MPN") "CRCW04021K00FKEDC"))
      (libsource (lib "eagle-import") (part "RES_0402"))
    )
    (comp (ref "D14")
      (value "CPDQT5V0HE-HF")
      (footprint "eagle-import:CPDQT5V0HEHF")
      (libsource (lib "eagle-import") (part "CPDQT5V0HE-HF"))
    )
    (comp (ref "FL5")
      (value "EMIF06-1005M12")
      (footprint "eagle-import:SON40P150X250X65-13N")
      (fields (field (name "MOUSER_PART_NUMBER") "511-EMIF06-1005M12"))
      (libsource (lib "eagle-import") (part "EMIF06-1005M12"))
    )
    (comp (ref "J8")
      (value "3221-10-0300-00")
      (footprint "eagle-import:CNC_3221-10-0300-00")
      (fields (field (name "MF") "CNC Tech"))
      (libsource (lib "eagle-import") (part "3221-10-0300-00"))
    )
    (comp (ref "R47")
      (value "10K")
      (footprint "eagle-import:0402")
      (fields (field (name "MPN") "AC0402FR-1310KL"))
      (libsource (lib "eagle-import") (part "RES_0402"))
    )
    (comp (ref "R48")
      (value "DNP")
      (footprint "eagle-import:0402")
      (libsource (lib "eagle-import") (part "RES_0402"))
    )
    (comp (ref "R49")
      (value "DNP")
      (footprint "eagle-import:0402")
      (libsource (lib "eagle-import") (part "RES_0402"))
    )
    (comp (ref "R50")
      (value "DNP")
      (footprint "eagle-import:0402")
      (libsource (lib "eagle-import") (part "RES_0402"))
    )
    (comp (ref "R51")
      (value "DNP")
      (footprint "eagle-import:0402")
      (libsource (lib "eagle-import") (part "RES_0402"))
    )
    (comp (ref "C10")
      (value "22uF")
      (footprint "eagle-import:0805")
      (fields (field (name "MPN") "CL21A226MQQNNNE"))
      (libsource (lib "eagle-import") (part "22UF-0805-6.3V-20%"))
    )
    (comp (ref "C11")
      (value "22uF")
      (footprint "eagle-import:0805")
      (fields (field (name "MPN") "CL21A226MQQNNNE"))
      (libsource (lib "eagle-import") (part "22UF-0805-6.3V-20%"))
    )
    (comp (ref "IC3")
      (value "AP61300Z6-7")
      (footprint "eagle-import:SOTFL50P162X60-6N")
      (fields (field (name "MOUSER_PART_NUMBER") "621-AP61300Z6-7"))
      (libsource (lib "eagle-import") (part "AP61300Z6-7"))
    )
    (comp (ref "L2")
      (value "MAKK2016T1R0M")
      (footprint "eagle-import:INDC2016X100N")
      (fields (field (name "MF") "Taiyo Yuden"))
      (libsource (lib "eagle-import") (part "MAKK2016T1R0M"))
    )
    (comp (ref "Q4")
      (value "2N7002KW_R1_00001")
      (footprint "eagle-import:SOT65P210X110-3N")
      (fields (field (name "MOUSER_PART_NUMBER") "241-2N7002KWR100001"))
      (libsource (lib "eagle-import") (part "2N7002KW_R1_00001"))
    )
    (comp (ref "R16")
      (value "200K")
      (footprint "eagle-import:0402")
      (fields (field (name "MPN") "CRCW0402200KFKEDC"))
      (libsource (lib "eagle-import") (part "RES_0402"))
    )
    (comp (ref "R17")
      (value "100K")
      (footprint "eagle-import:0402")
      (fields (field (name "MPN") "AC0402FR-07100KL"))
      (libsource (lib "eagle-import") (part "RES_0402"))
    )
    (comp (ref "R18")
      (value "44.2K")
      (footprint "eagle-import:0402")
      (fields (field (name "MPN") "AC0402FR-0744K2L"))
      (libsource (lib "eagle-import") (part "RES_0402"))
    )
    (comp (ref "C34")
      (value "22uF")
      (footprint "eagle-import:0805")
      (fields (field (name "MPN") "CL21A226MQQNNNE"))
      (libsource (lib "eagle-import") (part "22UF-0805-6.3V-20%"))
    )
    (comp (ref "C35")
      (value "4.7uF")
      (footprint "eagle-import:0402")
      (fields (field (name "MPN") "JMK105BBJ475MV-F"))
      (libsource (lib "eagle-import") (part "CAP_0402"))
    )
    (comp (ref "C36")
      (value "4.7uF")
      (footprint "eagle-import:0402")
      (fields (field (name "MPN") "JMK105BBJ475MV-F"))
      (libsource (lib "eagle-import") (part "CAP_0402"))
    )
    (comp (ref "C37")
      (value "4.7uF")
      (footprint "eagle-import:0402")
      (fields (field (name "MPN") "JMK105BBJ475MV-F"))
      (libsource (lib "eagle-import") (part "CAP_0402"))
    )
    (comp (ref "C38")
      (value "4.7uF")
      (footprint "eagle-import:0402")
      (fields (field (name "MPN") "JMK105BBJ475MV-F"))
      (libsource (lib "eagle-import") (part "CAP_0402"))
    )
    (comp (ref "C39")
      (value "4.7uF")
      (footprint "eagle-import:0402")
      (fields (field (name "MPN") "JMK105BBJ475MV-F"))
      (libsource (lib "eagle-import") (part "CAP_0402"))
    )
    (comp (ref "C40")
      (value "22uF")
      (footprint "eagle-import:0805")
      (fields (field (name "MPN") "CL21A226MQQNNNE"))
      (libsource (lib "eagle-import") (part "22UF-0805-6.3V-20%"))
    )
    (comp (ref "C41")
      (value "4.7uF")
      (footprint "eagle-import:0402")
      (fields (field (name "MPN") "JMK105BBJ475MV-F"))
      (libsource (lib "eagle-import") (part "CAP_0402"))
    )
    (comp (ref "J3")
      (value "DF12-36-DS")
      (footprint "eagle-import:DF12-36-DS")
      (fields (field (name "MPN") "DF12NB(3.0)-36DS-0.5V(51)"))
      (libsource (lib "eagle-import") (part "DF12-36-DS"))
    )
    (comp (ref "L3")
      (value "100")
      (footprint "eagle-import:0402")
      (fields (field (name "MPN") "MFBM1V1005-101-R"))
      (libsource (lib "eagle-import") (part "INDUCTOR_0402"))
    )
    (comp (ref "R36")
      (value "100K")
      (footprint "eagle-import:0402")
      (fields (field (name "MPN") "AC0402FR-07100KL"))
      (libsource (lib "eagle-import") (part "RES_0402"))
    )
    (comp (ref "R37")
      (value "10K")
      (footprint "eagle-import:0402")
      (fields (field (name "MPN") "AC0402FR-1310KL"))
      (libsource (lib "eagle-import") (part "RES_0402"))
    )
    (comp (ref "R38")
      (value "10K")
      (footprint "eagle-import:0402")
      (fields (field (name "MPN") "AC0402FR-1310KL"))
      (libsource (lib "eagle-import") (part "RES_0402"))
    )
    (comp (ref "R39")
      (value "4.7K")
      (footprint "eagle-import:0402")
      (fields (field (name "MPN") "AC0402FR-074K7L"))
      (libsource (lib "eagle-import") (part "RES_0402"))
    )
    (comp (ref "R40")
      (value "4.7K")
      (footprint "eagle-import:0402")
      (fields (field (name "MPN") "AC0402FR-074K7L"))
      (libsource (lib "eagle-import") (part "RES_0402"))
    )
    (comp (ref "R41")
      (value "100K")
      (footprint "eagle-import:0402")
      (fields (field (name "MPN") "AC0402FR-07100KL"))
      (libsource (lib "eagle-import") (part "RES_0402"))
    )
    (comp (ref "R42")
      (value "1K")
      (footprint "eagle-import:0402")
      (fields (field (name "MPN") "CRCW04021K00FKEDC"))
      (libsource (lib "eagle-import") (part "RES_0402"))
    )
    (comp (ref "R43")
      (value "1K")
      (footprint "eagle-import:0402")
      (fields (field (name "MPN") "CRCW04021K00FKEDC"))
      (libsource (lib "eagle-import") (part "RES_0402"))
    )
    (comp (ref "C5")
      (value "4.7uF")
      (footprint "eagle-import:0402")
      (fields (field (name "MPN") "JMK105BBJ475MV-F"))
      (libsource (lib "eagle-import") (part "CAP_0402"))
    )
    (comp (ref "C6")
      (value "4.7uF")
      (footprint "eagle-import:0402")
      (fields (field (name "MPN") "JMK105BBJ475MV-F"))
      (libsource (lib "eagle-import") (part "CAP_0402"))
    )
    (comp (ref "C7")
      (value "4.7uF")
      (footprint "eagle-import:0402")
      (fields (field (name "MPN") "JMK105BBJ475MV-F"))
      (libsource (lib "eagle-import") (part "CAP_0402"))
    )
    (comp (ref "CN1")
      (value "S2B-PH-K-S(LF)(SN)")
      (footprint "eagle-import:JST-PH-2-THM-RA")
      (libsource (lib "eagle-import") (part "JST_2PIN-THM-RA"))
    )
    (comp (ref "D2")
      (value "CPDQT5V0HE-HF")
      (footprint "eagle-import:CPDQT5V0HEHF")
      (libsource (lib "eagle-import") (part "CPDQT5V0HE-HF"))
    )
    (comp (ref "R6")
      (value "5.1K")
      (footprint "eagle-import:0402")
      (fields (field (name "MPN") "RC0402JR-075K1L"))
      (libsource (lib "eagle-import") (part "RES_0402"))
    )
    (comp (ref "R7")
      (value "10K")
      (footprint "eagle-import:0402")
      (fields (field (name "MPN") "AC0402FR-1310KL"))
      (libsource (lib "eagle-import") (part "RES_0402"))
    )
    (comp (ref "R8")
      (value "10K")
      (footprint "eagle-import:0402")
      (fields (field (name "MPN") "AC0402FR-1310KL"))
      (libsource (lib "eagle-import") (part "RES_0402"))
    )
    (comp (ref "R9")
      (value "1.1K")
      (footprint "eagle-import:0402")
      (fields (field (name "MPN") "RC0402JR-071K1L"))
      (libsource (lib "eagle-import") (part "RES_0402"))
    )
    (comp (ref "R10")
      (value "46.4K")
      (footprint "eagle-import:0402")
      (fields (field (name "MPN") "WR04X4642FTL"))
      (libsource (lib "eagle-import") (part "RES_0402"))
    )
    (comp (ref "R11")
      (value "8.2K")
      (footprint "eagle-import:0402")
      (fields (field (name "MPN") "CR0402-FX-8201GLF"))
      (libsource (lib "eagle-import") (part "RES_0402"))
    )
    (comp (ref "R12")
      (value "100K")
      (footprint "eagle-import:0402")
      (fields (field (name "MPN") "AC0402FR-07100KL"))
      (libsource (lib "eagle-import") (part "RES_0402"))
    )
    (comp (ref "R13")
      (value "100K")
      (footprint "eagle-import:0402")
      (fields (field (name "MPN") "AC0402FR-07100KL"))
      (libsource (lib "eagle-import") (part "RES_0402"))
    )
    (comp (ref "U1")
      (value "BQ24075RGTR")
      (footprint "eagle-import:QFN50P300X300X100-17N")
      (fields (field (name "MF") "Texas Instruments"))
      (libsource (lib "eagle-import") (part "BQ24075RGTR"))
    )
  )
  (nets
    (net (code "1") (name "BT_D_WAKE") (class "Default")
      (node (ref "IC9") (pin "L5") (pinfunction "GPIO_SD_B1_00_L5") (pintype "bidirectional"))
      (node (ref "U2") (pin "39") (pinfunction "BT_DEV_WAKE_39") (pintype "bidirectional"))
    )
    (net (code "2") (name "BT_H_WAKE") (class "Default")
      (node (ref "IC9") (pin "H14") (pinfunction "GPIO_AD_B0_14_H14") (pintype "bidirectional"))
      (node (ref "R58") (pin "1") (pinfunction "1_1") (pintype "passive"))
      (node (ref "U2") (pin "38") (pinfunction "BT_HOST_WAKE_38") (pintype "bidirectional"))
    )
    (net (code "3") (name "BT_REG_ON") (class "Default")
      (node (ref "IC9") (pin "F13") (pinfunction "GPIO_AD_B0_08_F13") (pintype "bidirectional"))
      (node (ref "R47") (pin "1") (pinfunction "1_1") (pintype "passive"))
      (node (ref "U2") (pin "14") (pinfunction "BT_REG_ON_14") (pintype "input"))
    )
    (net (code "4") (name "BT_UART_CTS") (class "Default")
      (node (ref "IC9") (pin "L12") (pinfunction "GPIO_AD_B1_04_L12") (pintype "bidirectional"))
      (node (ref "U2") (pin "5") (pinfunction "~{BT_UART_RTS_N}_5") (pintype "output"))
    )
    (net (code "5") (name "BT_UART_RTS") (class "Default")
      (node (ref "IC9") (pin "K12") (pinfunction "GPIO_AD_B1_05_K12") (pintype "bidirectional"))
      (node (ref "U2") (pin "4") (pinfunction "~{BT_UART_CTS_N}_4") (pintype "input"))
    )
    (net (code "6") (name "BT_UART_RX") (class "Default")
      (node (ref "IC9") (pin "C9") (pinfunction "GPIO_B0_09_C9") (pintype "bidirectional"))
      (node (ref "U2") (pin "3") (pinfunction "BT_UART_TXD_3") (pintype "output"))
    )
    (net (code "7") (name "BT_UART_TX") (class "Default")
      (node (ref "IC9") (pin "B9") (pinfunction "GPIO_B0_08_B9") (pintype "bidirectional"))
      (node (ref "U2") (pin "2") (pinfunction "BT_UART_RXD_2") (pintype "input"))
    )
    (net (code "8") (name "CHG") (class "Default")
      (node (ref "R13") (pin "1") (pinfunction "1_1") (pintype "passive"))
      (node (ref "R51") (pin "2") (pinfunction "2_2") (pintype "passive"))
      (node (ref "R6") (pin "1") (pinfunction "1_1") (pintype "passive"))
      (node (ref "U1") (pin "9") (pinfunction "~{CHG}_9") (pintype "output"))
    )
    (net (code "9") (name "DCDC_LP") (class "Default")
      (node (ref "IC9") (pin "M1") (pinfunction "DCDC_LP_1_M1") (pintype "bidirectional"))
      (node (ref "IC9") (pin "M2") (pinfunction "DCDC_LP_2_M2") (pintype "bidirectional"))
      (node (ref "L7") (pin "2") (pinfunction "2_2") (pintype "passive"))
    )
    (net (code "10") (name "DCDC_PSWITCH") (class "Default")
      (node (ref "C96") (pin "1") (pinfunction "1_1") (pintype "passive"))
      (node (ref "IC9") (pin "K3") (pinfunction "DCDC_PSWITCH_K3") (pintype "bidirectional"))
      (node (ref "R64") (pin "1") (pinfunction "1_1") (pintype "passive"))
    )
    (net (code "11") (name "DCMI_CLK") (class "Default")
      (node (ref "IC9") (pin "B14") (pinfunction "GPIO_B1_15_B14") (pintype "bidirectional"))
      (node (ref "J3") (pin "12") (pinfunction "12_12") (pintype "bidirectional"))
    )
    (net (code "12") (name "DCMI_D0") (class "Default")
      (node (ref "IC9") (pin "J14") (pinfunction "GPIO_AD_B1_15_J14") (pintype "bidirectional"))
      (node (ref "J3") (pin "31") (pinfunction "31_31") (pintype "bidirectional"))
    )
    (net (code "13") (name "DCMI_D1") (class "Default")
      (node (ref "IC9") (pin "G12") (pinfunction "GPIO_AD_B1_14_G12") (pintype "bidirectional"))
      (node (ref "J3") (pin "29") (pinfunction "29_29") (pintype "bidirectional"))
    )
    (net (code "14") (name "DCMI_D2") (class "Default")
      (node (ref "IC9") (pin "H11") (pinfunction "GPIO_AD_B1_13_H11") (pintype "bidirectional"))
      (node (ref "J3") (pin "35") (pinfunction "35_35") (pintype "bidirectional"))
    )
    (net (code "15") (name "DCMI_D3") (class "Default")
      (node (ref "IC9") (pin "H12") (pinfunction "GPIO_AD_B1_12_H12") (pintype "bidirectional"))
      (node (ref "J3") (pin "28") (pinfunction "28_28") (pintype "bidirectional"))
    )
    (net (code "16") (name "DCMI_D4") (class "Default")
      (node (ref "IC9") (pin "J13") (pinfunction "GPIO_AD_B1_11_J13") (pintype "bidirectional"))
      (node (ref "J3") (pin "26") (pinfunction "26_26") (pintype "bidirectional"))
    )
    (net (code "17") (name "DCMI_D5") (class "Default")
      (node (ref "IC9") (pin "L13") (pinfunction "GPIO_AD_B1_10_L13") (pintype "bidirectional"))
      (node (ref "J3") (pin "33") (pinfunction "33_33") (pintype "bidirectional"))
    )
    (net (code "18") (name "DCMI_D6") (class "Default")
      (node (ref "IC9") (pin "G14") (pinfunction "GPIO_AD_B0_05_G14") (pintype "bidirectional"))
      (node (ref "J3") (pin "24") (pinfunction "24_24") (pintype "bidirectional"))
    )
    (net (code "19") (name "DCMI_D7") (class "Default")
      (node (ref "IC9") (pin "F11") (pinfunction "GPIO_AD_B0_04_F11") (pintype "bidirectional"))
      (node (ref "J3") (pin "22") (pinfunction "22_22") (pintype "bidirectional"))
      (node (ref "R46") (pin "1") (pinfunction "1_1") (pintype "passive"))
    )
    (net (code "20") (name "DCMI_FSIN") (class "Default")
      (node (ref "J3") (pin "23") (pinfunction "23_23") (pintype "bidirectional"))
      (node (ref "R42") (pin "1") (pinfunction "1_1") (pintype "passive"))
    )
    (net (code "21") (name "DCMI_HSYNC") (class "Default")
      (node (ref "IC9") (pin "L10") (pinfunction "GPIO_AD_B0_15_L10") (pintype "bidirectional"))
      (node (ref "J3") (pin "18") (pinfunction "18_18") (pintype "bidirectional"))
    )
    (net (code "22") (name "DCMI_MISO") (class "Default")
      (node (ref "IC9") (pin "E7") (pinfunction "GPIO_B0_01_E7") (pintype "bidirectional"))
      (node (ref "J3") (pin "15") (pinfunction "15_15") (pintype "bidirectional"))
    )
    (net (code "23") (name "DCMI_MOSI") (class "Default")
      (node (ref "IC9") (pin "E8") (pinfunction "GPIO_B0_02_E8") (pintype "bidirectional"))
      (node (ref "J3") (pin "17") (pinfunction "17_17") (pintype "bidirectional"))
    )
    (net (code "24") (name "DCMI_PCLK") (class "Default")
      (node (ref "IC9") (pin "D13") (pinfunction "GPIO_B1_12_D13") (pintype "bidirectional"))
      (node (ref "J3") (pin "14") (pinfunction "14_14") (pintype "bidirectional"))
    )
    (net (code "25") (name "DCMI_PWDN") (class "Default")
      (node (ref "IC9") (pin "C11") (pinfunction "GPIO_B1_02_C11") (pintype "bidirectional"))
      (node (ref "J3") (pin "25") (pinfunction "25_25") (pintype "bidirectional"))
      (node (ref "R38") (pin "1") (pinfunction "1_1") (pintype "passive"))
    )
    (net (code "26") (name "DCMI_RST") (class "Default")
      (node (ref "IC9") (pin "B11") (pinfunction "GPIO_B1_01_B11") (pintype "bidirectional"))
      (node (ref "J3") (pin "21") (pinfunction "21_21") (pintype "bidirectional"))
      (node (ref "R37") (pin "1") (pinfunction "1_1") (pintype "passive"))
    )
    (net (code "27") (name "DCMI_SCL") (class "Default")
      (node (ref "IC9") (pin "J11") (pinfunction "GPIO_AD_B1_00_J11") (pintype "bidirectional"))
      (node (ref "J3") (pin "32") (pinfunction "32_32") (pintype "bidirectional"))
      (node (ref "R39") (pin "1") (pinfunction "1_1") (pintype "passive"))
    )
    (net (code "28") (name "DCMI_SCLK") (class "Default")
      (node (ref "IC9") (pin "D8") (pinfunction "GPIO_B0_03_D8") (pintype "bidirectional"))
      (node (ref "J3") (pin "13") (pinfunction "13_13") (pintype "bidirectional"))
    )
    (net (code "29") (name "DCMI_SDA") (class "Default")
      (node (ref "IC9") (pin "K11") (pinfunction "GPIO_AD_B1_01_K11") (pintype "bidirectional"))
      (node (ref "J3") (pin "34") (pinfunction "34_34") (pintype "bidirectional"))
      (node (ref "R40") (pin "1") (pinfunction "1_1") (pintype "passive"))
    )
    (net (code "30") (name "DCMI_SSEL") (class "Default")
      (node (ref "IC9") (pin "D7") (pinfunction "GPIO_B0_00_D7") (pintype "bidirectional"))
      (node (ref "J3") (pin "11") (pinfunction "11_11") (pintype "bidirectional"))
      (node (ref "R36") (pin "1") (pinfunction "1_1") (pintype "passive"))
    )
    (net (code "31") (name "DCMI_VSYNC") (class "Default")
      (node (ref "IC9") (pin "D14") (pinfunction "GPIO_B1_13_D14") (pintype "bidirectional"))
      (node (ref "J3") (pin "16") (pinfunction "16_16") (pintype "bidirectional"))
    )
    (net (code "32") (name "ETH_INT") (class "Default")
      (node (ref "IC8") (pin "18") (pinfunction "INTRP_18") (pintype "bidirectional"))
      (node (ref "IC9") (pin "C10") (pinfunction "GPIO_B0_12_C10") (pintype "bidirectional"))
      (node (ref "R54") (pin "1") (pinfunction "1_1") (pintype "passive"))
    )
    (net (code "33") (name "ETH_MDC") (class "Default")
      (node (ref "IC8") (pin "11") (pinfunction "MDC_11") (pintype "bidirectional"))
      (node (ref "IC9") (pin "A7") (pinfunction "GPIO_EMC_40_A7") (pintype "bidirectional"))
    )
    (net (code "34") (name "ETH_MDIO") (class "Default")
      (node (ref "IC8") (pin "10") (pinfunction "MDIO_10") (pintype "bidirectional"))
      (node (ref "IC9") (pin "C7") (pinfunction "GPIO_EMC_41_C7") (pintype "bidirectional"))
      (node (ref "R56") (pin "1") (pinfunction "1_1") (pintype "passive"))
    )
    (net (code "35") (name "ETH_RST") (class "Default")
      (node (ref "C42") (pin "2") (pinfunction "2_2") (pintype "passive"))
      (node (ref "IC8") (pin "24") (pinfunction "RST#_24") (pintype "bidirectional"))
      (node (ref "IC9") (pin "D10") (pinfunction "GPIO_B0_13_D10") (pintype "bidirectional"))
      (node (ref "R52") (pin "1") (pinfunction "1_1") (pintype "passive"))
    )
    (net (code "36") (name "ETH_RXD0") (class "Default")
      (node (ref "IC8") (pin "13") (pinfunction "RXD0_13") (pintype "bidirectional"))
      (node (ref "IC9") (pin "E12") (pinfunction "GPIO_B1_04_E12") (pintype "bidirectional"))
    )
    (net (code "37") (name "ETH_RXD1") (class "Default")
      (node (ref "IC8") (pin "12") (pinfunction "RXD1_12") (pintype "bidirectional"))
      (node (ref "IC9") (pin "D12") (pinfunction "GPIO_B1_05_D12") (pintype "bidirectional"))
    )
    (net (code "38") (name "ETH_RXDV") (class "Default")
      (node (ref "IC8") (pin "15") (pinfunction "CRS_DV/_PHYAD[1:0]_15") (pintype "bidirectional"))
      (node (ref "IC9") (pin "C12") (pinfunction "GPIO_B1_06_C12") (pintype "bidirectional"))
    )
    (net (code "39") (name "ETH_RXERR") (class "Default")
      (node (ref "IC8") (pin "17") (pinfunction "RXER_17") (pintype "bidirectional"))
      (node (ref "IC9") (pin "C13") (pinfunction "GPIO_B1_11_C13") (pintype "bidirectional"))
    )
    (net (code "40") (name "ETH_TXCLK") (class "Default")
      (node (ref "IC8") (pin "8") (pinfunction "XI_8") (pintype "bidirectional"))
      (node (ref "IC9") (pin "B13") (pinfunction "GPIO_B1_10_B13") (pintype "bidirectional"))
    )
    (net (code "41") (name "ETH_TXD0") (class "Default")
      (node (ref "IC8") (pin "20") (pinfunction "TXD0_20") (pintype "bidirectional"))
      (node (ref "IC9") (pin "B12") (pinfunction "GPIO_B1_07_B12") (pintype "bidirectional"))
    )
    (net (code "42") (name "ETH_TXD1") (class "Default")
      (node (ref "IC8") (pin "21") (pinfunction "TXD1_21") (pintype "bidirectional"))
      (node (ref "IC9") (pin "A12") (pinfunction "GPIO_B1_08_A12") (pintype "bidirectional"))
    )
    (net (code "43") (name "ETH_TXEN") (class "Default")
      (node (ref "IC8") (pin "19") (pinfunction "TXEN_19") (pintype "bidirectional"))
      (node (ref "IC9") (pin "A13") (pinfunction "GPIO_B1_09_A13") (pintype "bidirectional"))
    )
    (net (code "44") (name "GND") (class "Default")
      (node (ref "C1") (pin "1") (pinfunction "1_1") (pintype "passive"))
      (node (ref "C10") (pin "2") (pinfunction "2_2") (pintype "passive"))
      (node (ref "C100") (pin "1") (pinfunction "1_1") (pintype "passive"))
      (node (ref "C101") (pin "1") (pinfunction "1_1") (pintype "passive"))
      (node (ref "C102") (pin "2") (pinfunction "2_2") (pintype "passive"))
      (node (ref "C103") (pin "1") (pinfunction "1_1") (pintype "passive"))
      (node (ref "C104") (pin "2") (pinfunction "2_2") (pintype "passive"))
      (node (ref "C105") (pin "2") (pinfunction "2_2") (pintype "passive"))
      (node (ref "C106") (pin "2") (pinfunction "2_2") (pintype "passive"))
      (node (ref "C107") (pin "2") (pinfunction "2_2") (pintype "passive"))
      (node (ref "C108") (pin "2") (pinfunction "2_2") (pintype "passive"))
      (node (ref "C109") (pin "2") (pinfunction "2_2") (pintype "passive"))
      (node (ref "C11") (pin "2") (pinfunction "2_2") (pintype "passive"))
      (node (ref "C110") (pin "1") (pinfunction "1_1") (pintype "passive"))
      (node (ref "C111") (pin "2") (pinfunction "2_2") (pintype "passive"))
      (node (ref "C112") (pin "1") (pinfunction "1_1") (pintype "passive"))
      (node (ref "C113") (pin "1") (pinfunction "1_1") (pintype "passive"))
      (node (ref "C12") (pin "1") (pinfunction "1_1") (pintype "passive"))
      (node (ref "C13") (pin "2") (pinfunction "2_2") (pintype "passive"))
      (node (ref "C14") (pin "2") (pinfunction "2_2") (pintype "passive"))
      (node (ref "C15") (pin "2") (pinfunction "2_2") (pintype "passive"))
      (node (ref "C16") (pin "2") (pinfunction "2_2") (pintype "passive"))
      (node (ref "C17") (pin "2") (pinfunction "2_2") (pintype "passive"))
      (node (ref "C18") (pin "1") (pinfunction "1_1") (pintype "passive"))
      (node (ref "C19") (pin "1") (pinfunction "1_1") (pintype "passive"))
      (node (ref "C2") (pin "1") (pinfunction "1_1") (pintype "passive"))
      (node (ref "C20") (pin "2") (pinfunction "2_2") (pintype "passive"))
      (node (ref "C21") (pin "2") (pinfunction "2_2") (pintype "passive"))
      (node (ref "C22") (pin "2") (pinfunction "2_2") (pintype "passive"))
      (node (ref "C23") (pin "2") (pinfunction "2_2") (pintype "passive"))
      (node (ref "C24") (pin "1") (pinfunction "1_1") (pintype "passive"))
      (node (ref "C25") (pin "1") (pinfunction "1_1") (pintype "passive"))
      (node (ref "C26") (pin "2") (pinfunction "2_2") (pintype "passive"))
      (node (ref "C27") (pin "1") (pinfunction "1_1") (pintype "passive"))
      (node (ref "C28") (pin "1") (pinfunction "1_1") (pintype "passive"))
      (node (ref "C29") (pin "2") (pinfunction "2_2") (pintype "passive"))
      (node (ref "C3") (pin "1") (pinfunction "1_1") (pintype "passive"))
      (node (ref "C30") (pin "2") (pinfunction "2_2") (pintype "passive"))
      (node (ref "C31") (pin "1") (pinfunction "1_1") (pintype "passive"))
      (node (ref "C32") (pin "2") (pinfunction "2_2") (pintype "passive"))
      (node (ref "C33") (pin "2") (pinfunction "2_2") (pintype "passive"))
      (node (ref "C34") (pin "2") (pinfunction "2_2") (pintype "passive"))
      (node (ref "C35") (pin "1") (pinfunction "1_1") (pintype "passive"))
      (node (ref "C36") (pin "1") (pinfunction "1_1") (pintype "passive"))
      (node (ref "C37") (pin "1") (pinfunction "1_1") (pintype "passive"))
      (node (ref "C38") (pin "1") (pinfunction "1_1") (pintype "passive"))
      (node (ref "C39") (pin "1") (pinfunction "1_1") (pintype "passive"))
      (node (ref "C4") (pin "1") (pinfunction "1_1") (pintype "passive"))
      (node (ref "C40") (pin "2") (pinfunction "2_2") (pintype "passive"))
      (node (ref "C41") (pin "1") (pinfunction "1_1") (pintype "passive"))
      (node (ref "C42") (pin "1") (pinfunction "1_1") (pintype "passive"))
      (node (ref "C43") (pin "1") (pinfunction "1_1") (pintype "passive"))
      (node (ref "C44") (pin "1") (pinfunction "1_1") (pintype "passive"))
      (node (ref "C45") (pin "2") (pinfunction "2_2") (pintype "passive"))
      (node (ref "C46") (pin "2") (pinfunction "2_2") (pintype "passive"))
      (node (ref "C47") (pin "2") (pinfunction "2_2") (pintype "passive"))
      (node (ref "C48") (pin "1") (pinfunction "1_1") (pintype "passive"))
      (node (ref "C49") (pin "2") (pinfunction "2_2") (pintype "passive"))
      (node (ref "C5") (pin "1") (pinfunction "1_1") (pintype "passive"))
      (node (ref "C50") (pin "2") (pinfunction "2_2") (pintype "passive"))
      (node (ref "C51") (pin "2") (pinfunction "2_2") (pintype "passive"))
      (node (ref "C52") (pin "2") (pinfunction "2_2") (pintype "bidirectional"))
      (node (ref "C53") (pin "2") (pinfunction "2_2") (pintype "bidirectional"))
      (node (ref "C54") (pin "2") (pinfunction "2_2") (pintype "passive"))
      (node (ref "C55") (pin "2") (pinfunction "2_2") (pintype "passive"))
      (node (ref "C56") (pin "2") (pinfunction "2_2") (pintype "passive"))
      (node (ref "C57") (pin "1") (pinfunction "1_1") (pintype "passive"))
      (node (ref "C58") (pin "1") (pinfunction "1_1") (pintype "passive"))
      (node (ref "C59") (pin "1") (pinfunction "1_1") (pintype "passive"))
      (node (ref "C6") (pin "1") (pinfunction "1_1") (pintype "passive"))
      (node (ref "C60") (pin "2") (pinfunction "2_2") (pintype "passive"))
      (node (ref "C61") (pin "2") (pinfunction "2_2") (pintype "passive"))
      (node (ref "C62") (pin "1") (pinfunction "1_1") (pintype "passive"))
      (node (ref "C63") (pin "2") (pinfunction "2_2") (pintype "passive"))
      (node (ref "C64") (pin "2") (pinfunction "2_2") (pintype "passive"))
      (node (ref "C65") (pin "1") (pinfunction "1_1") (pintype "passive"))
      (node (ref "C66") (pin "1") (pinfunction "1_1") (pintype "passive"))
      (node (ref "C67") (pin "2") (pinfunction "2_2") (pintype "passive"))
      (node (ref "C68") (pin "2") (pinfunction "2_2") (pintype "passive"))
      (node (ref "C69") (pin "2") (pinfunction "2_2") (pintype "passive"))
      (node (ref "C7") (pin "1") (pinfunction "1_1") (pintype "passive"))
      (node (ref "C70") (pin "2") (pinfunction "2_2") (pintype "passive"))
      (node (ref "C71") (pin "2") (pinfunction "2_2") (pintype "passive"))
      (node (ref "C72") (pin "1") (pinfunction "1_1") (pintype "passive"))
      (node (ref "C73") (pin "2") (pinfunction "2_2") (pintype "passive"))
      (node (ref "C74") (pin "1") (pinfunction "1_1") (pintype "passive"))
      (node (ref "C75") (pin "2") (pinfunction "2_2") (pintype "passive"))
      (node (ref "C76") (pin "2") (pinfunction "2_2") (pintype "passive"))
      (node (ref "C77") (pin "1") (pinfunction "1_1") (pintype "passive"))
      (node (ref "C78") (pin "1") (pinfunction "1_1") (pintype "passive"))
      (node (ref "C79") (pin "1") (pinfunction "1_1") (pintype "passive"))
      (node (ref "C8") (pin "1") (pinfunction "1_1") (pintype "passive"))
      (node (ref "C80") (pin "2") (pinfunction "2_2") (pintype "passive"))
      (node (ref "C81") (pin "1") (pinfunction "1_1") (pintype "passive"))
      (node (ref "C82") (pin "2") (pinfunction "2_2") (pintype "passive"))
      (node (ref "C83") (pin "1") (pinfunction "1_1") (pintype "passive"))
      (node (ref "C84") (pin "2") (pinfunction "2_2") (pintype "passive"))
      (node (ref "C85") (pin "1") (pinfunction "1_1") (pintype "passive"))
      (node (ref "C86") (pin "2") (pinfunction "2_2") (pintype "passive"))
      (node (ref "C87") (pin "2") (pinfunction "2_2") (pintype "passive"))
      (node (ref "C88") (pin "1") (pinfunction "1_1") (pintype "passive"))
      (node (ref "C89") (pin "1") (pinfunction "1_1") (pintype "passive"))
      (node (ref "C9") (pin "1") (pinfunction "1_1") (pintype "passive"))
      (node (ref "C90") (pin "2") (pinfunction "2_2") (pintype "passive"))
      (node (ref "C91") (pin "1") (pinfunction "1_1") (pintype "passive"))
      (node (ref "C92") (pin "1") (pinfunction "1_1") (pintype "passive"))
      (node (ref "C93") (pin "1") (pinfunction "1_1") (pintype "passive"))
      (node (ref "C94") (pin "1") (pinfunction "1_1") (pintype "passive"))
      (node (ref "C95") (pin "1") (pinfunction "1_1") (pintype "passive"))
      (node (ref "C96") (pin "2") (pinfunction "2_2") (pintype "passive"))
      (node (ref "C97") (pin "1") (pinfunction "1_1") (pintype "passive"))
      (node (ref "C98") (pin "1") (pinfunction "1_1") (pintype "passive"))
      (node (ref "C99") (pin "2") (pinfunction "2_2") (pintype "passive"))
      (node (ref "CN1") (pin "2") (pinfunction "1_2") (pintype "passive"))
      (node (ref "D10") (pin "2") (pinfunction "2_2") (pintype "bidirectional"))
      (node (ref "D11") (pin "2") (pinfunction "2_2") (pintype "bidirectional"))
      (node (ref "D12") (pin "2") (pinfunction "2_2") (pintype "bidirectional"))
      (node (ref "D13") (pin "2") (pinfunction "2_2") (pintype "bidirectional"))
      (node (ref "D14") (pin "2") (pinfunction "2_2") (pintype "bidirectional"))
      (node (ref "D2") (pin "2") (pinfunction "2_2") (pintype "bidirectional"))
      (node (ref "D6") (pin "2") (pinfunction "2_2") (pintype "bidirectional"))
      (node (ref "D7") (pin "2") (pinfunction "2_2") (pintype "bidirectional"))
      (node (ref "D8") (pin "2") (pinfunction "2_2") (pintype "bidirectional"))
      (node (ref "D9") (pin "2") (pinfunction "2_2") (pintype "bidirectional"))
      (node (ref "FL1") (pin "5") (pinfunction "GND_1_5") (pintype "bidirectional"))
      (node (ref "FL1") (pin "8") (pinfunction "GND_2_8") (pintype "bidirectional"))
      (node (ref "FL2") (pin "13") (pinfunction "EP_13") (pintype "bidirectional"))
      (node (ref "FL3") (pin "13") (pinfunction "EP_13") (pintype "bidirectional"))
      (node (ref "FL4") (pin "13") (pinfunction "EP_13") (pintype "bidirectional"))
      (node (ref "FL5") (pin "13") (pinfunction "EP_13") (pintype "bidirectional"))
      (node (ref "IC1") (pin "1") (pinfunction "GND_1_1") (pintype "bidirectional"))
      (node (ref "IC1") (pin "4") (pinfunction "~{ON}_4") (pintype "bidirectional"))
      (node (ref "IC1") (pin "5") (pinfunction "GND_2_5") (pintype "bidirectional"))
      (node (ref "IC2") (pin "2") (pinfunction "GND_2") (pintype "bidirectional"))
      (node (ref "IC3") (pin "2") (pinfunction "GND_2") (pintype "bidirectional"))
      (node (ref "IC4") (pin "A1") (pinfunction "VSS_1_A1") (pintype "bidirectional"))
      (node (ref "IC4") (pin "A3") (pinfunction "VSSQ_1_A3") (pintype "bidirectional"))
      (node (ref "IC4") (pin "B7") (pinfunction "VSSQ_2_B7") (pintype "bidirectional"))
      (node (ref "IC4") (pin "C3") (pinfunction "VSSQ_3_C3") (pintype "bidirectional"))
      (node (ref "IC4") (pin "D7") (pinfunction "VSSQ_4_D7") (pintype "bidirectional"))
      (node (ref "IC4") (pin "E3") (pinfunction "VSS_2_E3") (pintype "bidirectional"))
      (node (ref "IC4") (pin "J1") (pinfunction "VSS_3_J1") (pintype "bidirectional"))
      (node (ref "IC5") (pin "4") (pinfunction "GND_4") (pintype "bidirectional"))
      (node (ref "IC5") (pin "9") (pinfunction "EP_9") (pintype "bidirectional"))
      (node (ref "IC6") (pin "19") (pinfunction "VSS_19") (pintype "power_in"))
      (node (ref "IC6") (pin "21") (pinfunction "EP_21") (pintype "bidirectional"))
      (node (ref "IC7") (pin "3") (pinfunction "GND_3") (pintype "bidirectional"))
      (node (ref "IC8") (pin "22") (pinfunction "GND_1_22") (pintype "bidirectional"))
      (node (ref "IC8") (pin "25") (pinfunction "GND_2_25") (pintype "bidirectional"))
      (node (ref "IC9") (pin "A1") (pinfunction "VSS_1_A1") (pintype "bidirectional"))
      (node (ref "IC9") (pin "A14") (pinfunction "VSS_2_A14") (pintype "bidirectional"))
      (node (ref "IC9") (pin "B10") (pinfunction "VSS_4_B10") (pintype "bidirectional"))
      (node (ref "IC9") (pin "B5") (pinfunction "VSS_3_B5") (pintype "bidirectional"))
      (node (ref "IC9") (pin "E13") (pinfunction "VSS_6_E13") (pintype "bidirectional"))
      (node (ref "IC9") (pin "E2") (pinfunction "VSS_5_E2") (pintype "bidirectional"))
      (node (ref "IC9") (pin "G7") (pinfunction "VSS_7_G7") (pintype "bidirectional"))
      (node (ref "IC9") (pin "G8") (pinfunction "VSS_8_G8") (pintype "bidirectional"))
      (node (ref "IC9") (pin "H7") (pinfunction "VSS_9_H7") (pintype "bidirectional"))
      (node (ref "IC9") (pin "H8") (pinfunction "VSS_10_H8") (pintype "bidirectional"))
      (node (ref "IC9") (pin "J7") (pinfunction "VSS_11_J7") (pintype "bidirectional"))
      (node (ref "IC9") (pin "J8") (pinfunction "VSS_12_J8") (pintype "bidirectional"))
      (node (ref "IC9") (pin "K13") (pinfunction "VSS_14_K13") (pintype "bidirectional"))
      (node (ref "IC9") (pin "K2") (pinfunction "VSS_13_K2") (pintype "bidirectional"))
      (node (ref "IC9") (pin "K6") (pinfunction "TEST_MODE_K6") (pintype "bidirectional"))
      (node (ref "IC9") (pin "K9") (pinfunction "NGND_KEL0_K9") (pintype "bidirectional"))
      (node (ref "IC9") (pin "L9") (pinfunction "VSS_15_L9") (pintype "bidirectional"))
      (node (ref "IC9") (pin "N1") (pinfunction "DCDC_GND_1_N1") (pintype "bidirectional"))
      (node (ref "IC9") (pin "N2") (pinfunction "DCDC_GND_2_N2") (pintype "bidirectional"))
      (node (ref "IC9") (pin "N5") (pinfunction "VSS_16_N5") (pintype "bidirectional"))
      (node (ref "IC9") (pin "N8") (pinfunction "VSS_17_N8") (pintype "bidirectional"))
      (node (ref "IC9") (pin "P1") (pinfunction "VSS_18_P1") (pintype "bidirectional"))
      (node (ref "IC9") (pin "P14") (pinfunction "VSS_19_P14") (pintype "bidirectional"))
      (node (ref "J1") (pin "A1_B12") (pinfunction "GND_A1_B12") (pintype "power_in"))
      (node (ref "J1") (pin "B1_A12") (pinfunction "GND_B1_A12") (pintype "power_in"))
      (node (ref "J2") (pin "CD$2") (pinfunction "CD_POL_CD$2") (pintype "power_in"))
      (node (ref "J2") (pin "G$1") (pinfunction "SHD_G$1") (pintype "power_in"))
      (node (ref "J2") (pin "G$2") (pinfunction "SHD_G$2") (pintype "power_in"))
      (node (ref "J2") (pin "G$3") (pinfunction "SHD_G$3") (pintype "power_in"))
      (node (ref "J2") (pin "G$4") (pinfunction "SHD_G$4") (pintype "power_in"))
      (node (ref "J2") (pin "P$6") (pinfunction "VSS_P$6") (pintype "power_in"))
      (node (ref "J3") (pin "19") (pinfunction "19_19") (pintype "bidirectional"))
      (node (ref "J3") (pin "27") (pinfunction "27_27") (pintype "bidirectional"))
      (node (ref "J3") (pin "5") (pinfunction "5_5") (pintype "bidirectional"))
      (node (ref "J5") (pin "1") (pinfunction "1_1") (pintype "passive"))
      (node (ref "J7") (pin "1") (pinfunction "1_1") (pintype "passive"))
      (node (ref "J8") (pin "3") (pinfunction "3_3") (pintype "passive"))
      (node (ref "J8") (pin "5") (pinfunction "5_5") (pintype "passive"))
      (node (ref "J9") (pin "2") (pinfunction "GND_1_2") (pintype "bidirectional"))
      (node (ref "J9") (pin "3") (pinfunction "GND_2_3") (pintype "bidirectional"))
      (node (ref "Q1") (pin "1") (pinfunction "G_1") (pintype "bidirectional"))
      (node (ref "R1") (pin "2") (pinfunction "2_2") (pintype "passive"))
      (node (ref "R10") (pin "2") (pinfunction "2_2") (pintype "passive"))
      (node (ref "R11") (pin "2") (pinfunction "2_2") (pintype "passive"))
      (node (ref "R18") (pin "1") (pinfunction "1_1") (pintype "passive"))
      (node (ref "R2") (pin "2") (pinfunction "2_2") (pintype "passive"))
      (node (ref "R3") (pin "2") (pinfunction "2_2") (pintype "passive"))
      (node (ref "R37") (pin "2") (pinfunction "2_2") (pintype "passive"))
      (node (ref "R47") (pin "2") (pinfunction "2_2") (pintype "passive"))
      (node (ref "R55") (pin "2") (pinfunction "2_2") (pintype "passive"))
      (node (ref "R67") (pin "2") (pinfunction "2_2") (pintype "passive"))
      (node (ref "R8") (pin "2") (pinfunction "2_2") (pintype "passive"))
      (node (ref "R9") (pin "2") (pinfunction "2_2") (pintype "passive"))
      (node (ref "S1") (pin "1") (pinfunction "NO_1_1") (pintype "bidirectional"))
      (node (ref "S1") (pin "5") (pinfunction "NO_2_5") (pintype "bidirectional"))
      (node (ref "S2") (pin "1") (pinfunction "NO_1_1") (pintype "bidirectional"))
      (node (ref "S2") (pin "5") (pinfunction "NO_2_5") (pintype "bidirectional"))
      (node (ref "TP2") (pin "TP") (pinfunction "TP_TP") (pintype "input"))
      (node (ref "U1") (pin "15") (pinfunction "SYSOFF_15") (pintype "input"))
      (node (ref "U1") (pin "17") (pinfunction "EXP_17") (pintype "power_in"))
      (node (ref "U1") (pin "4") (pinfunction "~{CE}_4") (pintype "input"))
      (node (ref "U1") (pin "6") (pinfunction "EN1_6") (pintype "input"))
      (node (ref "U1") (pin "8") (pinfunction "VSS_8") (pintype "power_in"))
      (node (ref "U2") (pin "1") (pinfunction "GND_1") (pintype "power_in"))
      (node (ref "U2") (pin "12") (pinfunction "GND_12") (pintype "power_in"))
      (node (ref "U2") (pin "19") (pinfunction "GND_19") (pintype "power_in"))
      (node (ref "U2") (pin "21") (pinfunction "GND_21") (pintype "power_in"))
      (node (ref "U2") (pin "29") (pinfunction "GND_29") (pintype "power_in"))
      (node (ref "U2") (pin "32") (pinfunction "GND_(SR_PVSS)_32") (pintype "power_in"))
      (node (ref "U2") (pin "33") (pinfunction "GND_(SR_PVSS)_33") (pintype "power_in"))
      (node (ref "U2") (pin "35") (pinfunction "GND_35") (pintype "power_in"))
      (node (ref "U2") (pin "40") (pinfunction "GND_40") (pintype "power_in"))
      (node (ref "U2") (pin "42") (pinfunction "GND_42") (pintype "power_in"))
      (node (ref "U2") (pin "43") (pinfunction "GND_43") (pintype "power_in"))
      (node (ref "U2") (pin "44") (pinfunction "GND_44") (pintype "power_in"))
      (node (ref "U2") (pin "45") (pinfunction "GND_45") (pintype "power_in"))
      (node (ref "U2") (pin "46") (pinfunction "GND_46") (pintype "power_in"))
      (node (ref "Y1") (pin "2") (pinfunction "GND_2") (pintype "bidirectional"))
      (node (ref "Y2") (pin "2") (pinfunction "NC_1_2") (pintype "bidirectional"))
      (node (ref "Y2") (pin "4") (pinfunction "NC_2_4") (pintype "bidirectional"))
    )
    (net (code "45") (name "INT_I2C_INT") (class "Default")
      (node (ref "IC7") (pin "4") (pinfunction "INT_4") (pintype "bidirectional"))
      (node (ref "IC9") (pin "D11") (pinfunction "GPIO_B1_03_D11") (pintype "bidirectional"))
      (node (ref "R29") (pin "1") (pinfunction "1_1") (pintype "passive"))
    )
    (net (code "46") (name "INT_I2C_SCL") (class "Default")
      (node (ref "IC6") (pin "10") (pinfunction "I2C_SCL_10") (pintype "input"))
      (node (ref "IC7") (pin "1") (pinfunction "SCL_1") (pintype "bidirectional"))
      (node (ref "IC9") (pin "C8") (pinfunction "GPIO_B0_04_C8") (pintype "bidirectional"))
      (node (ref "R27") (pin "1") (pinfunction "1_1") (pintype "passive"))
    )
    (net (code "47") (name "INT_I2C_SDA") (class "Default")
      (node (ref "IC6") (pin "9") (pinfunction "I2C_SDA_9") (pintype "bidirectional"))
      (node (ref "IC7") (pin "5") (pinfunction "SDA_5") (pintype "bidirectional"))
      (node (ref "IC9") (pin "B8") (pinfunction "GPIO_B0_05_B8") (pintype "bidirectional"))
      (node (ref "R28") (pin "1") (pinfunction "1_1") (pintype "passive"))
    )
    (net (code "48") (name "JTAG_TCK") (class "Default")
      (node (ref "FL5") (pin "5") (pinfunction "INPUT_5_5") (pintype "bidirectional"))
      (node (ref "IC9") (pin "F12") (pinfunction "GPIO_AD_B0_07_F12") (pintype "bidirectional"))
    )
    (net (code "49") (name "JTAG_TCK_INT") (class "Default")
      (node (ref "FL5") (pin "8") (pinfunction "OUTPUT_5_8") (pintype "bidirectional"))
      (node (ref "J8") (pin "4") (pinfunction "4_4") (pintype "passive"))
    )
    (net (code "50") (name "JTAG_TDI") (class "Default")
      (node (ref "FL5") (pin "3") (pinfunction "INPUT_3_3") (pintype "bidirectional"))
      (node (ref "IC9") (pin "F14") (pinfunction "GPIO_AD_B0_09_F14") (pintype "bidirectional"))
      (node (ref "R50") (pin "1") (pinfunction "1_1") (pintype "passive"))
    )
    (net (code "51") (name "JTAG_TDI_INT") (class "Default")
      (node (ref "FL5") (pin "10") (pinfunction "OUTPUT_3_10") (pintype "bidirectional"))
      (node (ref "R44") (pin "1") (pinfunction "1_1") (pintype "passive"))
      (node (ref "R48") (pin "1") (pinfunction "1_1") (pintype "passive"))
    )
    (net (code "52") (name "JTAG_TDO") (class "Default")
      (node (ref "FL5") (pin "4") (pinfunction "INPUT_4_4") (pintype "bidirectional"))
      (node (ref "IC9") (pin "G13") (pinfunction "GPIO_AD_B0_10_G13") (pintype "bidirectional"))
    )
    (net (code "53") (name "JTAG_TDO_INT") (class "Default")
      (node (ref "FL5") (pin "9") (pinfunction "OUTPUT_4_9") (pintype "bidirectional"))
      (node (ref "J8") (pin "6") (pinfunction "6_6") (pintype "passive"))
    )
    (net (code "54") (name "JTAG_TMS") (class "Default")
      (node (ref "FL5") (pin "6") (pinfunction "INPUT_6_6") (pintype "bidirectional"))
      (node (ref "IC9") (pin "E14") (pinfunction "GPIO_AD_B0_06_E14") (pintype "bidirectional"))
    )
    (net (code "55") (name "JTAG_TMS_INT") (class "Default")
      (node (ref "FL5") (pin "7") (pinfunction "OUTPUT_6_7") (pintype "bidirectional"))
      (node (ref "J8") (pin "2") (pinfunction "2_2") (pintype "passive"))
    )
    (net (code "56") (name "JTAG_TRSTB") (class "Default")
      (node (ref "FL5") (pin "1") (pinfunction "INPUT_1_1") (pintype "bidirectional"))
      (node (ref "IC9") (pin "G10") (pinfunction "GPIO_AD_B0_11_G10") (pintype "bidirectional"))
      (node (ref "R51") (pin "1") (pinfunction "1_1") (pintype "passive"))
    )
    (net (code "57") (name "JTAG_TRSTB_INT") (class "Default")
      (node (ref "FL5") (pin "12") (pinfunction "OUTPUT_1_12") (pintype "bidirectional"))
      (node (ref "R45") (pin "1") (pinfunction "1_1") (pintype "passive"))
      (node (ref "R49") (pin "1") (pinfunction "1_1") (pintype "passive"))
    )
    (net (code "58") (name "LED_B") (class "Default")
      (node (ref "IC9") (pin "C14") (pinfunction "GPIO_B1_14_C14") (pintype "bidirectional"))
      (node (ref "R21") (pin "1") (pinfunction "1_1") (pintype "passive"))
      (node (ref "R24") (pin "1") (pinfunction "1_1") (pintype "passive"))
    )
    (net (code "59") (name "LED_CHG") (class "Default")
      (node (ref "D1") (pin "3") (pinfunction "RED_3") (pintype "passive"))
      (node (ref "R6") (pin "2") (pinfunction "2_2") (pintype "passive"))
    )
    (net (code "60") (name "LED_G") (class "Default")
      (node (ref "IC9") (pin "A10") (pinfunction "GPIO_B0_11_A10") (pintype "bidirectional"))
      (node (ref "R22") (pin "1") (pinfunction "1_1") (pintype "passive"))
      (node (ref "R25") (pin "1") (pinfunction "1_1") (pintype "passive"))
    )
    (net (code "61") (name "LED_PGOOD") (class "Default")
      (node (ref "D1") (pin "2") (pinfunction "GREEN_2") (pintype "passive"))
      (node (ref "R7") (pin "2") (pinfunction "2_2") (pintype "passive"))
    )
    (net (code "62") (name "LED_R") (class "Default")
      (node (ref "IC9") (pin "D9") (pinfunction "GPIO_B0_10_D9") (pintype "bidirectional"))
      (node (ref "R23") (pin "1") (pinfunction "1_1") (pintype "passive"))
      (node (ref "R26") (pin "1") (pinfunction "1_1") (pintype "passive"))
    )
    (net (code "63") (name "MDI_LED") (class "Default")
      (node (ref "J5") (pin "8") (pinfunction "8_8") (pintype "passive"))
      (node (ref "R53") (pin "2") (pinfunction "2_2") (pintype "passive"))
    )
    (net (code "64") (name "MDI_RX_N") (class "Default")
      (node (ref "IC8") (pin "3") (pinfunction "RXM_3") (pintype "bidirectional"))
      (node (ref "J5") (pin "7") (pinfunction "7_7") (pintype "passive"))
    )
    (net (code "65") (name "MDI_RX_P") (class "Default")
      (node (ref "IC8") (pin "4") (pinfunction "RXP_4") (pintype "bidirectional"))
      (node (ref "J5") (pin "6") (pinfunction "6_6") (pintype "passive"))
    )
    (net (code "66") (name "MDI_TX_N") (class "Default")
      (node (ref "IC8") (pin "5") (pinfunction "TXM_5") (pintype "bidirectional"))
      (node (ref "J5") (pin "5") (pinfunction "5_5") (pintype "passive"))
    )
    (net (code "67") (name "MDI_TX_P") (class "Default")
      (node (ref "IC8") (pin "6") (pinfunction "TXP_6") (pintype "bidirectional"))
      (node (ref "J5") (pin "4") (pinfunction "4_4") (pintype "passive"))
    )
    (net (code "68") (name "NVCC_PLL") (class "Default")
      (node (ref "C101") (pin "2") (pinfunction "2_2") (pintype "passive"))
      (node (ref "C102") (pin "1") (pinfunction "1_1") (pintype "passive"))
      (node (ref "IC9") (pin "P10") (pinfunction "NVCC_PLL_P10") (pintype "bidirectional"))
    )
    (net (code "69") (name "Net-(ANT1-FEED)") (class "Default")
      (node (ref "ANT1") (pin "1") (pinfunction "FEED_1") (pintype "input"))
      (node (ref "C53") (pin "1") (pinfunction "1_1") (pintype "bidirectional"))
      (node (ref "L5") (pin "1") (pinfunction "1_1") (pintype "passive"))
    )
    (net (code "70") (name "Net-(C1-Pad2)") (class "Default")
      (node (ref "C1") (pin "2") (pinfunction "2_2") (pintype "passive"))
      (node (ref "J1") (pin "S1") (pinfunction "SHELL_GND_S1") (pintype "power_in"))
      (node (ref "J1") (pin "S2") (pinfunction "SHELL_GND_S2") (pintype "power_in"))
      (node (ref "J1") (pin "S3") (pinfunction "SHELL_GND_S3") (pintype "power_in"))
      (node (ref "J1") (pin "S4") (pinfunction "SHELL_GND_S4") (pintype "power_in"))
      (node (ref "R3") (pin "1") (pinfunction "1_1") (pintype "passive"))
    )
    (net (code "71") (name "Net-(C110-Pad2)") (class "Default")
      (node (ref "C110") (pin "2") (pinfunction "2_2") (pintype "passive"))
      (node (ref "R68") (pin "1") (pinfunction "1_1") (pintype "passive"))
      (node (ref "R69") (pin "2") (pinfunction "2_2") (pintype "passive"))
    )
    (net (code "72") (name "Net-(CN1-2)") (class "Default")
      (node (ref "C5") (pin "2") (pinfunction "2_2") (pintype "passive"))
      (node (ref "CN1") (pin "1") (pinfunction "2_1") (pintype "passive"))
      (node (ref "D2") (pin "1") (pinfunction "1_1") (pintype "bidirectional"))
      (node (ref "U1") (pin "2") (pinfunction "BAT_2_2") (pintype "bidirectional"))
      (node (ref "U1") (pin "3") (pinfunction "BAT_3_3") (pintype "bidirectional"))
    )
    (net (code "73") (name "Net-(D1-BLUE)") (class "Default")
      (node (ref "D1") (pin "1") (pinfunction "BLUE_1") (pintype "passive"))
      (node (ref "R5") (pin "2") (pinfunction "2_2") (pintype "passive"))
    )
    (net (code "74") (name "Net-(D5-BLUE)") (class "Default")
      (node (ref "D5") (pin "1") (pinfunction "BLUE_1") (pintype "passive"))
      (node (ref "R21") (pin "2") (pinfunction "2_2") (pintype "passive"))
    )
    (net (code "75") (name "Net-(D5-GREEN)") (class "Default")
      (node (ref "D5") (pin "2") (pinfunction "GREEN_2") (pintype "passive"))
      (node (ref "R22") (pin "2") (pinfunction "2_2") (pintype "passive"))
    )
    (net (code "76") (name "Net-(D5-RED)") (class "Default")
      (node (ref "D5") (pin "3") (pinfunction "RED_3") (pintype "passive"))
      (node (ref "R23") (pin "2") (pinfunction "2_2") (pintype "passive"))
    )
    (net (code "77") (name "Net-(D13-Pad1)") (class "Default")
      (node (ref "D13") (pin "1") (pinfunction "1_1") (pintype "bidirectional"))
      (node (ref "J6") (pin "2") (pinfunction "2_2") (pintype "passive"))
      (node (ref "R46") (pin "2") (pinfunction "2_2") (pintype "passive"))
    )
    (net (code "78") (name "Net-(D15-A2)") (class "Default")
      (node (ref "D15") (pin "2") (pinfunction "A2_2") (pintype "bidirectional"))
      (node (ref "TP1") (pin "TP") (pinfunction "TP_TP") (pintype "input"))
    )
    (net (code "79") (name "Net-(FL1-D+_1)") (class "Default")
      (node (ref "FL1") (pin "3") (pinfunction "D+_1_3") (pintype "bidirectional"))
      (node (ref "J1") (pin "A7") (pinfunction "DN1_A7") (pintype "bidirectional"))
      (node (ref "J1") (pin "B7") (pinfunction "DN2_B7") (pintype "bidirectional"))
    )
    (net (code "80") (name "Net-(FL1-D-_1)") (class "Default")
      (node (ref "FL1") (pin "2") (pinfunction "D-_1_2") (pintype "bidirectional"))
      (node (ref "J1") (pin "A6") (pinfunction "DP1_A6") (pintype "bidirectional"))
      (node (ref "J1") (pin "B6") (pinfunction "DP2_B6") (pintype "bidirectional"))
    )
    (net (code "81") (name "Net-(FL1-ID)") (class "Default")
      (node (ref "FL1") (pin "4") (pinfunction "ID_4") (pintype "bidirectional"))
      (node (ref "J1") (pin "A4_B9") (pinfunction "VBUS_A4_B9") (pintype "power_in"))
      (node (ref "J1") (pin "B4_A9") (pinfunction "VBUS_B4_A9") (pintype "power_in"))
      (node (ref "L1") (pin "1") (pinfunction "1_1") (pintype "passive"))
    )
    (net (code "82") (name "Net-(FL3-OUTPUT_1)") (class "Default")
      (node (ref "FL3") (pin "12") (pinfunction "OUTPUT_1_12") (pintype "bidirectional"))
      (node (ref "J4") (pin "8") (pinfunction "8_8") (pintype "passive"))
    )
    (net (code "83") (name "Net-(FL3-OUTPUT_2)") (class "Default")
      (node (ref "FL3") (pin "11") (pinfunction "OUTPUT_2_11") (pintype "bidirectional"))
      (node (ref "J4") (pin "7") (pinfunction "7_7") (pintype "passive"))
    )
    (net (code "84") (name "Net-(FL3-OUTPUT_3)") (class "Default")
      (node (ref "FL3") (pin "10") (pinfunction "OUTPUT_3_10") (pintype "bidirectional"))
      (node (ref "J4") (pin "6") (pinfunction "6_6") (pintype "passive"))
    )
    (net (code "85") (name "Net-(FL3-OUTPUT_4)") (class "Default")
      (node (ref "FL3") (pin "9") (pinfunction "OUTPUT_4_9") (pintype "bidirectional"))
      (node (ref "J4") (pin "5") (pinfunction "5_5") (pintype "passive"))
    )
    (net (code "86") (name "Net-(FL3-OUTPUT_5)") (class "Default")
      (node (ref "FL3") (pin "8") (pinfunction "OUTPUT_5_8") (pintype "bidirectional"))
      (node (ref "J4") (pin "4") (pinfunction "4_4") (pintype "passive"))
    )
    (net (code "87") (name "Net-(FL3-OUTPUT_6)") (class "Default")
      (node (ref "FL3") (pin "7") (pinfunction "OUTPUT_6_7") (pintype "bidirectional"))
      (node (ref "J4") (pin "3") (pinfunction "3_3") (pintype "passive"))
    )
    (net (code "88") (name "Net-(FL4-OUTPUT_1)") (class "Default")
      (node (ref "FL4") (pin "12") (pinfunction "OUTPUT_1_12") (pintype "bidirectional"))
      (node (ref "J4") (pin "2") (pinfunction "2_2") (pintype "passive"))
    )
    (net (code "89") (name "Net-(IC1-VIN2)") (class "Default")
      (node (ref "C4") (pin "2") (pinfunction "2_2") (pintype "passive"))
      (node (ref "IC1") (pin "6") (pinfunction "VIN2_6") (pintype "bidirectional"))
      (node (ref "Q1") (pin "2") (pinfunction "S_2") (pintype "bidirectional"))
    )
    (net (code "90") (name "Net-(IC3-EN)") (class "Default")
      (node (ref "IC3") (pin "5") (pinfunction "EN_5") (pintype "bidirectional"))
      (node (ref "Q4") (pin "3") (pinfunction "D_3") (pintype "bidirectional"))
      (node (ref "R17") (pin "1") (pinfunction "1_1") (pintype "passive"))
    )
    (net (code "91") (name "Net-(IC3-FB)") (class "Default")
      (node (ref "IC3") (pin "1") (pinfunction "FB_1") (pintype "bidirectional"))
      (node (ref "R16") (pin "1") (pinfunction "1_1") (pintype "passive"))
      (node (ref "R18") (pin "2") (pinfunction "2_2") (pintype "passive"))
    )
    (net (code "92") (name "Net-(IC3-SW)") (class "Default")
      (node (ref "IC3") (pin "4") (pinfunction "SW_4") (pintype "bidirectional"))
      (node (ref "L2") (pin "1") (pinfunction "1_1") (pintype "passive"))
    )
    (net (code "93") (name "Net-(IC6-VCC)") (class "Default")
      (node (ref "C111") (pin "1") (pinfunction "1_1") (pintype "passive"))
      (node (ref "C112") (pin "2") (pinfunction "2_2") (pintype "passive"))
      (node (ref "IC6") (pin "15") (pinfunction "VOUT_15") (pintype "bidirectional"))
      (node (ref "IC6") (pin "18") (pinfunction "VCC_18") (pintype "power_in"))
    )
    (net (code "94") (name "Net-(IC8-LED0_{slash}_ANEN_SPEED)") (class "Default")
      (node (ref "IC8") (pin "23") (pinfunction "LED0_/_ANEN_SPEED_23") (pintype "bidirectional"))
      (node (ref "R53") (pin "1") (pinfunction "1_1") (pintype "passive"))
    )
    (net (code "95") (name "Net-(IC8-REXT)") (class "Default")
      (node (ref "IC8") (pin "9") (pinfunction "REXT_9") (pintype "bidirectional"))
      (node (ref "R55") (pin "1") (pinfunction "1_1") (pintype "passive"))
    )
    (net (code "96") (name "Net-(IC8-VDDA_3.3)") (class "Default")
      (node (ref "C43") (pin "2") (pinfunction "2_2") (pintype "passive"))
      (node (ref "C45") (pin "1") (pinfunction "1_1") (pintype "passive"))
      (node (ref "C46") (pin "1") (pinfunction "1_1") (pintype "passive"))
      (node (ref "IC8") (pin "2") (pinfunction "VDDA_3.3_2") (pintype "bidirectional"))
      (node (ref "L4") (pin "1") (pinfunction "P$1_1") (pintype "passive"))
    )
    (net (code "97") (name "Net-(IC8-VDD_1.2)") (class "Default")
      (node (ref "C44") (pin "2") (pinfunction "2_2") (pintype "passive"))
      (node (ref "C47") (pin "1") (pinfunction "1_1") (pintype "passive"))
      (node (ref "IC8") (pin "1") (pinfunction "VDD_1.2_1") (pintype "bidirectional"))
    )
    (net (code "98") (name "Net-(J1-CC1)") (class "Default")
      (node (ref "J1") (pin "A5") (pinfunction "CC1_A5") (pintype "bidirectional"))
      (node (ref "R1") (pin "1") (pinfunction "1_1") (pintype "passive"))
    )
    (net (code "99") (name "Net-(J1-CC2)") (class "Default")
      (node (ref "J1") (pin "B5") (pinfunction "CC2_B5") (pintype "bidirectional"))
      (node (ref "R2") (pin "1") (pinfunction "1_1") (pintype "passive"))
    )
    (net (code "100") (name "Net-(J6-Pad3)") (class "Default")
      (node (ref "J6") (pin "3") (pinfunction "3_3") (pintype "passive"))
      (node (ref "R45") (pin "2") (pinfunction "2_2") (pintype "passive"))
    )
    (net (code "101") (name "Net-(J6-Pad4)") (class "Default")
      (node (ref "J6") (pin "4") (pinfunction "4_4") (pintype "passive"))
      (node (ref "R44") (pin "2") (pinfunction "2_2") (pintype "passive"))
    )
    (net (code "102") (name "Net-(J8-Pad8)") (class "Default")
      (node (ref "J8") (pin "8") (pinfunction "8_8") (pintype "passive"))
      (node (ref "R48") (pin "2") (pinfunction "2_2") (pintype "passive"))
    )
    (net (code "103") (name "Net-(J8-Pad9)") (class "Default")
      (node (ref "J8") (pin "9") (pinfunction "9_9") (pintype "passive"))
      (node (ref "R49") (pin "2") (pinfunction "2_2") (pintype "passive"))
    )
    (net (code "104") (name "Net-(J9-SIGNAL)") (class "Default")
      (node (ref "C52") (pin "1") (pinfunction "1_1") (pintype "bidirectional"))
      (node (ref "J9") (pin "1") (pinfunction "SIGNAL_1") (pintype "bidirectional"))
      (node (ref "L5") (pin "2") (pinfunction "2_2") (pintype "passive"))
      (node (ref "U2") (pin "41") (pinfunction "ANT_41") (pintype "passive"))
    )
    (net (code "105") (name "Net-(S1-COM_1)") (class "Default")
      (node (ref "R66") (pin "1") (pinfunction "1_1") (pintype "passive"))
      (node (ref "R68") (pin "2") (pinfunction "2_2") (pintype "passive"))
      (node (ref "S1") (pin "2") (pinfunction "COM_1_2") (pintype "bidirectional"))
      (node (ref "S1") (pin "3") (pinfunction "COM_2_3") (pintype "bidirectional"))
      (node (ref "S1") (pin "4") (pinfunction "COM_3_4") (pintype "bidirectional"))
    )
    (net (code "106") (name "Net-(S2-COM_1)") (class "Default")
      (node (ref "R70") (pin "2") (pinfunction "2_2") (pintype "passive"))
      (node (ref "S2") (pin "2") (pinfunction "COM_1_2") (pintype "bidirectional"))
      (node (ref "S2") (pin "3") (pinfunction "COM_2_3") (pintype "bidirectional"))
      (node (ref "S2") (pin "4") (pinfunction "COM_3_4") (pintype "bidirectional"))
    )
    (net (code "107") (name "Net-(U1-ILIM)") (class "Default")
      (node (ref "R9") (pin "1") (pinfunction "1_1") (pintype "passive"))
      (node (ref "U1") (pin "12") (pinfunction "ILIM_12") (pintype "input"))
    )
    (net (code "108") (name "Net-(U1-ISET)") (class "Default")
      (node (ref "R11") (pin "1") (pinfunction "1_1") (pintype "passive"))
      (node (ref "U1") (pin "16") (pinfunction "ISET_16") (pintype "bidirectional"))
    )
    (net (code "109") (name "Net-(U1-TMR)") (class "Default")
      (node (ref "R10") (pin "1") (pinfunction "1_1") (pintype "passive"))
      (node (ref "U1") (pin "14") (pinfunction "TMR_14") (pintype "input"))
    )
    (net (code "110") (name "Net-(U1-TS)") (class "Default")
      (node (ref "R8") (pin "1") (pinfunction "1_1") (pintype "passive"))
      (node (ref "U1") (pin "1") (pinfunction "TS_1") (pintype "input"))
    )
    (net (code "111") (name "Net-(U2-LPO_IN_(32KHZ))") (class "Default")
      (node (ref "U2") (pin "37") (pinfunction "LPO_IN_(32KHZ)_37") (pintype "input"))
      (node (ref "Y1") (pin "3") (pinfunction "OUTPUT_3") (pintype "bidirectional"))
    )
    (net (code "112") (name "Net-(U2-SR_VLX)") (class "Default")
      (node (ref "L6") (pin "1") (pinfunction "1_1") (pintype "passive"))
      (node (ref "U2") (pin "34") (pinfunction "SR_VLX_34") (pintype "output"))
    )
    (net (code "113") (name "Net-(U2-VIN_LDO)") (class "Default")
      (node (ref "C54") (pin "1") (pinfunction "1_1") (pintype "passive"))
      (node (ref "C57") (pin "2") (pinfunction "2_2") (pintype "passive"))
      (node (ref "L6") (pin "2") (pinfunction "2_2") (pintype "passive"))
      (node (ref "U2") (pin "31") (pinfunction "VIN_LDO_31") (pintype "power_in"))
    )
    (net (code "114") (name "ONOFF") (class "Default")
      (node (ref "IC9") (pin "M6") (pinfunction "ONOFF_M6") (pintype "bidirectional"))
      (node (ref "Q3") (pin "2") (pinfunction "S_2") (pintype "bidirectional"))
      (node (ref "R70") (pin "1") (pinfunction "1_1") (pintype "passive"))
    )
    (net (code "115") (name "P0_MOSI") (class "Default")
      (node (ref "FL3") (pin "1") (pinfunction "INPUT_1_1") (pintype "bidirectional"))
      (node (ref "IC9") (pin "H10") (pinfunction "GPIO_AD_B0_01_H10") (pintype "bidirectional"))
    )
    (net (code "116") (name "P1_MISO") (class "Default")
      (node (ref "FL3") (pin "2") (pinfunction "INPUT_2_2") (pintype "bidirectional"))
      (node (ref "IC9") (pin "M11") (pinfunction "GPIO_AD_B0_02_M11") (pintype "bidirectional"))
    )
    (net (code "117") (name "P2_SCLK") (class "Default")
      (node (ref "FL3") (pin "3") (pinfunction "INPUT_3_3") (pintype "bidirectional"))
      (node (ref "IC9") (pin "M14") (pinfunction "GPIO_AD_B0_00_M14") (pintype "bidirectional"))
    )
    (net (code "118") (name "P3_NSS") (class "Default")
      (node (ref "FL3") (pin "4") (pinfunction "INPUT_4_4") (pintype "bidirectional"))
      (node (ref "IC9") (pin "G11") (pinfunction "GPIO_AD_B0_03_G11") (pintype "bidirectional"))
    )
    (net (code "119") (name "P4_SCL") (class "Default")
      (node (ref "FL3") (pin "5") (pinfunction "INPUT_5_5") (pintype "bidirectional"))
      (node (ref "IC9") (pin "K14") (pinfunction "GPIO_AD_B0_12_K14") (pintype "bidirectional"))
    )
    (net (code "120") (name "P5_SDA") (class "Default")
      (node (ref "FL3") (pin "6") (pinfunction "INPUT_6_6") (pintype "bidirectional"))
      (node (ref "IC9") (pin "L14") (pinfunction "GPIO_AD_B0_13_L14") (pintype "bidirectional"))
    )
    (net (code "121") (name "P6_ADC") (class "Default")
      (node (ref "FL4") (pin "1") (pinfunction "INPUT_1_1") (pintype "bidirectional"))
      (node (ref "IC9") (pin "M12") (pinfunction "GPIO_AD_B1_03_M12") (pintype "bidirectional"))
    )
    (net (code "122") (name "P7_PWM") (class "Default")
      (node (ref "FL4") (pin "2") (pinfunction "INPUT_2_2") (pintype "bidirectional"))
      (node (ref "IC9") (pin "A8") (pinfunction "GPIO_B0_06_A8") (pintype "bidirectional"))
    )
    (net (code "123") (name "P7_PWM_INT") (class "Default")
      (node (ref "FL4") (pin "11") (pinfunction "OUTPUT_2_11") (pintype "bidirectional"))
      (node (ref "J7") (pin "3") (pinfunction "3_3") (pintype "passive"))
    )
    (net (code "124") (name "P8_PWM") (class "Default")
      (node (ref "FL4") (pin "3") (pinfunction "INPUT_3_3") (pintype "bidirectional"))
      (node (ref "IC9") (pin "A9") (pinfunction "GPIO_B0_07_A9") (pintype "bidirectional"))
    )
    (net (code "125") (name "P8_PWM_INT") (class "Default")
      (node (ref "FL4") (pin "10") (pinfunction "OUTPUT_3_10") (pintype "bidirectional"))
      (node (ref "J7") (pin "4") (pinfunction "4_4") (pintype "passive"))
    )
    (net (code "126") (name "P9_PWM") (class "Default")
      (node (ref "FL4") (pin "4") (pinfunction "INPUT_4_4") (pintype "bidirectional"))
      (node (ref "IC9") (pin "A11") (pinfunction "GPIO_B1_00_A11") (pintype "bidirectional"))
    )
    (net (code "127") (name "P9_PWM_INT") (class "Default")
      (node (ref "FL4") (pin "9") (pinfunction "OUTPUT_4_9") (pintype "bidirectional"))
      (node (ref "J7") (pin "5") (pinfunction "5_5") (pintype "passive"))
    )
    (net (code "128") (name "P10_PWM") (class "Default")
      (node (ref "FL4") (pin "5") (pinfunction "INPUT_5_5") (pintype "bidirectional"))
      (node (ref "R43") (pin "1") (pinfunction "1_1") (pintype "passive"))
    )
    (net (code "129") (name "P10_PWM_INT") (class "Default")
      (node (ref "FL4") (pin "8") (pinfunction "OUTPUT_5_8") (pintype "bidirectional"))
      (node (ref "J7") (pin "6") (pinfunction "6_6") (pintype "passive"))
    )
    (net (code "130") (name "P11_WAKEUP") (class "Default")
      (node (ref "FL4") (pin "6") (pinfunction "INPUT_6_6") (pintype "bidirectional"))
      (node (ref "Q2") (pin "3") (pinfunction "D_3") (pintype "bidirectional"))
      (node (ref "R14") (pin "1") (pinfunction "1_1") (pintype "passive"))
    )
    (net (code "131") (name "P11_WAKEUP_INT") (class "Default")
      (node (ref "FL4") (pin "7") (pinfunction "OUTPUT_6_7") (pintype "bidirectional"))
      (node (ref "J7") (pin "7") (pinfunction "7_7") (pintype "passive"))
    )
    (net (code "132") (name "P12_RST_N") (class "Default")
      (node (ref "C109") (pin "1") (pinfunction "1_1") (pintype "passive"))
      (node (ref "FL5") (pin "2") (pinfunction "INPUT_2_2") (pintype "bidirectional"))
      (node (ref "IC9") (pin "M7") (pinfunction "POR_B_M7") (pintype "bidirectional"))
      (node (ref "R65") (pin "2") (pinfunction "2_2") (pintype "passive"))
    )
    (net (code "133") (name "P12_RST_N_EXT") (class "Default")
      (node (ref "FL5") (pin "11") (pinfunction "OUTPUT_2_11") (pintype "bidirectional"))
      (node (ref "J7") (pin "8") (pinfunction "8_8") (pintype "passive"))
      (node (ref "J8") (pin "10") (pinfunction "10_10") (pintype "passive"))
    )
    (net (code "134") (name "PGOOD") (class "Default")
      (node (ref "IC9") (pin "P2") (pinfunction "GPIO_SD_B1_04_P2") (pintype "bidirectional"))
      (node (ref "R12") (pin "1") (pinfunction "1_1") (pintype "passive"))
      (node (ref "R7") (pin "1") (pinfunction "1_1") (pintype "passive"))
      (node (ref "U1") (pin "7") (pinfunction "~{PGOOD}_7") (pintype "output"))
    )
    (net (code "135") (name "PMIC_ONOFF") (class "Default")
      (node (ref "D11") (pin "1") (pinfunction "1_1") (pintype "bidirectional"))
      (node (ref "J5") (pin "3") (pinfunction "3_3") (pintype "passive"))
      (node (ref "Q3") (pin "3") (pinfunction "D_3") (pintype "bidirectional"))
      (node (ref "R15") (pin "1") (pinfunction "1_1") (pintype "passive"))
    )
    (net (code "136") (name "PMIC_ON_REQ") (class "Default")
      (node (ref "IC9") (pin "K7") (pinfunction "PMIC_ON_REQ_K7") (pintype "bidirectional"))
      (node (ref "Q4") (pin "2") (pinfunction "S_2") (pintype "bidirectional"))
    )
    (net (code "137") (name "PMIC_STBY_REQ") (class "Default")
      (node (ref "IC9") (pin "L7") (pinfunction "PMIC_STBY_REQ_L7") (pintype "bidirectional"))
      (node (ref "R69") (pin "1") (pinfunction "1_1") (pintype "passive"))
    )
    (net (code "138") (name "PWM_FSIN") (class "Default")
      (node (ref "IC9") (pin "M5") (pinfunction "GPIO_SD_B1_01_M5") (pintype "bidirectional"))
      (node (ref "R41") (pin "1") (pinfunction "1_1") (pintype "passive"))
      (node (ref "R42") (pin "2") (pinfunction "2_2") (pintype "passive"))
      (node (ref "R43") (pin "2") (pinfunction "2_2") (pintype "passive"))
    )
    (net (code "139") (name "P_FLASH_CE") (class "Default")
      (node (ref "IC5") (pin "1") (pinfunction "CE#_1") (pintype "bidirectional"))
      (node (ref "IC9") (pin "L3") (pinfunction "GPIO_SD_B1_06_L3") (pintype "bidirectional"))
      (node (ref "R20") (pin "2") (pinfunction "2_2") (pintype "passive"))
    )
    (net (code "140") (name "P_FLASH_IO0") (class "Default")
      (node (ref "IC5") (pin "5") (pinfunction "SI_(IO0)_5") (pintype "bidirectional"))
      (node (ref "IC9") (pin "P3") (pinfunction "GPIO_SD_B1_08_P3") (pintype "bidirectional"))
    )
    (net (code "141") (name "P_FLASH_IO1") (class "Default")
      (node (ref "IC5") (pin "2") (pinfunction "SO_(IO1)_2") (pintype "bidirectional"))
      (node (ref "IC9") (pin "N4") (pinfunction "GPIO_SD_B1_09_N4") (pintype "bidirectional"))
    )
    (net (code "142") (name "P_FLASH_IO2") (class "Default")
      (node (ref "IC5") (pin "3") (pinfunction "WP#_(IO2)_3") (pintype "bidirectional"))
      (node (ref "IC9") (pin "P4") (pinfunction "GPIO_SD_B1_10_P4") (pintype "bidirectional"))
    )
    (net (code "143") (name "P_FLASH_IO3") (class "Default")
      (node (ref "IC5") (pin "7") (pinfunction "HOLD#_(IO3)_7") (pintype "bidirectional"))
      (node (ref "IC9") (pin "P5") (pinfunction "GPIO_SD_B1_11_P5") (pintype "bidirectional"))
    )
    (net (code "144") (name "P_FLASH_SCK") (class "Default")
      (node (ref "IC5") (pin "6") (pinfunction "SCK_6") (pintype "bidirectional"))
      (node (ref "IC9") (pin "L4") (pinfunction "GPIO_SD_B1_07_L4") (pintype "bidirectional"))
    )
    (net (code "145") (name "RAW") (class "Default")
      (node (ref "C10") (pin "1") (pinfunction "1_1") (pintype "passive"))
      (node (ref "C7") (pin "2") (pinfunction "2_2") (pintype "passive"))
      (node (ref "C8") (pin "2") (pinfunction "2_2") (pintype "passive"))
      (node (ref "D9") (pin "1") (pinfunction "1_1") (pintype "bidirectional"))
      (node (ref "IC2") (pin "1") (pinfunction "VIN_1") (pintype "bidirectional"))
      (node (ref "IC2") (pin "3") (pinfunction "CONTROL_3") (pintype "bidirectional"))
      (node (ref "IC3") (pin "3") (pinfunction "VIN_3") (pintype "bidirectional"))
      (node (ref "J5") (pin "2") (pinfunction "2_2") (pintype "passive"))
      (node (ref "R14") (pin "2") (pinfunction "2_2") (pintype "passive"))
      (node (ref "R15") (pin "2") (pinfunction "2_2") (pintype "passive"))
      (node (ref "R17") (pin "2") (pinfunction "2_2") (pintype "passive"))
      (node (ref "U1") (pin "10") (pinfunction "OUT_10_10") (pintype "output"))
      (node (ref "U1") (pin "11") (pinfunction "OUT_11_11") (pintype "output"))
      (node (ref "U1") (pin "5") (pinfunction "EN2_5") (pintype "input"))
    )
    (net (code "146") (name "RTC_XTALI") (class "Default")
      (node (ref "C108") (pin "1") (pinfunction "1_1") (pintype "passive"))
      (node (ref "IC9") (pin "N9") (pinfunction "RTC_XTALI_N9") (pintype "bidirectional"))
      (node (ref "Y3") (pin "2") (pinfunction "2_2") (pintype "passive"))
    )
    (net (code "147") (name "RTC_XTALO") (class "Default")
      (node (ref "C107") (pin "1") (pinfunction "1_1") (pintype "passive"))
      (node (ref "IC9") (pin "P9") (pinfunction "RTC_XTALO_P9") (pintype "bidirectional"))
      (node (ref "Y3") (pin "1") (pinfunction "1_1") (pintype "passive"))
    )
    (net (code "148") (name "SDRAM_A0") (class "Default")
      (node (ref "IC4") (pin "H7") (pinfunction "A0_H7") (pintype "bidirectional"))
      (node (ref "IC9") (pin "C2") (pinfunction "GPIO_EMC_09_C2") (pintype "bidirectional"))
    )
    (net (code "149") (name "SDRAM_A1") (class "Default")
      (node (ref "IC4") (pin "H8") (pinfunction "A1_H8") (pintype "bidirectional"))
      (node (ref "IC9") (pin "G1") (pinfunction "GPIO_EMC_10_G1") (pintype "bidirectional"))
    )
    (net (code "150") (name "SDRAM_A2") (class "Default")
      (node (ref "IC4") (pin "J8") (pinfunction "A2_J8") (pintype "bidirectional"))
      (node (ref "IC9") (pin "G3") (pinfunction "GPIO_EMC_11_G3") (pintype "bidirectional"))
    )
    (net (code "151") (name "SDRAM_A3") (class "Default")
      (node (ref "IC4") (pin "J7") (pinfunction "A3_J7") (pintype "bidirectional"))
      (node (ref "IC9") (pin "H1") (pinfunction "GPIO_EMC_12_H1") (pintype "bidirectional"))
    )
    (net (code "152") (name "SDRAM_A4") (class "Default")
      (node (ref "IC4") (pin "J3") (pinfunction "A4_J3") (pintype "bidirectional"))
      (node (ref "IC9") (pin "A6") (pinfunction "GPIO_EMC_13_A6") (pintype "bidirectional"))
    )
    (net (code "153") (name "SDRAM_A5") (class "Default")
      (node (ref "IC4") (pin "J2") (pinfunction "A5_J2") (pintype "bidirectional"))
      (node (ref "IC9") (pin "B6") (pinfunction "GPIO_EMC_14_B6") (pintype "bidirectional"))
    )
    (net (code "154") (name "SDRAM_A6") (class "Default")
      (node (ref "IC4") (pin "H3") (pinfunction "A6_H3") (pintype "bidirectional"))
      (node (ref "IC9") (pin "B1") (pinfunction "GPIO_EMC_15_B1") (pintype "bidirectional"))
    )
    (net (code "155") (name "SDRAM_A7") (class "Default")
      (node (ref "IC4") (pin "H2") (pinfunction "A7_H2") (pintype "bidirectional"))
      (node (ref "IC9") (pin "A5") (pinfunction "GPIO_EMC_16_A5") (pintype "bidirectional"))
    )
    (net (code "156") (name "SDRAM_A8") (class "Default")
      (node (ref "IC4") (pin "H1") (pinfunction "A8_H1") (pintype "bidirectional"))
      (node (ref "IC9") (pin "A4") (pinfunction "GPIO_EMC_17_A4") (pintype "bidirectional"))
    )
    (net (code "157") (name "SDRAM_A9") (class "Default")
      (node (ref "IC4") (pin "G3") (pinfunction "A9_G3") (pintype "bidirectional"))
      (node (ref "IC9") (pin "B2") (pinfunction "GPIO_EMC_18_B2") (pintype "bidirectional"))
    )
    (net (code "158") (name "SDRAM_A10") (class "Default")
      (node (ref "IC4") (pin "H9") (pinfunction "A10_H9") (pintype "bidirectional"))
      (node (ref "IC9") (pin "G2") (pinfunction "GPIO_EMC_23_G2") (pintype "bidirectional"))
    )
    (net (code "159") (name "SDRAM_A11") (class "Default")
      (node (ref "IC4") (pin "G2") (pinfunction "A11_G2") (pintype "bidirectional"))
      (node (ref "IC9") (pin "B4") (pinfunction "GPIO_EMC_19_B4") (pintype "bidirectional"))
    )
    (net (code "160") (name "SDRAM_A12") (class "Default")
      (node (ref "IC4") (pin "G1") (pinfunction "A12_G1") (pintype "bidirectional"))
      (node (ref "IC9") (pin "A3") (pinfunction "GPIO_EMC_20_A3") (pintype "bidirectional"))
    )
    (net (code "161") (name "SDRAM_BA0") (class "Default")
      (node (ref "IC4") (pin "G7") (pinfunction "BA0_G7") (pintype "bidirectional"))
      (node (ref "IC9") (pin "C1") (pinfunction "GPIO_EMC_21_C1") (pintype "bidirectional"))
    )
    (net (code "162") (name "SDRAM_BA1") (class "Default")
      (node (ref "IC4") (pin "G8") (pinfunction "BA1_G8") (pintype "bidirectional"))
      (node (ref "IC9") (pin "F1") (pinfunction "GPIO_EMC_22_F1") (pintype "bidirectional"))
    )
    (net (code "163") (name "SDRAM_CAS") (class "Default")
      (node (ref "IC4") (pin "F7") (pinfunction "~{CAS}_F7") (pintype "bidirectional"))
      (node (ref "IC9") (pin "D3") (pinfunction "GPIO_EMC_24_D3") (pintype "bidirectional"))
    )
    (net (code "164") (name "SDRAM_CKE") (class "Default")
      (node (ref "IC4") (pin "F3") (pinfunction "CKE_F3") (pintype "bidirectional"))
      (node (ref "IC9") (pin "A2") (pinfunction "GPIO_EMC_27_A2") (pintype "bidirectional"))
    )
    (net (code "165") (name "SDRAM_CLK") (class "Default")
      (node (ref "IC4") (pin "F2") (pinfunction "CLK_F2") (pintype "bidirectional"))
      (node (ref "IC9") (pin "B3") (pinfunction "GPIO_EMC_26_B3") (pintype "bidirectional"))
    )
    (net (code "166") (name "SDRAM_CS") (class "Default")
      (node (ref "IC4") (pin "G9") (pinfunction "~{CS}_G9") (pintype "bidirectional"))
      (node (ref "IC9") (pin "E1") (pinfunction "GPIO_EMC_29_E1") (pintype "bidirectional"))
      (node (ref "R19") (pin "2") (pinfunction "2_2") (pintype "passive"))
    )
    (net (code "167") (name "SDRAM_DQ0") (class "Default")
      (node (ref "IC4") (pin "A8") (pinfunction "DQ0_A8") (pintype "bidirectional"))
      (node (ref "IC9") (pin "E3") (pinfunction "GPIO_EMC_00_E3") (pintype "bidirectional"))
    )
    (net (code "168") (name "SDRAM_DQ1") (class "Default")
      (node (ref "IC4") (pin "B9") (pinfunction "DQ1_B9") (pintype "bidirectional"))
      (node (ref "IC9") (pin "F3") (pinfunction "GPIO_EMC_01_F3") (pintype "bidirectional"))
    )
    (net (code "169") (name "SDRAM_DQ2") (class "Default")
      (node (ref "IC4") (pin "B8") (pinfunction "DQ2_B8") (pintype "bidirectional"))
      (node (ref "IC9") (pin "F4") (pinfunction "GPIO_EMC_02_F4") (pintype "bidirectional"))
    )
    (net (code "170") (name "SDRAM_DQ3") (class "Default")
      (node (ref "IC4") (pin "C9") (pinfunction "DQ3_C9") (pintype "bidirectional"))
      (node (ref "IC9") (pin "G4") (pinfunction "GPIO_EMC_03_G4") (pintype "bidirectional"))
    )
    (net (code "171") (name "SDRAM_DQ4") (class "Default")
      (node (ref "IC4") (pin "C8") (pinfunction "DQ4_C8") (pintype "bidirectional"))
      (node (ref "IC9") (pin "F2") (pinfunction "GPIO_EMC_04_F2") (pintype "bidirectional"))
    )
    (net (code "172") (name "SDRAM_DQ5") (class "Default")
      (node (ref "IC4") (pin "D9") (pinfunction "DQ5_D9") (pintype "bidirectional"))
      (node (ref "IC9") (pin "G5") (pinfunction "GPIO_EMC_05_G5") (pintype "bidirectional"))
    )
    (net (code "173") (name "SDRAM_DQ6") (class "Default")
      (node (ref "IC4") (pin "D8") (pinfunction "DQ6_D8") (pintype "bidirectional"))
      (node (ref "IC9") (pin "H5") (pinfunction "GPIO_EMC_06_H5") (pintype "bidirectional"))
    )
    (net (code "174") (name "SDRAM_DQ7") (class "Default")
      (node (ref "IC4") (pin "E9") (pinfunction "DQ7_E9") (pintype "bidirectional"))
      (node (ref "IC9") (pin "H4") (pinfunction "GPIO_EMC_07_H4") (pintype "bidirectional"))
    )
    (net (code "175") (name "SDRAM_DQ8") (class "Default")
      (node (ref "IC4") (pin "E1") (pinfunction "DQ8_E1") (pintype "bidirectional"))
      (node (ref "IC9") (pin "C6") (pinfunction "GPIO_EMC_30_C6") (pintype "bidirectional"))
    )
    (net (code "176") (name "SDRAM_DQ9") (class "Default")
      (node (ref "IC4") (pin "D2") (pinfunction "DQ9_D2") (pintype "bidirectional"))
      (node (ref "IC9") (pin "C5") (pinfunction "GPIO_EMC_31_C5") (pintype "bidirectional"))
    )
    (net (code "177") (name "SDRAM_DQ10") (class "Default")
      (node (ref "IC4") (pin "D1") (pinfunction "DQ10_D1") (pintype "bidirectional"))
      (node (ref "IC9") (pin "D5") (pinfunction "GPIO_EMC_32_D5") (pintype "bidirectional"))
    )
    (net (code "178") (name "SDRAM_DQ11") (class "Default")
      (node (ref "IC4") (pin "C2") (pinfunction "DQ11_C2") (pintype "bidirectional"))
      (node (ref "IC9") (pin "C4") (pinfunction "GPIO_EMC_33_C4") (pintype "bidirectional"))
    )
    (net (code "179") (name "SDRAM_DQ12") (class "Default")
      (node (ref "IC4") (pin "C1") (pinfunction "DQ12_C1") (pintype "bidirectional"))
      (node (ref "IC9") (pin "D4") (pinfunction "GPIO_EMC_34_D4") (pintype "bidirectional"))
    )
    (net (code "180") (name "SDRAM_DQ13") (class "Default")
      (node (ref "IC4") (pin "B2") (pinfunction "DQ13_B2") (pintype "bidirectional"))
      (node (ref "IC9") (pin "E5") (pinfunction "GPIO_EMC_35_E5") (pintype "bidirectional"))
    )
    (net (code "181") (name "SDRAM_DQ14") (class "Default")
      (node (ref "IC4") (pin "B1") (pinfunction "DQ14_B1") (pintype "bidirectional"))
      (node (ref "IC9") (pin "C3") (pinfunction "GPIO_EMC_36_C3") (pintype "bidirectional"))
    )
    (net (code "182") (name "SDRAM_DQ15") (class "Default")
      (node (ref "IC4") (pin "A2") (pinfunction "DQ15_A2") (pintype "bidirectional"))
      (node (ref "IC9") (pin "E4") (pinfunction "GPIO_EMC_37_E4") (pintype "bidirectional"))
    )
    (net (code "183") (name "SDRAM_DQMH") (class "Default")
      (node (ref "IC4") (pin "F1") (pinfunction "DQMH_F1") (pintype "bidirectional"))
      (node (ref "IC9") (pin "D6") (pinfunction "GPIO_EMC_38_D6") (pintype "bidirectional"))
    )
    (net (code "184") (name "SDRAM_DQML") (class "Default")
      (node (ref "IC4") (pin "E8") (pinfunction "DQML_E8") (pintype "bidirectional"))
      (node (ref "IC9") (pin "H3") (pinfunction "GPIO_EMC_08_H3") (pintype "bidirectional"))
    )
    (net (code "185") (name "SDRAM_RAS") (class "Default")
      (node (ref "IC4") (pin "F8") (pinfunction "~{RAS}_F8") (pintype "bidirectional"))
      (node (ref "IC9") (pin "D2") (pinfunction "GPIO_EMC_25_D2") (pintype "bidirectional"))
    )
    (net (code "186") (name "SDRAM_WE") (class "Default")
      (node (ref "IC4") (pin "F9") (pinfunction "~{WE}_F9") (pintype "bidirectional"))
      (node (ref "IC9") (pin "D1") (pinfunction "GPIO_EMC_28_D1") (pintype "bidirectional"))
    )
    (net (code "187") (name "SD_CD") (class "Default")
      (node (ref "D7") (pin "1") (pinfunction "1_1") (pintype "bidirectional"))
      (node (ref "IC9") (pin "L11") (pinfunction "GPIO_AD_B1_02_L11") (pintype "bidirectional"))
      (node (ref "J2") (pin "CD$1") (pinfunction "CD_CD$1") (pintype "power_in"))
      (node (ref "R30") (pin "1") (pinfunction "1_1") (pintype "passive"))
    )
    (net (code "188") (name "SD_CLK") (class "Default")
      (node (ref "FL2") (pin "4") (pinfunction "INPUT_4_4") (pintype "bidirectional"))
      (node (ref "IC9") (pin "J3") (pinfunction "GPIO_SD_B0_01_J3") (pintype "bidirectional"))
    )
    (net (code "189") (name "SD_CLK_INT") (class "Default")
      (node (ref "FL2") (pin "9") (pinfunction "OUTPUT_4_9") (pintype "bidirectional"))
      (node (ref "J2") (pin "P$5") (pinfunction "CLK_P$5") (pintype "bidirectional"))
    )
    (net (code "190") (name "SD_CMD") (class "Default")
      (node (ref "FL2") (pin "3") (pinfunction "INPUT_3_3") (pintype "bidirectional"))
      (node (ref "IC9") (pin "J4") (pinfunction "GPIO_SD_B0_00_J4") (pintype "bidirectional"))
      (node (ref "R33") (pin "1") (pinfunction "1_1") (pintype "passive"))
    )
    (net (code "191") (name "SD_CMD_INT") (class "Default")
      (node (ref "FL2") (pin "10") (pinfunction "OUTPUT_3_10") (pintype "bidirectional"))
      (node (ref "J2") (pin "P$3") (pinfunction "CMD_P$3") (pintype "bidirectional"))
    )
    (net (code "192") (name "SD_DAT0") (class "Default")
      (node (ref "FL2") (pin "5") (pinfunction "INPUT_5_5") (pintype "bidirectional"))
      (node (ref "IC9") (pin "J1") (pinfunction "GPIO_SD_B0_02_J1") (pintype "bidirectional"))
      (node (ref "R32") (pin "1") (pinfunction "1_1") (pintype "passive"))
    )
    (net (code "193") (name "SD_DAT0_INT") (class "Default")
      (node (ref "FL2") (pin "8") (pinfunction "OUTPUT_5_8") (pintype "bidirectional"))
      (node (ref "J2") (pin "P$7") (pinfunction "DAT0_P$7") (pintype "bidirectional"))
    )
    (net (code "194") (name "SD_DAT1") (class "Default")
      (node (ref "FL2") (pin "6") (pinfunction "INPUT_6_6") (pintype "bidirectional"))
      (node (ref "IC9") (pin "K1") (pinfunction "GPIO_SD_B0_03_K1") (pintype "bidirectional"))
      (node (ref "R31") (pin "1") (pinfunction "1_1") (pintype "passive"))
    )
    (net (code "195") (name "SD_DAT1_INT") (class "Default")
      (node (ref "FL2") (pin "7") (pinfunction "OUTPUT_6_7") (pintype "bidirectional"))
      (node (ref "J2") (pin "P$8") (pinfunction "DAT1_P$8") (pintype "bidirectional"))
    )
    (net (code "196") (name "SD_DAT2") (class "Default")
      (node (ref "FL2") (pin "1") (pinfunction "INPUT_1_1") (pintype "bidirectional"))
      (node (ref "IC9") (pin "H2") (pinfunction "GPIO_SD_B0_04_H2") (pintype "bidirectional"))
      (node (ref "R35") (pin "1") (pinfunction "1_1") (pintype "passive"))
    )
    (net (code "197") (name "SD_DAT2_INT") (class "Default")
      (node (ref "FL2") (pin "12") (pinfunction "OUTPUT_1_12") (pintype "bidirectional"))
      (node (ref "J2") (pin "P$1") (pinfunction "DAT2_P$1") (pintype "bidirectional"))
    )
    (net (code "198") (name "SD_DAT3") (class "Default")
      (node (ref "FL2") (pin "2") (pinfunction "INPUT_2_2") (pintype "bidirectional"))
      (node (ref "IC9") (pin "J2") (pinfunction "GPIO_SD_B0_05_J2") (pintype "bidirectional"))
      (node (ref "R34") (pin "1") (pinfunction "1_1") (pintype "passive"))
    )
    (net (code "199") (name "SD_DAT3_INT") (class "Default")
      (node (ref "FL2") (pin "11") (pinfunction "OUTPUT_2_11") (pintype "bidirectional"))
      (node (ref "J2") (pin "P$2") (pinfunction "DAT3/CD_P$2") (pintype "bidirectional"))
    )
    (net (code "200") (name "ST") (class "Default")
      (node (ref "IC1") (pin "8") (pinfunction "ST_8") (pintype "bidirectional"))
      (node (ref "R4") (pin "1") (pinfunction "1_1") (pintype "passive"))
      (node (ref "R5") (pin "1") (pinfunction "1_1") (pintype "passive"))
      (node (ref "R50") (pin "2") (pinfunction "2_2") (pintype "passive"))
    )
    (net (code "201") (name "USB_D_N") (class "Default")
      (node (ref "FL1") (pin "6") (pinfunction "D+_2_6") (pintype "bidirectional"))
      (node (ref "IC9") (pin "M8") (pinfunction "USB_OTG1_DN_M8") (pintype "bidirectional"))
    )
    (net (code "202") (name "USB_D_P") (class "Default")
      (node (ref "FL1") (pin "7") (pinfunction "D-_2_7") (pintype "bidirectional"))
      (node (ref "IC9") (pin "L8") (pinfunction "USB_OTG1_DP_L8") (pintype "bidirectional"))
    )
    (net (code "203") (name "VBUS") (class "Default")
      (node (ref "C2") (pin "2") (pinfunction "2_2") (pintype "passive"))
      (node (ref "C90") (pin "1") (pinfunction "1_1") (pintype "passive"))
      (node (ref "C92") (pin "2") (pinfunction "2_2") (pintype "passive"))
      (node (ref "FL1") (pin "1") (pinfunction "VBUS_1") (pintype "bidirectional"))
      (node (ref "IC1") (pin "3") (pinfunction "VIN1_3") (pintype "bidirectional"))
      (node (ref "IC9") (pin "N6") (pinfunction "USB_OTG1_VBUS_N6") (pintype "bidirectional"))
      (node (ref "L1") (pin "2") (pinfunction "2_2") (pintype "passive"))
    )
    (net (code "204") (name "VCC") (class "Default")
      (node (ref "C103") (pin "2") (pinfunction "2_2") (pintype "passive"))
      (node (ref "C104") (pin "1") (pinfunction "1_1") (pintype "passive"))
      (node (ref "C11") (pin "1") (pinfunction "1_1") (pintype "passive"))
      (node (ref "C113") (pin "2") (pinfunction "2_2") (pintype "passive"))
      (node (ref "C12") (pin "2") (pinfunction "2_2") (pintype "passive"))
      (node (ref "C13") (pin "1") (pinfunction "1_1") (pintype "passive"))
      (node (ref "C14") (pin "1") (pinfunction "1_1") (pintype "passive"))
      (node (ref "C15") (pin "1") (pinfunction "1_1") (pintype "passive"))
      (node (ref "C16") (pin "1") (pinfunction "1_1") (pintype "passive"))
      (node (ref "C17") (pin "1") (pinfunction "1_1") (pintype "passive"))
      (node (ref "C18") (pin "2") (pinfunction "2_2") (pintype "passive"))
      (node (ref "C19") (pin "2") (pinfunction "2_2") (pintype "passive"))
      (node (ref "C20") (pin "1") (pinfunction "1_1") (pintype "passive"))
      (node (ref "C21") (pin "1") (pinfunction "1_1") (pintype "passive"))
      (node (ref "C22") (pin "1") (pinfunction "1_1") (pintype "passive"))
      (node (ref "C23") (pin "1") (pinfunction "1_1") (pintype "passive"))
      (node (ref "C24") (pin "2") (pinfunction "2_2") (pintype "passive"))
      (node (ref "C25") (pin "2") (pinfunction "2_2") (pintype "passive"))
      (node (ref "C26") (pin "1") (pinfunction "1_1") (pintype "passive"))
      (node (ref "C27") (pin "2") (pinfunction "2_2") (pintype "passive"))
      (node (ref "C28") (pin "2") (pinfunction "2_2") (pintype "passive"))
      (node (ref "C29") (pin "1") (pinfunction "1_1") (pintype "passive"))
      (node (ref "C30") (pin "1") (pinfunction "1_1") (pintype "passive"))
      (node (ref "C31") (pin "2") (pinfunction "2_2") (pintype "passive"))
      (node (ref "C32") (pin "1") (pinfunction "1_1") (pintype "passive"))
      (node (ref "C33") (pin "1") (pinfunction "1_1") (pintype "passive"))
      (node (ref "C34") (pin "1") (pinfunction "1_1") (pintype "passive"))
      (node (ref "C35") (pin "2") (pinfunction "2_2") (pintype "passive"))
      (node (ref "C36") (pin "2") (pinfunction "2_2") (pintype "passive"))
      (node (ref "C37") (pin "2") (pinfunction "2_2") (pintype "passive"))
      (node (ref "C38") (pin "2") (pinfunction "2_2") (pintype "passive"))
      (node (ref "C39") (pin "2") (pinfunction "2_2") (pintype "passive"))
      (node (ref "C48") (pin "2") (pinfunction "2_2") (pintype "passive"))
      (node (ref "C49") (pin "1") (pinfunction "1_1") (pintype "passive"))
      (node (ref "C50") (pin "1") (pinfunction "1_1") (pintype "passive"))
      (node (ref "C51") (pin "1") (pinfunction "1_1") (pintype "passive"))
      (node (ref "C55") (pin "1") (pinfunction "1_1") (pintype "passive"))
      (node (ref "C56") (pin "1") (pinfunction "1_1") (pintype "passive"))
      (node (ref "C58") (pin "2") (pinfunction "2_2") (pintype "passive"))
      (node (ref "C59") (pin "2") (pinfunction "2_2") (pintype "passive"))
      (node (ref "C66") (pin "2") (pinfunction "2_2") (pintype "passive"))
      (node (ref "C67") (pin "1") (pinfunction "1_1") (pintype "passive"))
      (node (ref "C69") (pin "1") (pinfunction "1_1") (pintype "passive"))
      (node (ref "C70") (pin "1") (pinfunction "1_1") (pintype "passive"))
      (node (ref "C71") (pin "1") (pinfunction "1_1") (pintype "passive"))
      (node (ref "C75") (pin "1") (pinfunction "1_1") (pintype "passive"))
      (node (ref "C76") (pin "1") (pinfunction "1_1") (pintype "passive"))
      (node (ref "C77") (pin "2") (pinfunction "2_2") (pintype "passive"))
      (node (ref "C78") (pin "2") (pinfunction "2_2") (pintype "passive"))
      (node (ref "C82") (pin "1") (pinfunction "1_1") (pintype "passive"))
      (node (ref "C83") (pin "2") (pinfunction "2_2") (pintype "passive"))
      (node (ref "C84") (pin "1") (pinfunction "1_1") (pintype "passive"))
      (node (ref "C85") (pin "2") (pinfunction "2_2") (pintype "passive"))
      (node (ref "C88") (pin "2") (pinfunction "2_2") (pintype "passive"))
      (node (ref "C95") (pin "2") (pinfunction "2_2") (pintype "passive"))
      (node (ref "D1") (pin "4") (pinfunction "ANODE_4") (pintype "passive"))
      (node (ref "D12") (pin "1") (pinfunction "1_1") (pintype "bidirectional"))
      (node (ref "D14") (pin "1") (pinfunction "1_1") (pintype "bidirectional"))
      (node (ref "D5") (pin "4") (pinfunction "ANODE_4") (pintype "passive"))
      (node (ref "D6") (pin "1") (pinfunction "1_1") (pintype "bidirectional"))
      (node (ref "D8") (pin "1") (pinfunction "1_1") (pintype "bidirectional"))
      (node (ref "IC3") (pin "6") (pinfunction "OUT_6") (pintype "bidirectional"))
      (node (ref "IC4") (pin "A7") (pinfunction "VDDQ_1_A7") (pintype "bidirectional"))
      (node (ref "IC4") (pin "A9") (pinfunction "VDD_1_A9") (pintype "bidirectional"))
      (node (ref "IC4") (pin "B3") (pinfunction "VDDQ_2_B3") (pintype "bidirectional"))
      (node (ref "IC4") (pin "C7") (pinfunction "VDDQ_3_C7") (pintype "bidirectional"))
      (node (ref "IC4") (pin "D3") (pinfunction "VDDQ_4_D3") (pintype "bidirectional"))
      (node (ref "IC4") (pin "E7") (pinfunction "VDD_2_E7") (pintype "bidirectional"))
      (node (ref "IC4") (pin "J9") (pinfunction "VDD_3_J9") (pintype "bidirectional"))
      (node (ref "IC5") (pin "8") (pinfunction "VCC_8") (pintype "bidirectional"))
      (node (ref "IC6") (pin "11") (pinfunction "ENA_11") (pintype "input"))
      (node (ref "IC6") (pin "12") (pinfunction "VIN_12") (pintype "power_in"))
      (node (ref "IC7") (pin "6") (pinfunction "VDD_6") (pintype "bidirectional"))
      (node (ref "IC8") (pin "14") (pinfunction "VDDIO_14") (pintype "bidirectional"))
      (node (ref "IC9") (pin "E6") (pinfunction "NVCC_EMC_1_E6") (pintype "bidirectional"))
      (node (ref "IC9") (pin "E9") (pinfunction "NVCC_GPIO_1_E9") (pintype "bidirectional"))
      (node (ref "IC9") (pin "F10") (pinfunction "NVCC_GPIO_2_F10") (pintype "bidirectional"))
      (node (ref "IC9") (pin "F5") (pinfunction "NVCC_EMC_2_F5") (pintype "bidirectional"))
      (node (ref "IC9") (pin "J10") (pinfunction "NVCC_GPIO_3_J10") (pintype "bidirectional"))
      (node (ref "IC9") (pin "J6") (pinfunction "NVCC_SD0_J6") (pintype "bidirectional"))
      (node (ref "IC9") (pin "K4") (pinfunction "DCDC_IN_Q_K4") (pintype "bidirectional"))
      (node (ref "IC9") (pin "K5") (pinfunction "NVCC_SD1_K5") (pintype "bidirectional"))
      (node (ref "IC9") (pin "L1") (pinfunction "DCDC_IN_1_L1") (pintype "bidirectional"))
      (node (ref "IC9") (pin "L2") (pinfunction "DCDC_IN_2_L2") (pintype "bidirectional"))
      (node (ref "IC9") (pin "P12") (pinfunction "VDD_HIGH_IN_P12") (pintype "bidirectional"))
      (node (ref "J2") (pin "P$4") (pinfunction "VDD_P$4") (pintype "power_in"))
      (node (ref "J3") (pin "10") (pinfunction "10_10") (pintype "bidirectional"))
      (node (ref "J3") (pin "2") (pinfunction "2_2") (pintype "bidirectional"))
      (node (ref "J3") (pin "20") (pinfunction "20_20") (pintype "bidirectional"))
      (node (ref "J3") (pin "30") (pinfunction "30_30") (pintype "bidirectional"))
      (node (ref "J3") (pin "36") (pinfunction "36_36") (pintype "bidirectional"))
      (node (ref "J4") (pin "1") (pinfunction "1_1") (pintype "passive"))
      (node (ref "J6") (pin "1") (pinfunction "1_1") (pintype "passive"))
      (node (ref "J8") (pin "1") (pinfunction "1_1") (pintype "passive"))
      (node (ref "L2") (pin "2") (pinfunction "2_2") (pintype "passive"))
      (node (ref "L3") (pin "2") (pinfunction "P$2_2") (pintype "passive"))
      (node (ref "L4") (pin "2") (pinfunction "P$2_2") (pintype "passive"))
      (node (ref "L8") (pin "2") (pinfunction "P$2_2") (pintype "passive"))
      (node (ref "R12") (pin "2") (pinfunction "2_2") (pintype "passive"))
      (node (ref "R13") (pin "2") (pinfunction "2_2") (pintype "passive"))
      (node (ref "R16") (pin "2") (pinfunction "2_2") (pintype "passive"))
      (node (ref "R19") (pin "1") (pinfunction "1_1") (pintype "passive"))
      (node (ref "R20") (pin "1") (pinfunction "1_1") (pintype "passive"))
      (node (ref "R24") (pin "2") (pinfunction "2_2") (pintype "passive"))
      (node (ref "R25") (pin "2") (pinfunction "2_2") (pintype "passive"))
      (node (ref "R26") (pin "2") (pinfunction "2_2") (pintype "passive"))
      (node (ref "R27") (pin "2") (pinfunction "2_2") (pintype "passive"))
      (node (ref "R28") (pin "2") (pinfunction "2_2") (pintype "passive"))
      (node (ref "R29") (pin "2") (pinfunction "2_2") (pintype "passive"))
      (node (ref "R30") (pin "2") (pinfunction "2_2") (pintype "passive"))
      (node (ref "R31") (pin "2") (pinfunction "2_2") (pintype "passive"))
      (node (ref "R32") (pin "2") (pinfunction "2_2") (pintype "passive"))
      (node (ref "R33") (pin "2") (pinfunction "2_2") (pintype "passive"))
      (node (ref "R34") (pin "2") (pinfunction "2_2") (pintype "passive"))
      (node (ref "R35") (pin "2") (pinfunction "2_2") (pintype "passive"))
      (node (ref "R36") (pin "2") (pinfunction "2_2") (pintype "passive"))
      (node (ref "R38") (pin "2") (pinfunction "2_2") (pintype "passive"))
      (node (ref "R39") (pin "2") (pinfunction "2_2") (pintype "passive"))
      (node (ref "R4") (pin "2") (pinfunction "2_2") (pintype "passive"))
      (node (ref "R40") (pin "2") (pinfunction "2_2") (pintype "passive"))
      (node (ref "R41") (pin "2") (pinfunction "2_2") (pintype "passive"))
      (node (ref "R52") (pin "2") (pinfunction "2_2") (pintype "passive"))
      (node (ref "R54") (pin "2") (pinfunction "2_2") (pintype "passive"))
      (node (ref "R56") (pin "2") (pinfunction "2_2") (pintype "passive"))
      (node (ref "R57") (pin "2") (pinfunction "2_2") (pintype "passive"))
      (node (ref "R58") (pin "2") (pinfunction "2_2") (pintype "passive"))
      (node (ref "R59") (pin "2") (pinfunction "2_2") (pintype "passive"))
      (node (ref "R60") (pin "2") (pinfunction "2_2") (pintype "passive"))
      (node (ref "R61") (pin "2") (pinfunction "2_2") (pintype "passive"))
      (node (ref "R62") (pin "2") (pinfunction "2_2") (pintype "passive"))
      (node (ref "R63") (pin "2") (pinfunction "2_2") (pintype "passive"))
      (node (ref "R64") (pin "2") (pinfunction "2_2") (pintype "passive"))
      (node (ref "R65") (pin "1") (pinfunction "1_1") (pintype "passive"))
      (node (ref "R66") (pin "2") (pinfunction "2_2") (pintype "passive"))
      (node (ref "U2") (pin "30") (pinfunction "VBAT_30") (pintype "power_in"))
      (node (ref "U2") (pin "36") (pinfunction "VIO_36") (pintype "power_in"))
      (node (ref "Y1") (pin "1") (pinfunction "TRI-STATE_1") (pintype "bidirectional"))
      (node (ref "Y1") (pin "4") (pinfunction "VDD_4") (pintype "bidirectional"))
    )
    (net (code "205") (name "VCC_SOC") (class "Default")
      (node (ref "C100") (pin "2") (pinfunction "2_2") (pintype "passive"))
      (node (ref "C60") (pin "1") (pinfunction "1_1") (pintype "passive"))
      (node (ref "C61") (pin "1") (pinfunction "1_1") (pintype "passive"))
      (node (ref "C62") (pin "2") (pinfunction "2_2") (pintype "passive"))
      (node (ref "C63") (pin "1") (pinfunction "1_1") (pintype "passive"))
      (node (ref "C64") (pin "1") (pinfunction "1_1") (pintype "passive"))
      (node (ref "C65") (pin "2") (pinfunction "2_2") (pintype "passive"))
      (node (ref "C68") (pin "1") (pinfunction "1_1") (pintype "passive"))
      (node (ref "C89") (pin "2") (pinfunction "2_2") (pintype "passive"))
      (node (ref "C91") (pin "2") (pinfunction "2_2") (pintype "passive"))
      (node (ref "C93") (pin "2") (pinfunction "2_2") (pintype "passive"))
      (node (ref "C94") (pin "2") (pinfunction "2_2") (pintype "passive"))
      (node (ref "C97") (pin "2") (pinfunction "2_2") (pintype "passive"))
      (node (ref "IC9") (pin "F6") (pinfunction "VDD_SOC_IN_1_F6") (pintype "bidirectional"))
      (node (ref "IC9") (pin "F7") (pinfunction "VDD_SOC_IN_2_F7") (pintype "bidirectional"))
      (node (ref "IC9") (pin "F8") (pinfunction "VDD_SOC_IN_3_F8") (pintype "bidirectional"))
      (node (ref "IC9") (pin "F9") (pinfunction "VDD_SOC_IN_4_F9") (pintype "bidirectional"))
      (node (ref "IC9") (pin "G6") (pinfunction "VDD_SOC_IN_5_G6") (pintype "bidirectional"))
      (node (ref "IC9") (pin "G9") (pinfunction "VDD_SOC_IN_6_G9") (pintype "bidirectional"))
      (node (ref "IC9") (pin "H6") (pinfunction "VDD_SOC_IN_7_H6") (pintype "bidirectional"))
      (node (ref "IC9") (pin "H9") (pinfunction "VDD_SOC_IN_8_H9") (pintype "bidirectional"))
      (node (ref "IC9") (pin "J5") (pinfunction "DCDC_SENSE_J5") (pintype "bidirectional"))
      (node (ref "IC9") (pin "J9") (pinfunction "VDD_SOC_IN_9_J9") (pintype "bidirectional"))
      (node (ref "L7") (pin "1") (pinfunction "1_1") (pintype "passive"))
    )
    (net (code "206") (name "VDDA") (class "Default")
      (node (ref "C40") (pin "1") (pinfunction "1_1") (pintype "passive"))
      (node (ref "C41") (pin "2") (pinfunction "2_2") (pintype "passive"))
      (node (ref "J3") (pin "4") (pinfunction "4_4") (pintype "bidirectional"))
      (node (ref "L3") (pin "1") (pinfunction "P$1_1") (pintype "passive"))
    )
    (net (code "207") (name "VDDA_ADC_3P3") (class "Default")
      (node (ref "C72") (pin "2") (pinfunction "2_2") (pintype "passive"))
      (node (ref "C73") (pin "1") (pinfunction "1_1") (pintype "passive"))
      (node (ref "C74") (pin "2") (pinfunction "2_2") (pintype "passive"))
      (node (ref "IC9") (pin "N14") (pinfunction "VDDA_ADC_3P3_N14") (pintype "bidirectional"))
      (node (ref "L8") (pin "1") (pinfunction "P$1_1") (pintype "passive"))
    )
    (net (code "208") (name "VDD_HIGH_CAP") (class "Default")
      (node (ref "C98") (pin "2") (pinfunction "2_2") (pintype "passive"))
      (node (ref "C99") (pin "1") (pinfunction "1_1") (pintype "passive"))
      (node (ref "IC9") (pin "P8") (pinfunction "VDD_HIGH_CAP_P8") (pintype "bidirectional"))
    )
    (net (code "209") (name "VDD_SNVS") (class "Default")
      (node (ref "C9") (pin "2") (pinfunction "2_2") (pintype "passive"))
      (node (ref "D15") (pin "1") (pinfunction "A1_1") (pintype "bidirectional"))
      (node (ref "IC2") (pin "5") (pinfunction "VOUT_5") (pintype "bidirectional"))
    )
    (net (code "210") (name "VDD_SNVS_CAP") (class "Default")
      (node (ref "C87") (pin "1") (pinfunction "1_1") (pintype "passive"))
      (node (ref "IC9") (pin "M10") (pinfunction "VDD_SNVS_CAP_M10") (pintype "bidirectional"))
    )
    (net (code "211") (name "VDD_SNVS_CPU") (class "Default")
      (node (ref "C86") (pin "1") (pinfunction "1_1") (pintype "passive"))
      (node (ref "D15") (pin "3") (pinfunction "K_3") (pintype "bidirectional"))
      (node (ref "IC9") (pin "M9") (pinfunction "VDD_SNVS_IN_M9") (pintype "bidirectional"))
      (node (ref "Q2") (pin "1") (pinfunction "G_1") (pintype "bidirectional"))
      (node (ref "Q3") (pin "1") (pinfunction "G_1") (pintype "bidirectional"))
      (node (ref "Q4") (pin "1") (pinfunction "G_1") (pintype "bidirectional"))
    )
    (net (code "212") (name "VDD_USB_CAP") (class "Default")
      (node (ref "C79") (pin "2") (pinfunction "2_2") (pintype "passive"))
      (node (ref "C80") (pin "1") (pinfunction "1_1") (pintype "passive"))
      (node (ref "C81") (pin "2") (pinfunction "2_2") (pintype "passive"))
      (node (ref "IC9") (pin "K8") (pinfunction "VDD_USB_CAP_K8") (pintype "bidirectional"))
    )
    (net (code "213") (name "VIN") (class "Default")
      (node (ref "D10") (pin "1") (pinfunction "1_1") (pintype "bidirectional"))
      (node (ref "J7") (pin "2") (pinfunction "2_2") (pintype "passive"))
      (node (ref "Q1") (pin "3") (pinfunction "D_3") (pintype "bidirectional"))
    )
    (net (code "214") (name "V_BATT") (class "Default")
      (node (ref "C3") (pin "2") (pinfunction "2_2") (pintype "passive"))
      (node (ref "C6") (pin "2") (pinfunction "2_2") (pintype "passive"))
      (node (ref "IC1") (pin "2") (pinfunction "VOUT_1_2") (pintype "bidirectional"))
      (node (ref "IC1") (pin "7") (pinfunction "VOUT_2_7") (pintype "bidirectional"))
      (node (ref "U1") (pin "13") (pinfunction "IN_13") (pintype "input"))
    )
    (net (code "215") (name "WAKEUP") (class "Default")
      (node (ref "IC9") (pin "L6") (pinfunction "WAKEUP_L6") (pintype "bidirectional"))
      (node (ref "Q2") (pin "2") (pinfunction "S_2") (pintype "bidirectional"))
    )
    (net (code "216") (name "WIFI_CLK") (class "Default")
      (node (ref "IC9") (pin "M13") (pinfunction "GPIO_AD_B1_09_M13") (pintype "bidirectional"))
      (node (ref "U2") (pin "20") (pinfunction "SDIO_CLK_20") (pintype "input"))
    )
    (net (code "217") (name "WIFI_CMD") (class "Default")
      (node (ref "IC9") (pin "H13") (pinfunction "GPIO_AD_B1_08_H13") (pintype "bidirectional"))
      (node (ref "R63") (pin "1") (pinfunction "1_1") (pintype "passive"))
      (node (ref "U2") (pin "22") (pinfunction "SDIO_CMD_22") (pintype "bidirectional"))
    )
    (net (code "218") (name "WIFI_D0") (class "Default")
      (node (ref "IC9") (pin "M4") (pinfunction "GPIO_SD_B1_03_M4") (pintype "bidirectional"))
      (node (ref "R62") (pin "1") (pinfunction "1_1") (pintype "passive"))
      (node (ref "U2") (pin "24") (pinfunction "SDIO_DATA_0_24") (pintype "bidirectional"))
    )
    (net (code "219") (name "WIFI_D1") (class "Default")
      (node (ref "IC9") (pin "M3") (pinfunction "GPIO_SD_B1_02_M3") (pintype "bidirectional"))
      (node (ref "R61") (pin "1") (pinfunction "1_1") (pintype "passive"))
      (node (ref "U2") (pin "26") (pinfunction "SDIO_DATA_1_26") (pintype "bidirectional"))
    )
    (net (code "220") (name "WIFI_D2") (class "Default")
      (node (ref "IC9") (pin "J12") (pinfunction "GPIO_AD_B1_06_J12") (pintype "bidirectional"))
      (node (ref "R60") (pin "1") (pinfunction "1_1") (pintype "passive"))
      (node (ref "U2") (pin "23") (pinfunction "SDIO_DATA_2_23") (pintype "bidirectional"))
    )
    (net (code "221") (name "WIFI_D3") (class "Default")
      (node (ref "IC9") (pin "K10") (pinfunction "GPIO_AD_B1_07_K10") (pintype "bidirectional"))
      (node (ref "R59") (pin "1") (pinfunction "1_1") (pintype "passive"))
      (node (ref "U2") (pin "25") (pinfunction "SDIO_DATA_3_25") (pintype "bidirectional"))
    )
    (net (code "222") (name "WL_H_WAKE") (class "Default")
      (node (ref "IC9") (pin "E11") (pinfunction "GPIO_B0_15_E11") (pintype "bidirectional"))
      (node (ref "R57") (pin "1") (pinfunction "1_1") (pintype "passive"))
      (node (ref "U2") (pin "27") (pinfunction "WL_GPIO_0_HOST_WAKE_27") (pintype "bidirectional"))
    )
    (net (code "223") (name "WL_REG_ON") (class "Default")
      (node (ref "IC9") (pin "E10") (pinfunction "GPIO_B0_14_E10") (pintype "bidirectional"))
      (node (ref "U2") (pin "28") (pinfunction "WL_REG_ON_28") (pintype "input"))
    )
    (net (code "224") (name "XTALI") (class "Default")
      (node (ref "C106") (pin "1") (pinfunction "1_1") (pintype "passive"))
      (node (ref "IC9") (pin "P11") (pinfunction "XTALI_P11") (pintype "bidirectional"))
      (node (ref "R67") (pin "1") (pinfunction "1_1") (pintype "passive"))
      (node (ref "Y2") (pin "3") (pinfunction "CRYSTAL_2_3") (pintype "bidirectional"))
    )
    (net (code "225") (name "XTALO") (class "Default")
      (node (ref "C105") (pin "1") (pinfunction "1_1") (pintype "passive"))
      (node (ref "IC9") (pin "N11") (pinfunction "XTALO_N11") (pintype "bidirectional"))
      (node (ref "Y2") (pin "1") (pinfunction "CRYSTAL_1_1") (pintype "bidirectional"))
    )
    (net (code "226") (name "unconnected-(ANT1-NC-Pad2)") (class "Default")
      (node (ref "ANT1") (pin "2") (pinfunction "NC_2") (pintype "no_connect"))
    )
    (net (code "227") (name "unconnected-(FL1-Pad9)") (class "Default")
      (node (ref "FL1") (pin "9") (pinfunction "9_9") (pintype "bidirectional"))
    )
    (net (code "228") (name "unconnected-(FL1-Pad10)") (class "Default")
      (node (ref "FL1") (pin "10") (pinfunction "10_10") (pintype "bidirectional"))
    )
    (net (code "229") (name "unconnected-(FL1-Pad11)") (class "Default")
      (node (ref "FL1") (pin "11") (pinfunction "11_11") (pintype "bidirectional"))
    )
    (net (code "230") (name "unconnected-(FL1-Pad12)") (class "Default")
      (node (ref "FL1") (pin "12") (pinfunction "12_12") (pintype "bidirectional"))
    )
    (net (code "231") (name "unconnected-(H1-MOUNT-PadB2,8)") (class "Default")
      (node (ref "H1") (pin "B2,8") (pinfunction "MOUNT_B2,8") (pintype "passive"))
    )
    (net (code "232") (name "unconnected-(H2-MOUNT-PadB2,8)") (class "Default")
      (node (ref "H2") (pin "B2,8") (pinfunction "MOUNT_B2,8") (pintype "passive"))
    )
    (net (code "233") (name "unconnected-(IC2-NC-Pad4)") (class "Default")
      (node (ref "IC2") (pin "4") (pinfunction "NC_4") (pintype "no_connect"))
    )
    (net (code "234") (name "unconnected-(IC4-NC-PadE2)") (class "Default")
      (node (ref "IC4") (pin "E2") (pinfunction "NC_E2") (pintype "no_connect"))
    )
    (net (code "235") (name "unconnected-(IC6-ISO_7816_CLK-Pad13)") (class "Default")
      (node (ref "IC6") (pin "13") (pinfunction "ISO_7816_CLK_13") (pintype "input"))
    )
    (net (code "236") (name "unconnected-(IC6-ISO_7816_IO1-Pad3)") (class "Default")
      (node (ref "IC6") (pin "3") (pinfunction "ISO_7816_IO1_3") (pintype "bidirectional"))
    )
    (net (code "237") (name "unconnected-(IC6-ISO_7816_IO2-Pad16)") (class "Default")
      (node (ref "IC6") (pin "16") (pinfunction "ISO_7816_IO2_16") (pintype "bidirectional"))
    )
    (net (code "238") (name "unconnected-(IC6-ISO_7816_RST_N-Pad14)") (class "Default")
      (node (ref "IC6") (pin "14") (pinfunction "ISO_7816_RST_N_14") (pintype "input"))
    )
    (net (code "239") (name "unconnected-(IC6-ISO_14443_LA-Pad17)") (class "Default")
      (node (ref "IC6") (pin "17") (pinfunction "ISO_14443_LA_17") (pintype "bidirectional"))
    )
    (net (code "240") (name "unconnected-(IC6-ISO_14443_LB-Pad1)") (class "Default")
      (node (ref "IC6") (pin "1") (pinfunction "ISO_14443_LB_1") (pintype "bidirectional"))
    )
    (net (code "241") (name "unconnected-(IC6-NC_1-Pad2)") (class "Default")
      (node (ref "IC6") (pin "2") (pinfunction "NC_1_2") (pintype "bidirectional"))
    )
    (net (code "242") (name "unconnected-(IC6-NC_2-Pad4)") (class "Default")
      (node (ref "IC6") (pin "4") (pinfunction "NC_2_4") (pintype "bidirectional"))
    )
    (net (code "243") (name "unconnected-(IC6-NC_3-Pad5)") (class "Default")
      (node (ref "IC6") (pin "5") (pinfunction "NC_3_5") (pintype "bidirectional"))
    )
    (net (code "244") (name "unconnected-(IC6-NC_4-Pad6)") (class "Default")
      (node (ref "IC6") (pin "6") (pinfunction "NC_4_6") (pintype "bidirectional"))
    )
    (net (code "245") (name "unconnected-(IC6-NC_5-Pad7)") (class "Default")
      (node (ref "IC6") (pin "7") (pinfunction "NC_5_7") (pintype "bidirectional"))
    )
    (net (code "246") (name "unconnected-(IC6-NC_6-Pad8)") (class "Default")
      (node (ref "IC6") (pin "8") (pinfunction "NC_6_8") (pintype "bidirectional"))
    )
    (net (code "247") (name "unconnected-(IC6-NC_7-Pad20)") (class "Default")
      (node (ref "IC6") (pin "20") (pinfunction "NC_7_20") (pintype "bidirectional"))
    )
    (net (code "248") (name "unconnected-(IC7-NC-Pad2)") (class "Default")
      (node (ref "IC7") (pin "2") (pinfunction "NC_2") (pintype "no_connect"))
    )
    (net (code "249") (name "unconnected-(IC8-REF_CLK-Pad16)") (class "Default")
      (node (ref "IC8") (pin "16") (pinfunction "REF_CLK_16") (pintype "bidirectional"))
    )
    (net (code "250") (name "unconnected-(IC8-XO-Pad7)") (class "Default")
      (node (ref "IC8") (pin "7") (pinfunction "XO_7") (pintype "bidirectional"))
    )
    (net (code "251") (name "unconnected-(IC9-CCM_CLK1_N-PadP13)") (class "Default")
      (node (ref "IC9") (pin "P13") (pinfunction "CCM_CLK1_N_P13") (pintype "bidirectional"))
    )
    (net (code "252") (name "unconnected-(IC9-CCM_CLK1_P-PadN13)") (class "Default")
      (node (ref "IC9") (pin "N13") (pinfunction "CCM_CLK1_P_N13") (pintype "bidirectional"))
    )
    (net (code "253") (name "unconnected-(IC9-GPANAIO-PadN10)") (class "Default")
      (node (ref "IC9") (pin "N10") (pinfunction "GPANAIO_N10") (pintype "bidirectional"))
    )
    (net (code "254") (name "unconnected-(IC9-GPIO_EMC_39-PadB7)") (class "Default")
      (node (ref "IC9") (pin "B7") (pinfunction "GPIO_EMC_39_B7") (pintype "bidirectional"))
    )
    (net (code "255") (name "unconnected-(IC9-GPIO_SD_B1_05-PadN3)") (class "Default")
      (node (ref "IC9") (pin "N3") (pinfunction "GPIO_SD_B1_05_N3") (pintype "bidirectional"))
    )
    (net (code "256") (name "unconnected-(IC9-USB_OTG1_CHD_B-PadN12)") (class "Default")
      (node (ref "IC9") (pin "N12") (pinfunction "USB_OTG1_CHD_B_N12") (pintype "bidirectional"))
    )
    (net (code "257") (name "unconnected-(IC9-USB_OTG2_DN-PadN7)") (class "Default")
      (node (ref "IC9") (pin "N7") (pinfunction "USB_OTG2_DN_N7") (pintype "bidirectional"))
    )
    (net (code "258") (name "unconnected-(IC9-USB_OTG2_DP-PadP7)") (class "Default")
      (node (ref "IC9") (pin "P7") (pinfunction "USB_OTG2_DP_P7") (pintype "bidirectional"))
    )
    (net (code "259") (name "unconnected-(IC9-USB_OTG2_VBUS-PadP6)") (class "Default")
      (node (ref "IC9") (pin "P6") (pinfunction "USB_OTG2_VBUS_P6") (pintype "bidirectional"))
    )
    (net (code "260") (name "unconnected-(J1-SBU1-PadA8)") (class "Default")
      (node (ref "J1") (pin "A8") (pinfunction "SBU1_A8") (pintype "bidirectional"))
    )
    (net (code "261") (name "unconnected-(J1-SBU2-PadB8)") (class "Default")
      (node (ref "J1") (pin "B8") (pinfunction "SBU2_B8") (pintype "bidirectional"))
    )
    (net (code "262") (name "unconnected-(J3-Pad1)") (class "Default")
      (node (ref "J3") (pin "1") (pinfunction "1_1") (pintype "bidirectional"))
    )
    (net (code "263") (name "unconnected-(J3-Pad3)") (class "Default")
      (node (ref "J3") (pin "3") (pinfunction "3_3") (pintype "bidirectional"))
    )
    (net (code "264") (name "unconnected-(J3-Pad6)") (class "Default")
      (node (ref "J3") (pin "6") (pinfunction "6_6") (pintype "bidirectional"))
    )
    (net (code "265") (name "unconnected-(J3-Pad7)") (class "Default")
      (node (ref "J3") (pin "7") (pinfunction "7_7") (pintype "bidirectional"))
    )
    (net (code "266") (name "unconnected-(J3-Pad8)") (class "Default")
      (node (ref "J3") (pin "8") (pinfunction "8_8") (pintype "bidirectional"))
    )
    (net (code "267") (name "unconnected-(J3-Pad9)") (class "Default")
      (node (ref "J3") (pin "9") (pinfunction "9_9") (pintype "bidirectional"))
    )
    (net (code "268") (name "unconnected-(J6-Pad5)") (class "Default")
      (node (ref "J6") (pin "5") (pinfunction "5_5") (pintype "passive"))
    )
    (net (code "269") (name "unconnected-(J6-Pad6)") (class "Default")
      (node (ref "J6") (pin "6") (pinfunction "6_6") (pintype "passive"))
    )
    (net (code "270") (name "unconnected-(J6-Pad7)") (class "Default")
      (node (ref "J6") (pin "7") (pinfunction "7_7") (pintype "passive"))
    )
    (net (code "271") (name "unconnected-(J6-Pad8)") (class "Default")
      (node (ref "J6") (pin "8") (pinfunction "8_8") (pintype "passive"))
    )
    (net (code "272") (name "unconnected-(J8-Pad7)") (class "Default")
      (node (ref "J8") (pin "7") (pinfunction "7_7") (pintype "passive"))
    )
    (net (code "273") (name "unconnected-(U2-BT_GPIO_3-Pad6)") (class "Default")
      (node (ref "U2") (pin "6") (pinfunction "BT_GPIO_3_6") (pintype "bidirectional"))
    )
    (net (code "274") (name "unconnected-(U2-BT_GPIO_4-Pad7)") (class "Default")
      (node (ref "U2") (pin "7") (pinfunction "BT_GPIO_4_7") (pintype "bidirectional"))
    )
    (net (code "275") (name "unconnected-(U2-BT_GPIO_5-Pad13)") (class "Default")
      (node (ref "U2") (pin "13") (pinfunction "BT_GPIO_5_13") (pintype "bidirectional"))
    )
    (net (code "276") (name "unconnected-(U2-BT_I2S_DO-Pad16)") (class "Default")
      (node (ref "U2") (pin "16") (pinfunction "BT_I2S_DO_16") (pintype "bidirectional"))
    )
    (net (code "277") (name "unconnected-(U2-BT_PCM_CLK-Pad11)") (class "Default")
      (node (ref "U2") (pin "11") (pinfunction "BT_PCM_CLK_11") (pintype "bidirectional"))
    )
    (net (code "278") (name "unconnected-(U2-BT_PCM_IN-Pad9)") (class "Default")
      (node (ref "U2") (pin "9") (pinfunction "BT_PCM_IN_9") (pintype "input"))
    )
    (net (code "279") (name "unconnected-(U2-BT_PCM_OUT-Pad10)") (class "Default")
      (node (ref "U2") (pin "10") (pinfunction "BT_PCM_OUT_10") (pintype "output"))
    )
    (net (code "280") (name "unconnected-(U2-BT_PCM_SYNC-Pad8)") (class "Default")
      (node (ref "U2") (pin "8") (pinfunction "BT_PCM_SYNC_8") (pintype "bidirectional"))
    )
    (net (code "281") (name "unconnected-(U2-WL_GPIO_1-Pad18)") (class "Default")
      (node (ref "U2") (pin "18") (pinfunction "WL_GPIO_1_18") (pintype "bidirectional"))
    )
    (net (code "282") (name "unconnected-(U2-WL_GPIO_2-Pad17)") (class "Default")
      (node (ref "U2") (pin "17") (pinfunction "WL_GPIO_2_17") (pintype "bidirectional"))
    )
    (net (code "283") (name "unconnected-(U2-WL_GPIO_4-Pad15)") (class "Default")
      (node (ref "U2") (pin "15") (pinfunction "WL_GPIO_4_15") (pintype "bidirectional"))
    )
  )
)
